# piezo-driver_v0_95-R003.net
KiCad netlist of a schematic drawn in EAGLE
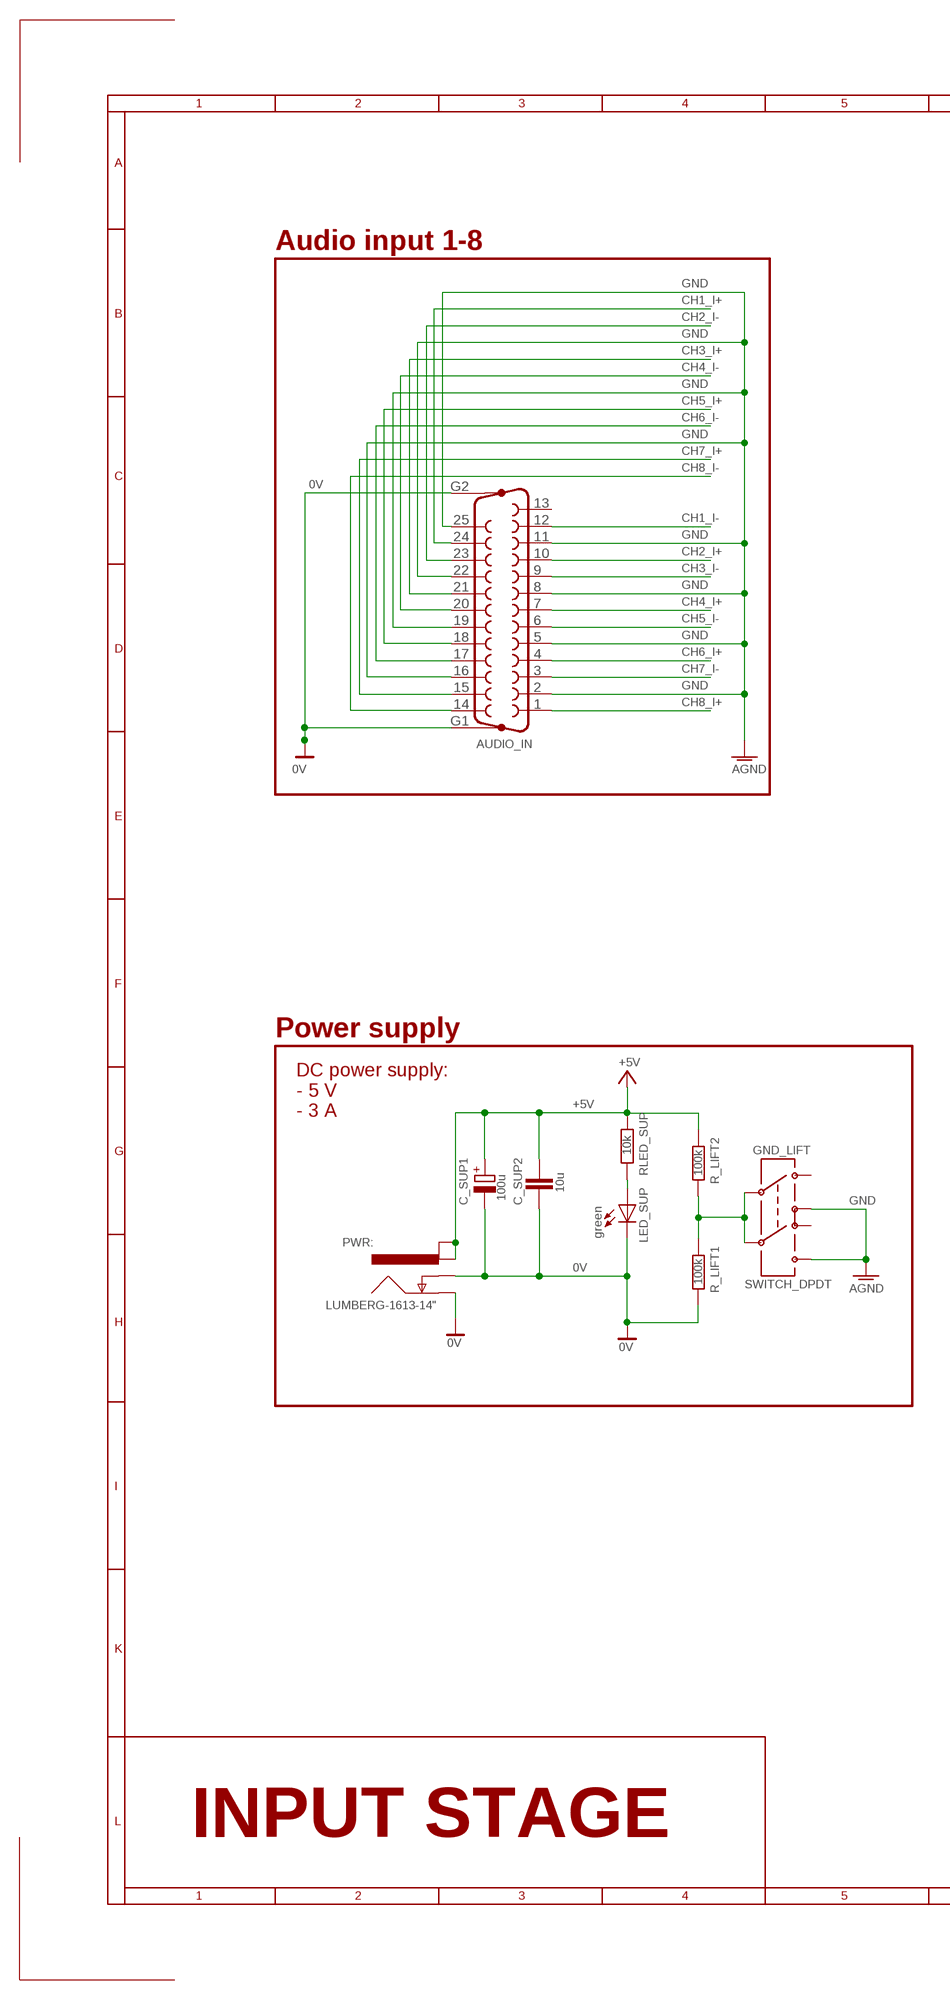
[diagram p0: schematic, sheet 1, part 1 of 2]
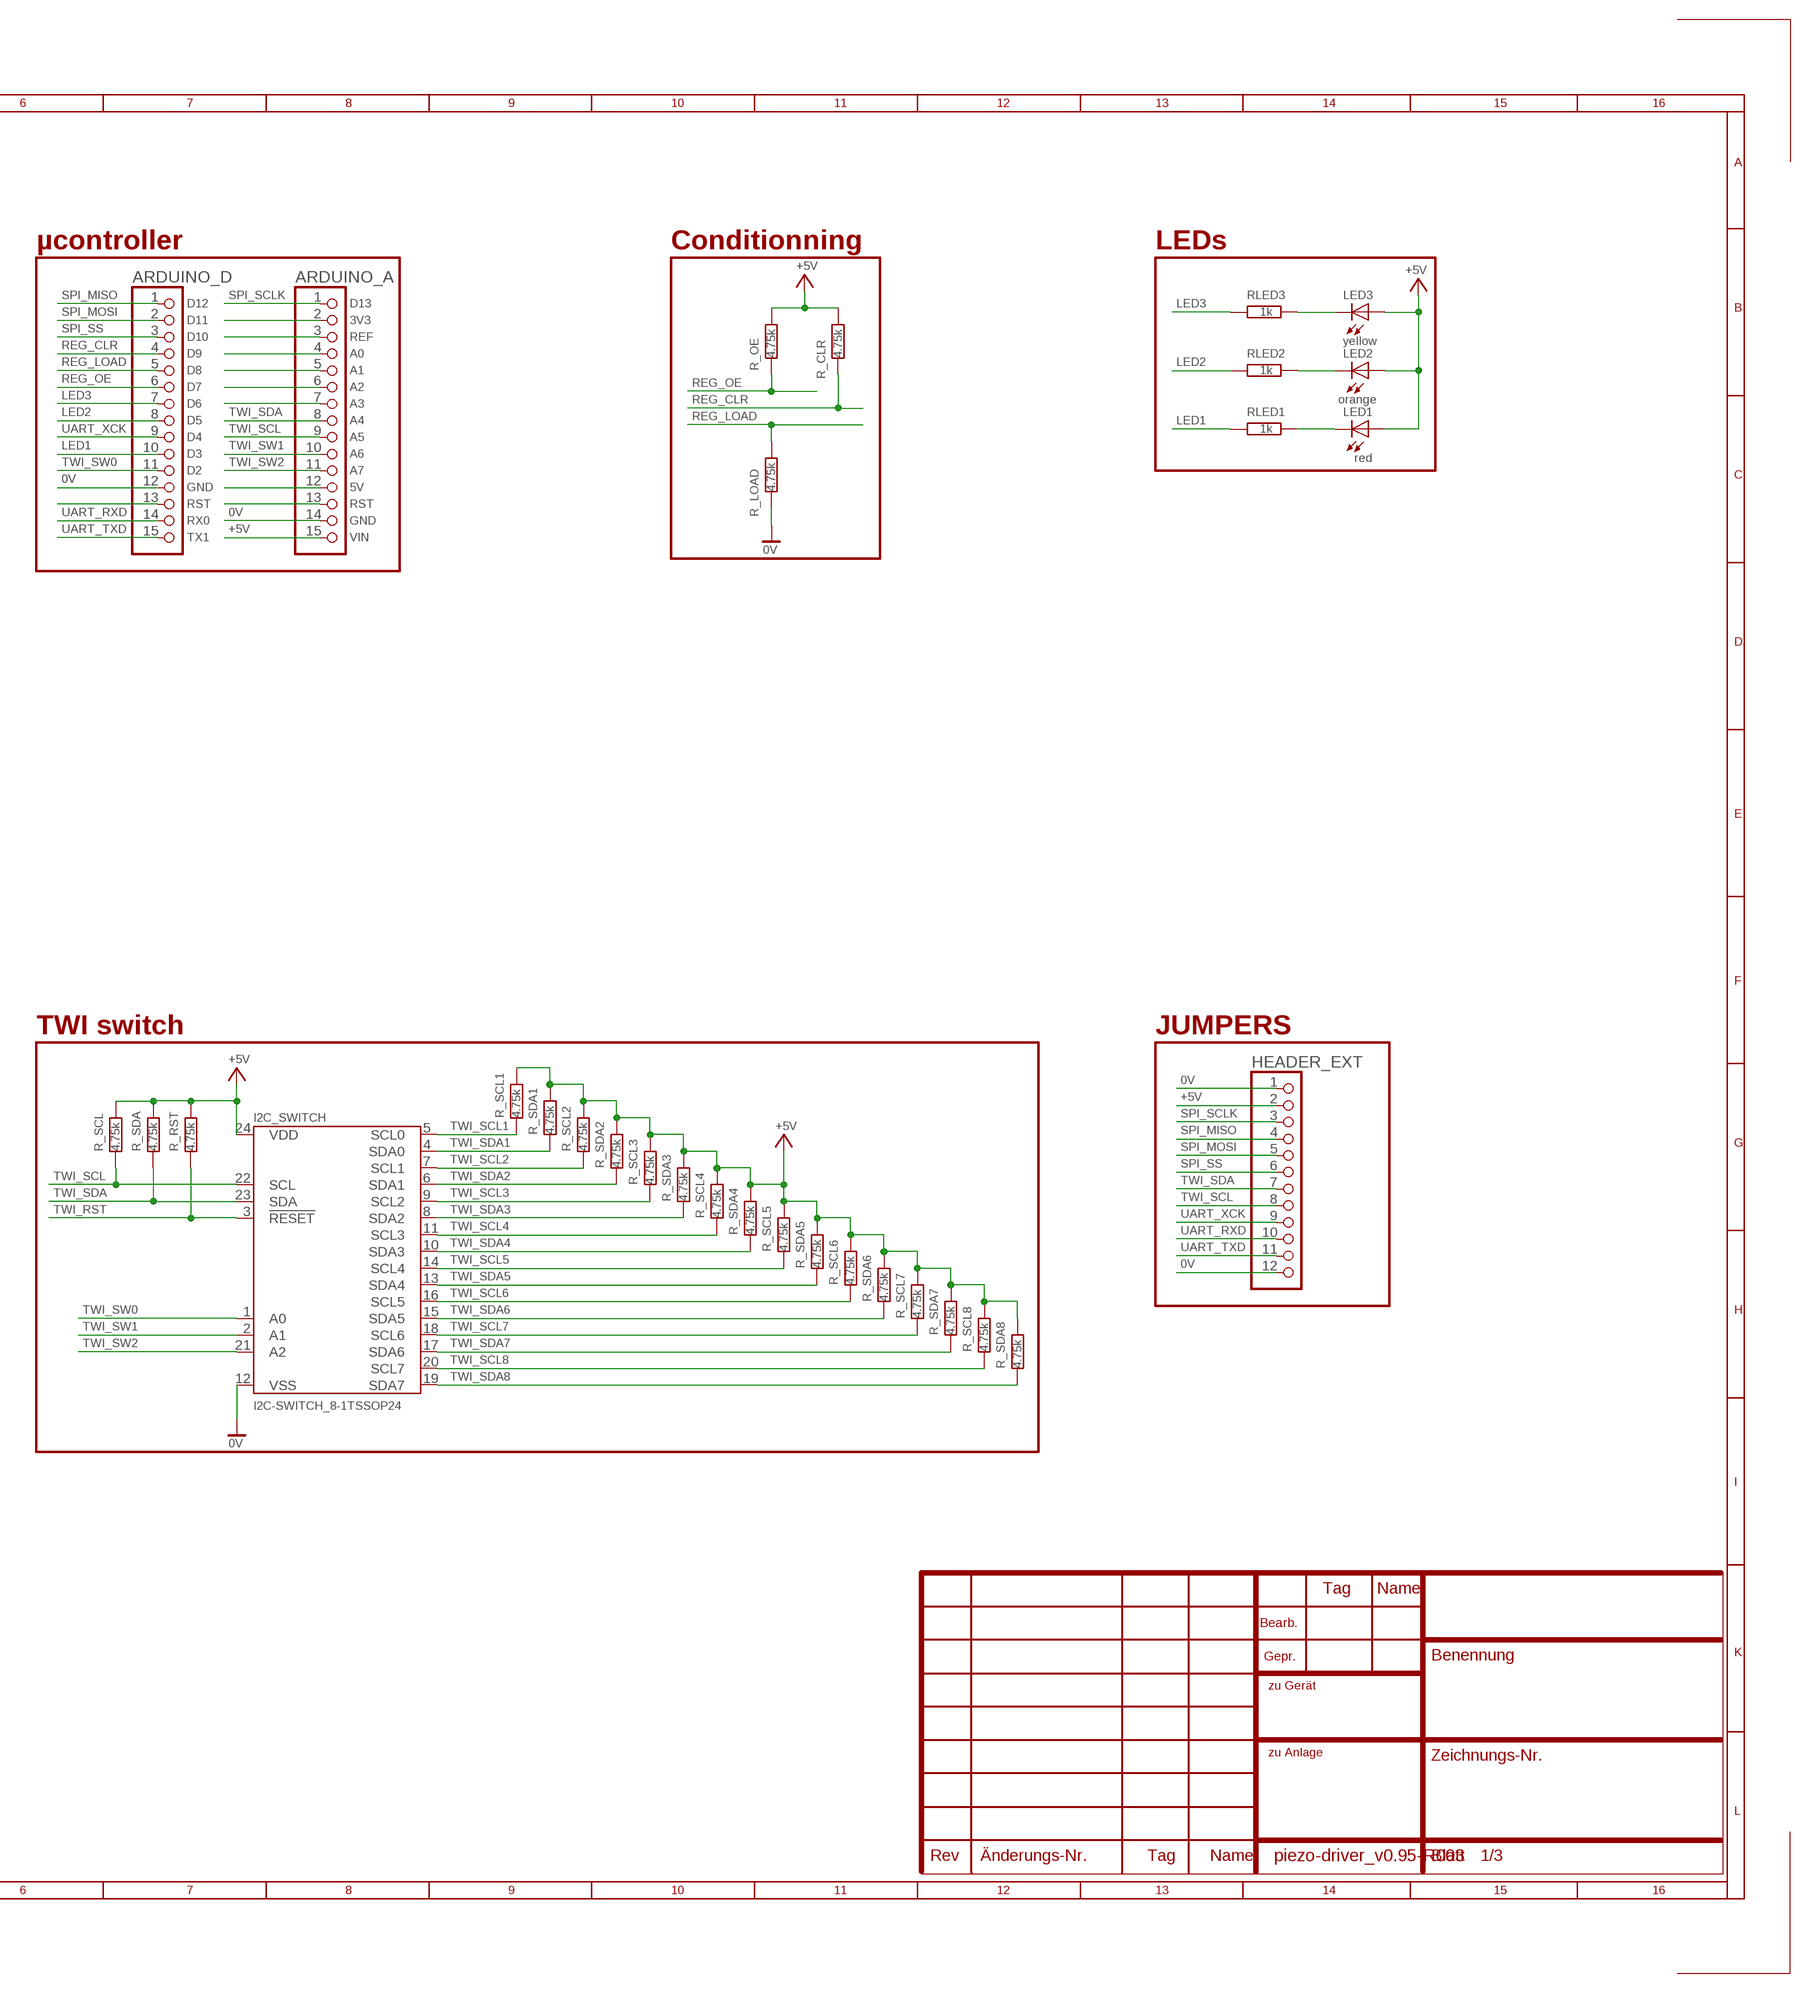
[diagram p1: schematic, sheet 1, part 2 of 2]
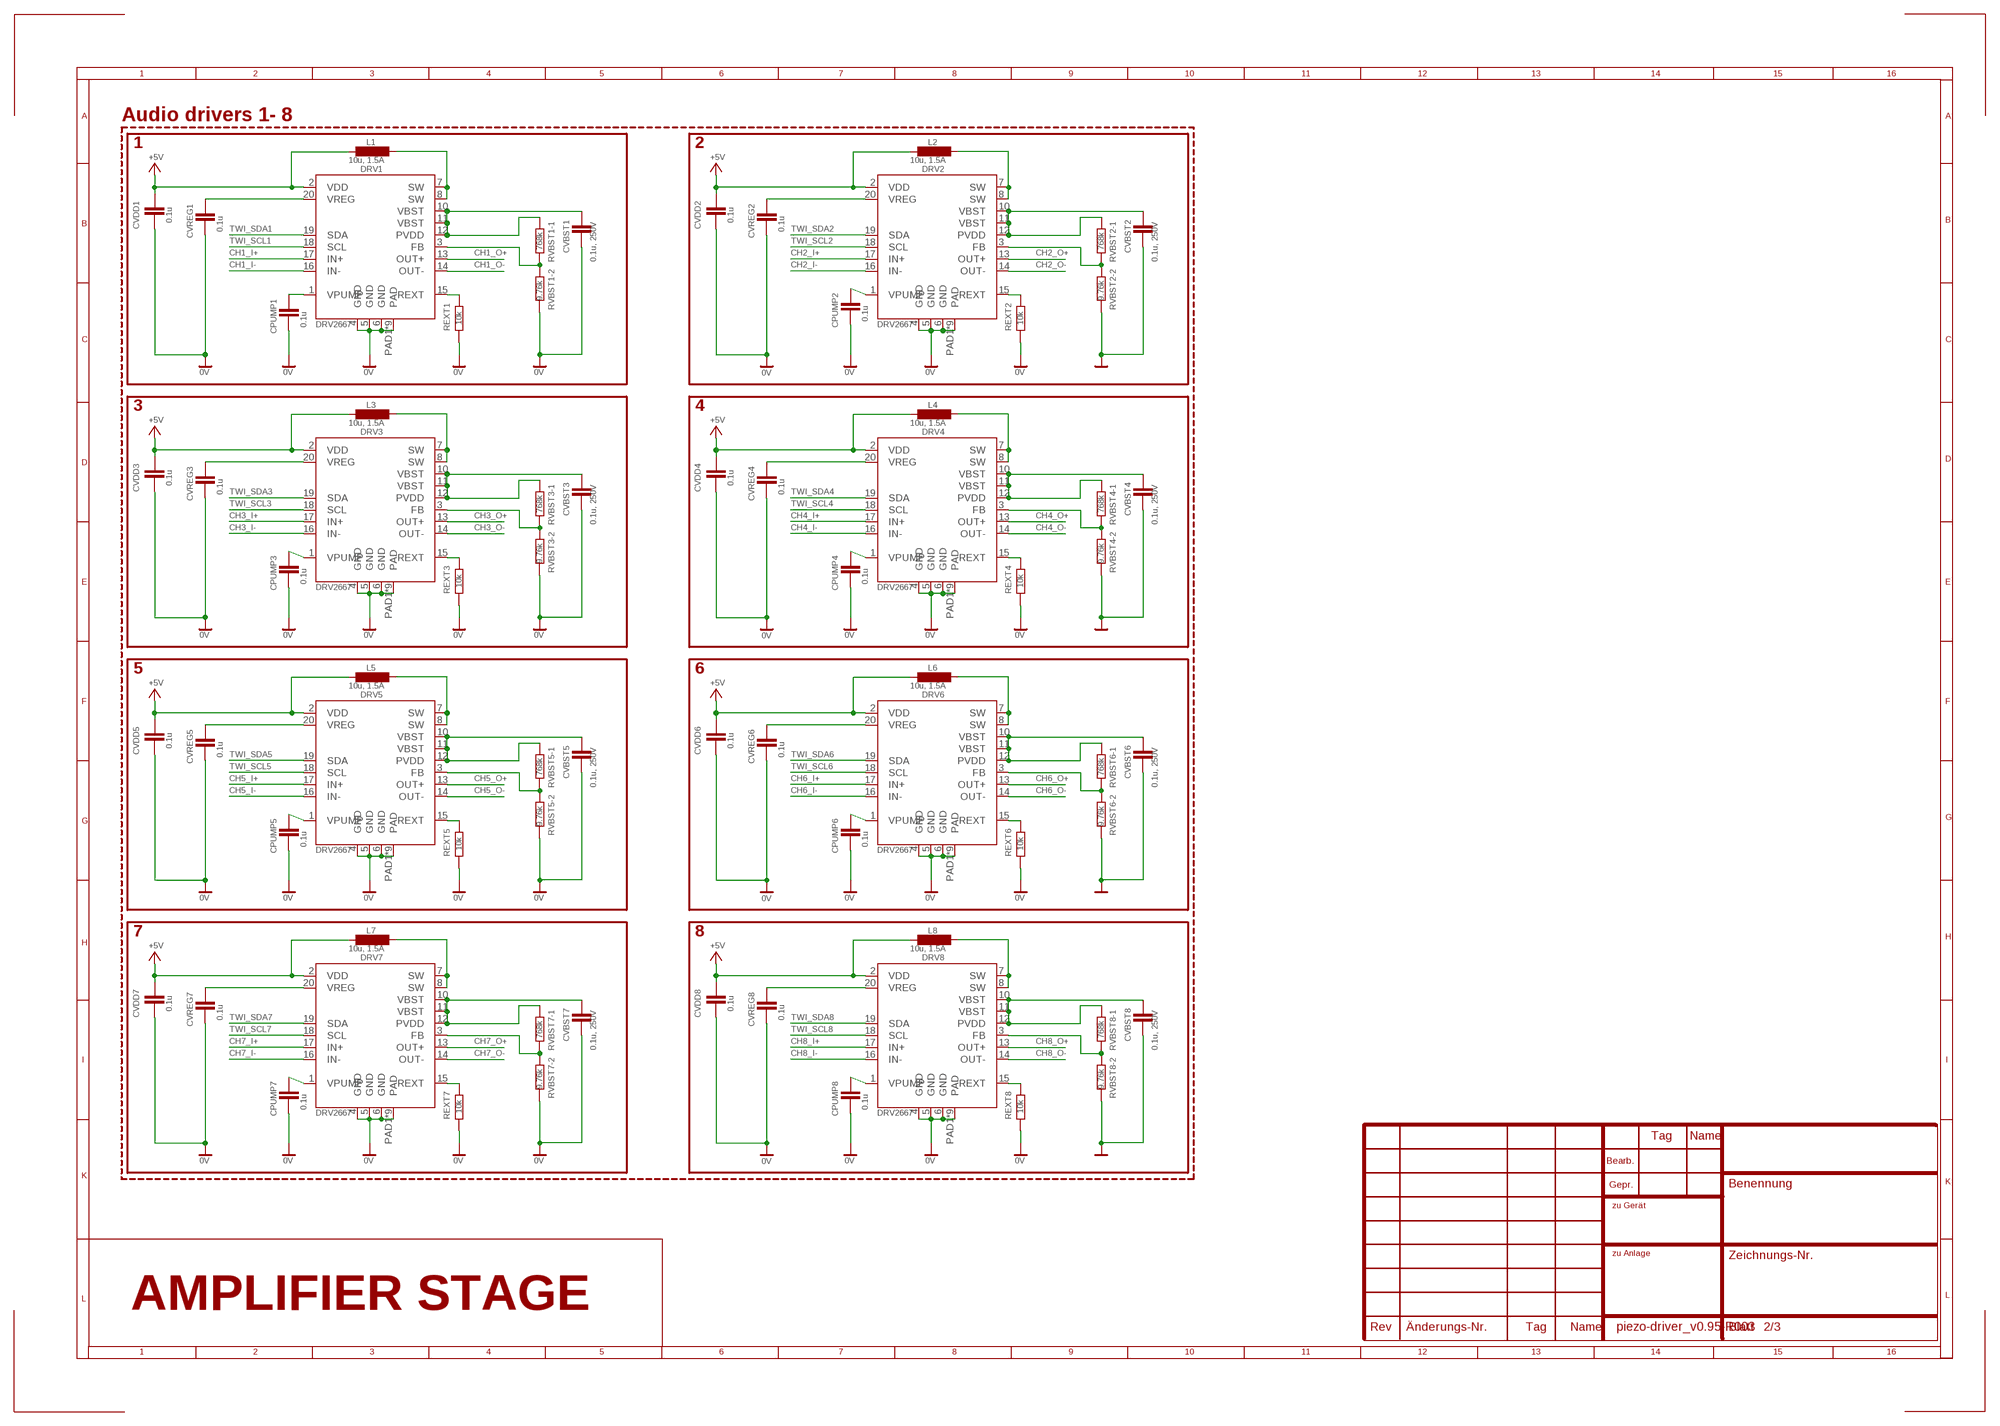
[diagram p2: schematic, sheet 2]
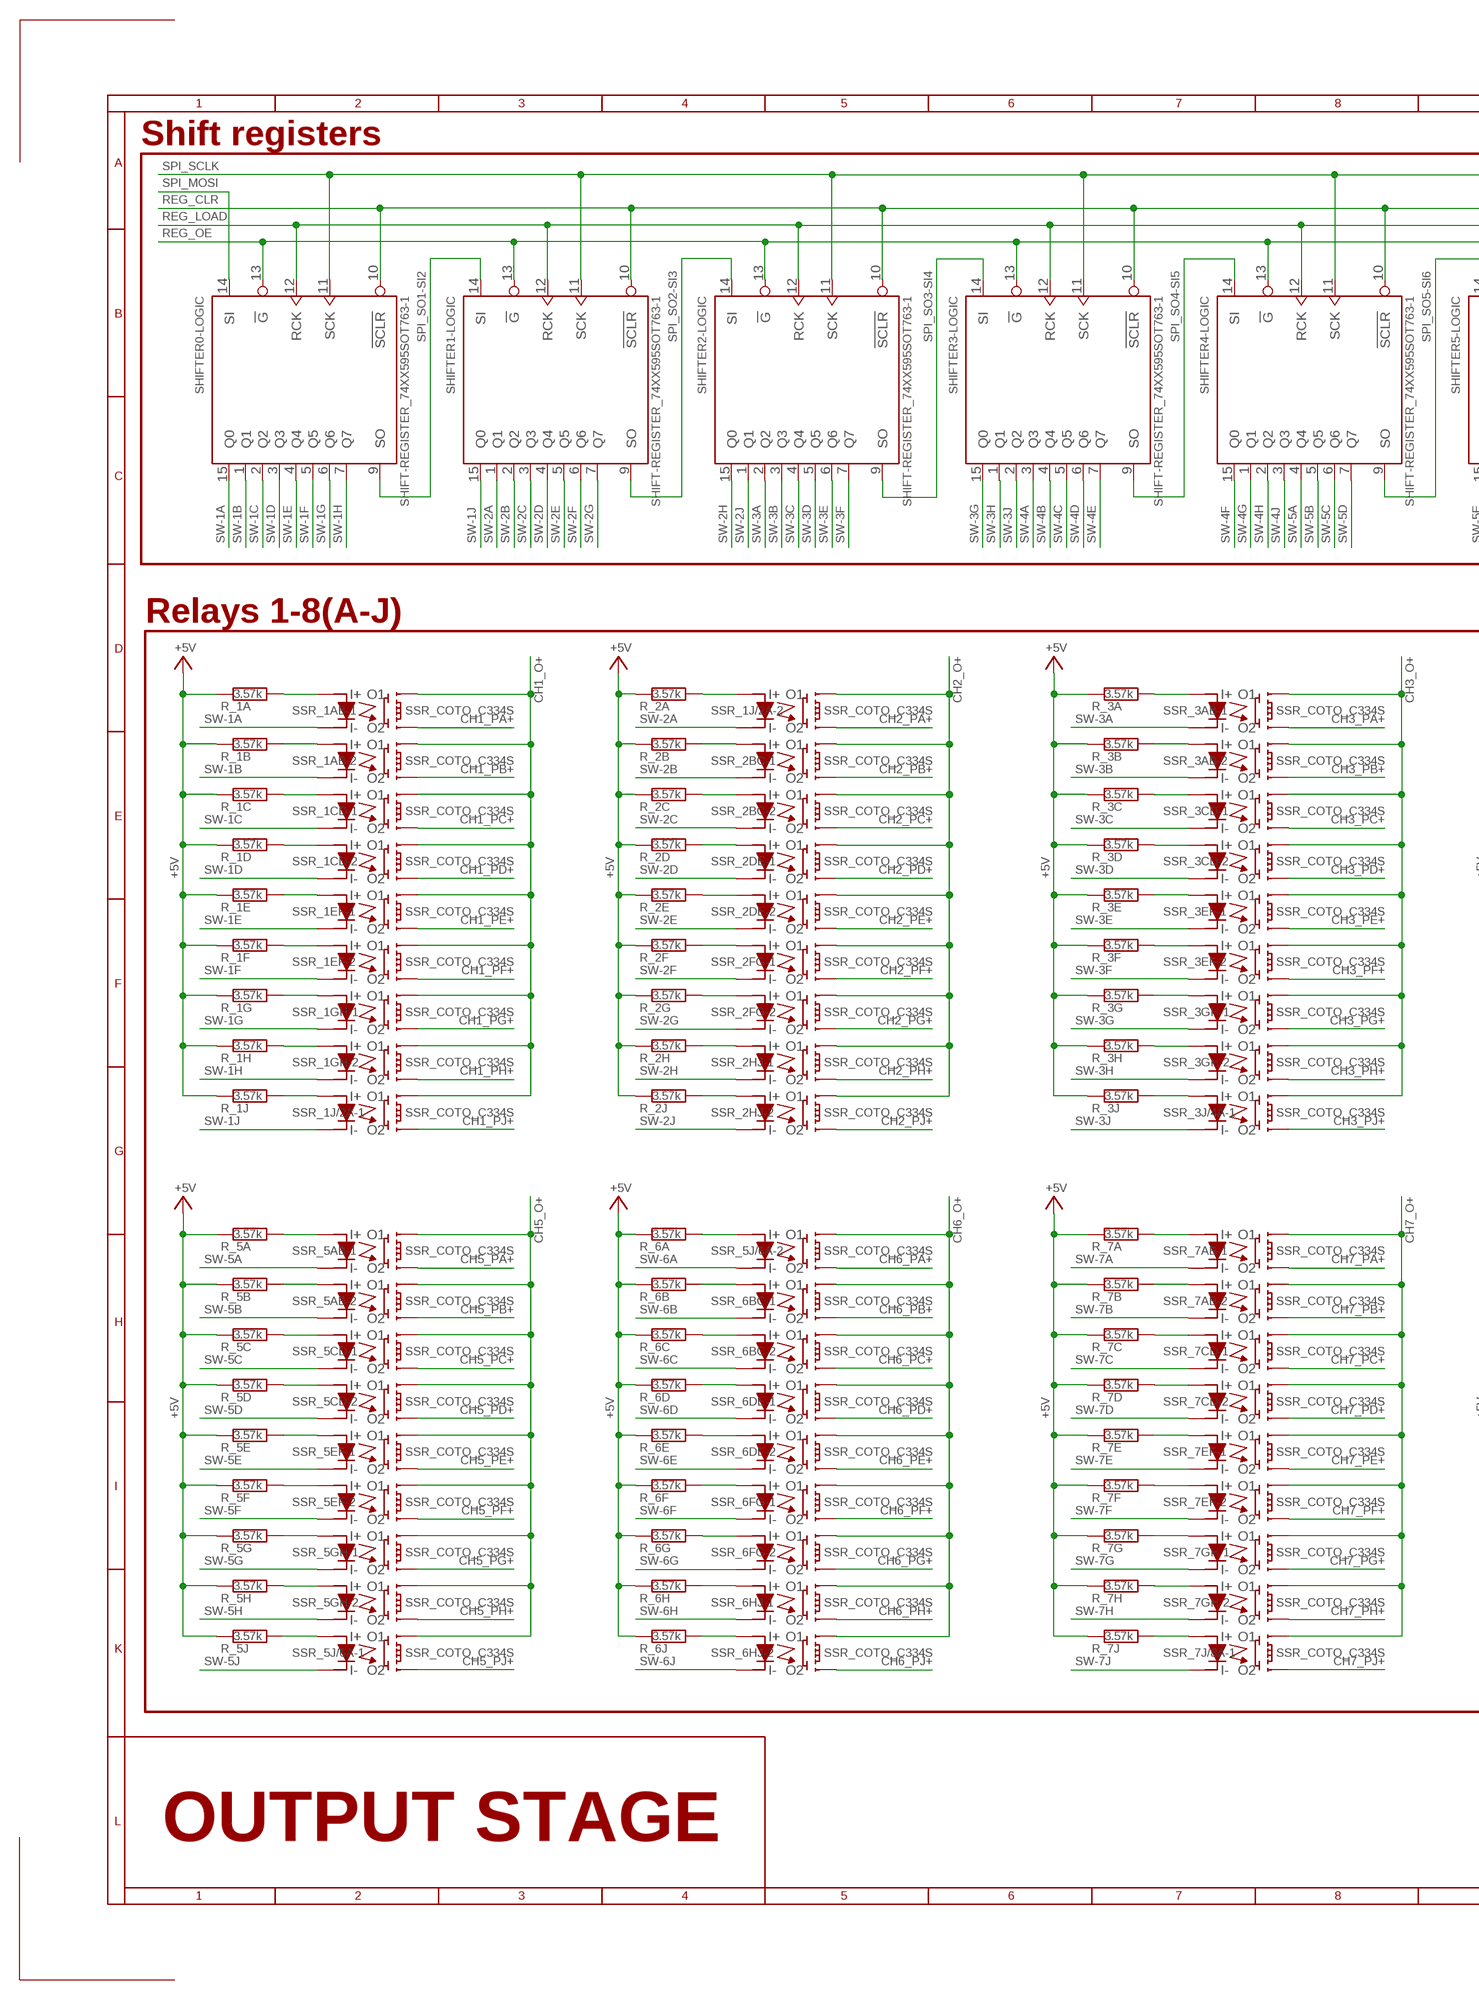
[diagram p3: schematic, sheet 3, part 1 of 2]
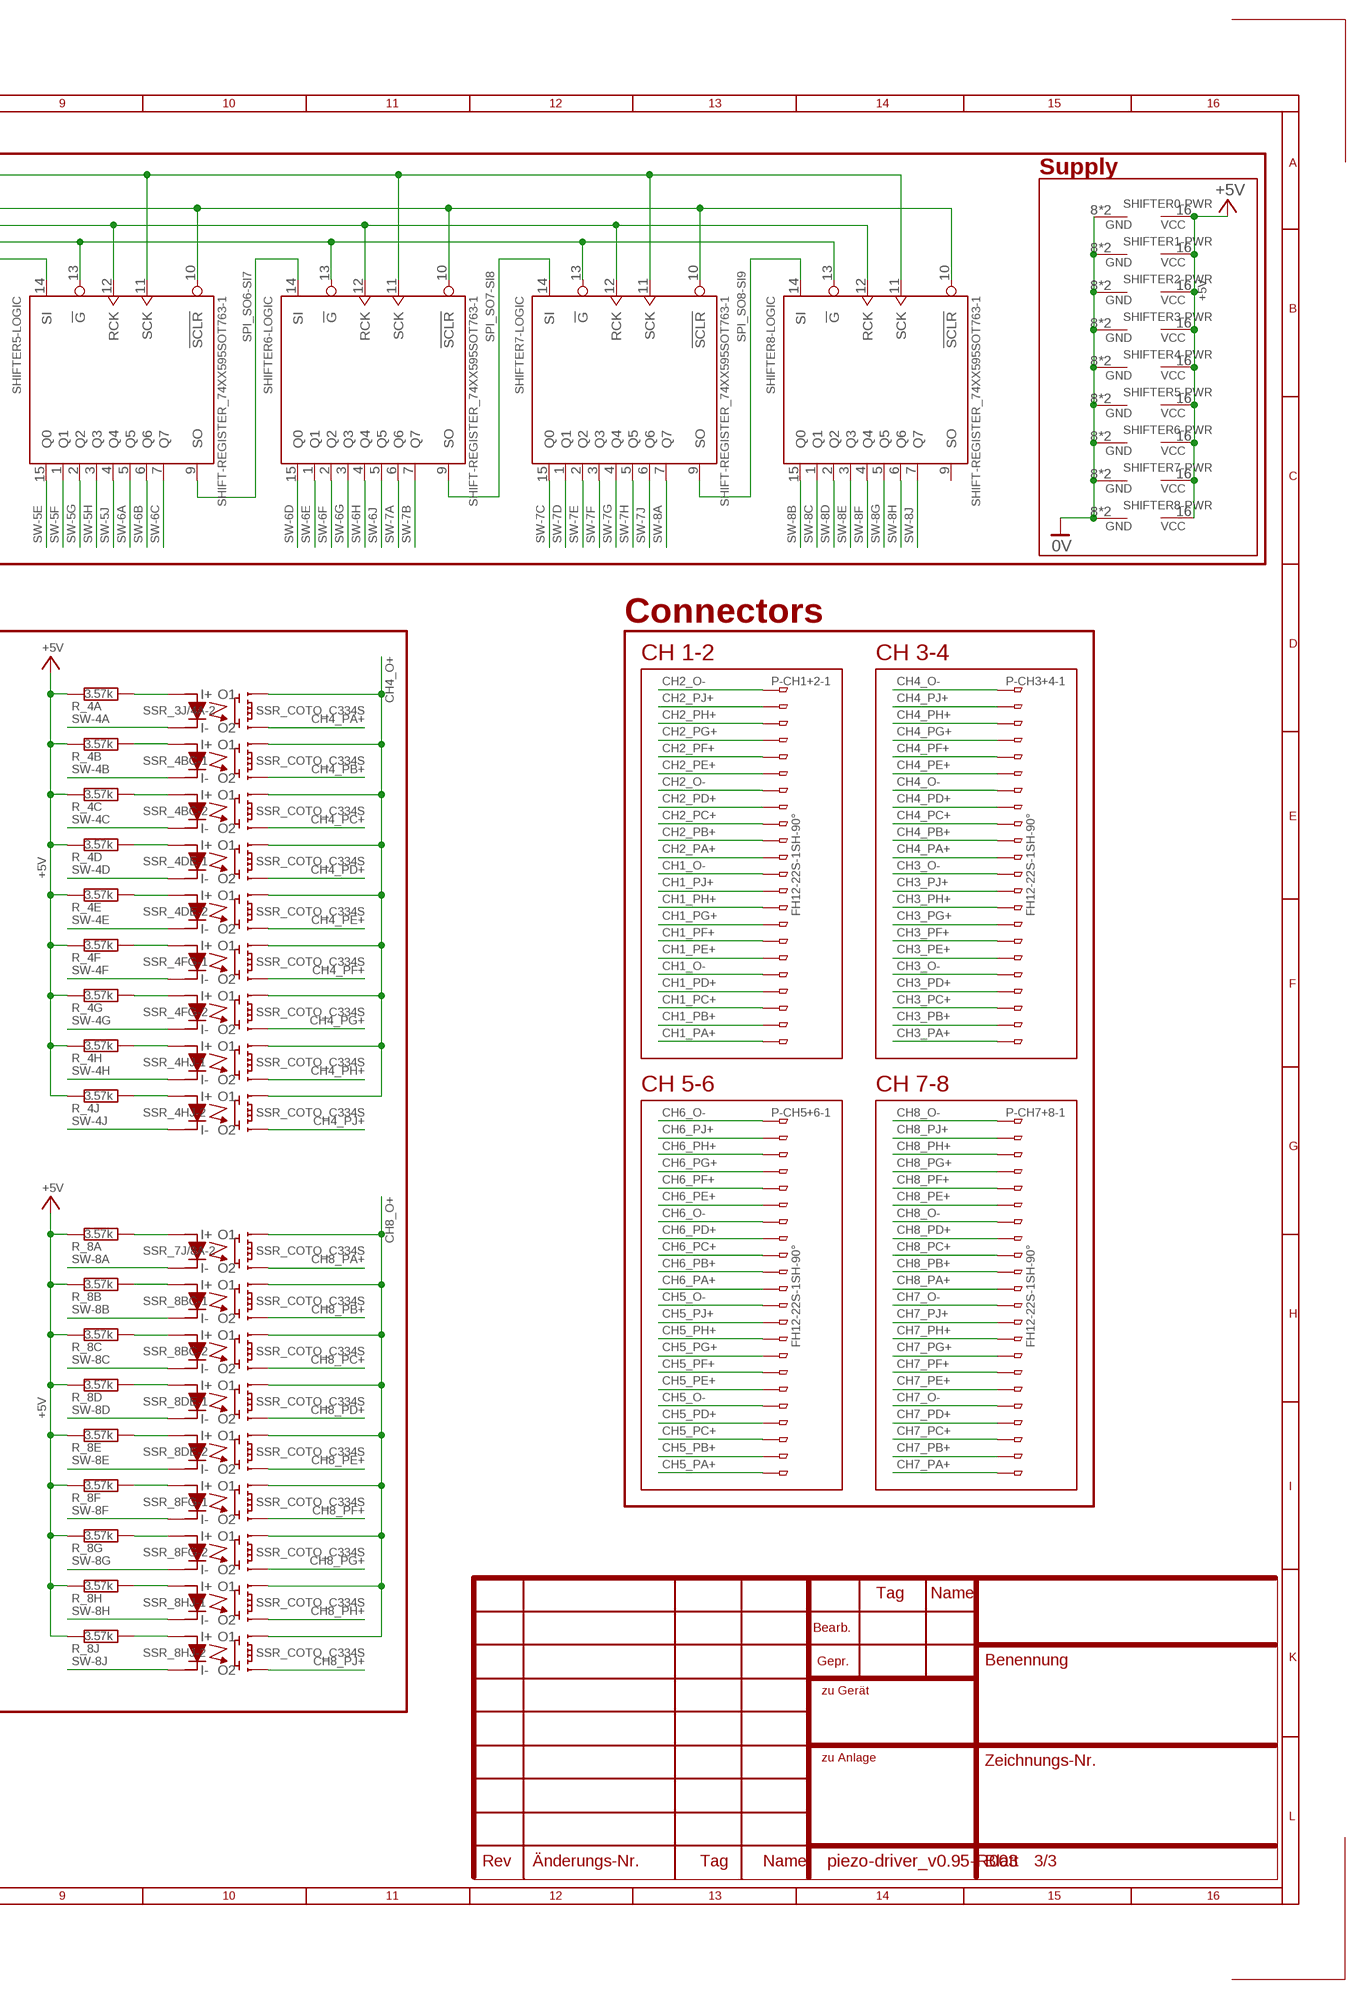
[diagram p4: schematic, sheet 3, part 2 of 2]

(export (version "E")
  (design (tool "Eeschema 10.0.6"))
  (components
    (comp (ref "ARDUINO_A")
      (value "PINHD-1X15")
      (footprint "eagle-import:1X15")
      (libsource (lib "eagle-import") (part "PINHD-1X15"))
    )
    (comp (ref "ARDUINO_D")
      (value "PINHD-1X15")
      (footprint "eagle-import:1X15")
      (libsource (lib "eagle-import") (part "PINHD-1X15"))
    )
    (comp (ref "AUDIO_IN")
      (value "F25HP")
      (footprint "eagle-import:F25HP")
      (libsource (lib "eagle-import") (part "F25HP"))
    )
    (comp (ref "C_SUP1")
      (value "100u")
      (footprint "eagle-import:EIA3216")
      (libsource (lib "eagle-import") (part "CAP_POL12061"))
    )
    (comp (ref "C_SUP2")
      (value "10u")
      (footprint "eagle-import:C0805K")
      (libsource (lib "eagle-import") (part "C-EUC0805K"))
    )
    (comp (ref "GND_LIFT")
      (value "SWITCH_DPDT")
      (footprint "eagle-import:SWITCH_JS202011")
      (libsource (lib "eagle-import") (part "SWITCH_DPDT"))
    )
    (comp (ref "HEADER_EXT")
      (value "PINHD-1X12")
      (footprint "eagle-import:1X12")
      (libsource (lib "eagle-import") (part "PINHD-1X12"))
    )
    (comp (ref "I2C_SWITCH")
      (value "I2C-SWITCH_8-1TSSOP24")
      (footprint "eagle-import:TSSOP24")
      (libsource (lib "eagle-import") (part "I2C-SWITCH_8-1TSSOP24"))
    )
    (comp (ref "LED1")
      (value "red")
      (footprint "eagle-import:LED-1206")
      (libsource (lib "eagle-import") (part "LED1206"))
    )
    (comp (ref "LED2")
      (value "orange")
      (footprint "eagle-import:LED-1206")
      (libsource (lib "eagle-import") (part "LED1206"))
    )
    (comp (ref "LED3")
      (value "yellow")
      (footprint "eagle-import:LED-1206")
      (libsource (lib "eagle-import") (part "LED1206"))
    )
    (comp (ref "LED_SUP")
      (value "green")
      (footprint "eagle-import:LED-1206")
      (libsource (lib "eagle-import") (part "LED1206"))
    )
    (comp (ref "PWR:")
      (value "LUMBERG-1613-14\"")
      (footprint "eagle-import:LUMBERG-1613_14")
      (libsource (lib "eagle-import") (part "LUMBERG-1613-14{dblquote}"))
    )
    (comp (ref "RLED1")
      (value "1k")
      (footprint "eagle-import:R0402")
      (libsource (lib "eagle-import") (part "R-EU_R0402"))
    )
    (comp (ref "RLED2")
      (value "1k")
      (footprint "eagle-import:R0402")
      (libsource (lib "eagle-import") (part "R-EU_R0402"))
    )
    (comp (ref "RLED3")
      (value "1k")
      (footprint "eagle-import:R0402")
      (libsource (lib "eagle-import") (part "R-EU_R0402"))
    )
    (comp (ref "RLED_SUP")
      (value "10k")
      (footprint "eagle-import:R0402")
      (libsource (lib "eagle-import") (part "R-EU_R0402"))
    )
    (comp (ref "R_CLR")
      (value "4.75k")
      (footprint "eagle-import:R0402")
      (libsource (lib "eagle-import") (part "R-EU_R0402"))
    )
    (comp (ref "R_LIFT1")
      (value "100k")
      (footprint "eagle-import:R0402")
      (libsource (lib "eagle-import") (part "R-EU_R0402"))
    )
    (comp (ref "R_LIFT2")
      (value "100k")
      (footprint "eagle-import:R0402")
      (libsource (lib "eagle-import") (part "R-EU_R0402"))
    )
    (comp (ref "R_LOAD")
      (value "4.75k")
      (footprint "eagle-import:R0402")
      (libsource (lib "eagle-import") (part "R-EU_R0402"))
    )
    (comp (ref "R_OE")
      (value "4.75k")
      (footprint "eagle-import:R0402")
      (libsource (lib "eagle-import") (part "R-EU_R0402"))
    )
    (comp (ref "R_RST")
      (value "4.75k")
      (footprint "eagle-import:R0402")
      (libsource (lib "eagle-import") (part "R-EU_R0402"))
    )
    (comp (ref "R_SCL")
      (value "4.75k")
      (footprint "eagle-import:R0402")
      (libsource (lib "eagle-import") (part "R-EU_R0402"))
    )
    (comp (ref "R_SCL1")
      (value "4.75k")
      (footprint "eagle-import:R0402")
      (libsource (lib "eagle-import") (part "R-EU_R0402"))
    )
    (comp (ref "R_SCL2")
      (value "4.75k")
      (footprint "eagle-import:R0402")
      (libsource (lib "eagle-import") (part "R-EU_R0402"))
    )
    (comp (ref "R_SCL3")
      (value "4.75k")
      (footprint "eagle-import:R0402")
      (libsource (lib "eagle-import") (part "R-EU_R0402"))
    )
    (comp (ref "R_SCL4")
      (value "4.75k")
      (footprint "eagle-import:R0402")
      (libsource (lib "eagle-import") (part "R-EU_R0402"))
    )
    (comp (ref "R_SCL5")
      (value "4.75k")
      (footprint "eagle-import:R0402")
      (libsource (lib "eagle-import") (part "R-EU_R0402"))
    )
    (comp (ref "R_SCL6")
      (value "4.75k")
      (footprint "eagle-import:R0402")
      (libsource (lib "eagle-import") (part "R-EU_R0402"))
    )
    (comp (ref "R_SCL7")
      (value "4.75k")
      (footprint "eagle-import:R0402")
      (libsource (lib "eagle-import") (part "R-EU_R0402"))
    )
    (comp (ref "R_SCL8")
      (value "4.75k")
      (footprint "eagle-import:R0402")
      (libsource (lib "eagle-import") (part "R-EU_R0402"))
    )
    (comp (ref "R_SDA")
      (value "4.75k")
      (footprint "eagle-import:R0402")
      (libsource (lib "eagle-import") (part "R-EU_R0402"))
    )
    (comp (ref "R_SDA1")
      (value "4.75k")
      (footprint "eagle-import:R0402")
      (libsource (lib "eagle-import") (part "R-EU_R0402"))
    )
    (comp (ref "R_SDA2")
      (value "4.75k")
      (footprint "eagle-import:R0402")
      (libsource (lib "eagle-import") (part "R-EU_R0402"))
    )
    (comp (ref "R_SDA3")
      (value "4.75k")
      (footprint "eagle-import:R0402")
      (libsource (lib "eagle-import") (part "R-EU_R0402"))
    )
    (comp (ref "R_SDA4")
      (value "4.75k")
      (footprint "eagle-import:R0402")
      (libsource (lib "eagle-import") (part "R-EU_R0402"))
    )
    (comp (ref "R_SDA5")
      (value "4.75k")
      (footprint "eagle-import:R0402")
      (libsource (lib "eagle-import") (part "R-EU_R0402"))
    )
    (comp (ref "R_SDA6")
      (value "4.75k")
      (footprint "eagle-import:R0402")
      (libsource (lib "eagle-import") (part "R-EU_R0402"))
    )
    (comp (ref "R_SDA7")
      (value "4.75k")
      (footprint "eagle-import:R0402")
      (libsource (lib "eagle-import") (part "R-EU_R0402"))
    )
    (comp (ref "R_SDA8")
      (value "4.75k")
      (footprint "eagle-import:R0402")
      (libsource (lib "eagle-import") (part "R-EU_R0402"))
    )
    (comp (ref "CPUMP1")
      (value "0.1u")
      (footprint "eagle-import:C0402")
      (libsource (lib "eagle-import") (part "C-EUC0402"))
    )
    (comp (ref "CPUMP2")
      (value "0.1u")
      (footprint "eagle-import:C0402")
      (libsource (lib "eagle-import") (part "C-EUC0402"))
    )
    (comp (ref "CPUMP3")
      (value "0.1u")
      (footprint "eagle-import:C0402")
      (libsource (lib "eagle-import") (part "C-EUC0402"))
    )
    (comp (ref "CPUMP4")
      (value "0.1u")
      (footprint "eagle-import:C0402")
      (libsource (lib "eagle-import") (part "C-EUC0402"))
    )
    (comp (ref "CPUMP5")
      (value "0.1u")
      (footprint "eagle-import:C0402")
      (libsource (lib "eagle-import") (part "C-EUC0402"))
    )
    (comp (ref "CPUMP6")
      (value "0.1u")
      (footprint "eagle-import:C0402")
      (libsource (lib "eagle-import") (part "C-EUC0402"))
    )
    (comp (ref "CPUMP7")
      (value "0.1u")
      (footprint "eagle-import:C0402")
      (libsource (lib "eagle-import") (part "C-EUC0402"))
    )
    (comp (ref "CPUMP8")
      (value "0.1u")
      (footprint "eagle-import:C0402")
      (libsource (lib "eagle-import") (part "C-EUC0402"))
    )
    (comp (ref "CVBST1")
      (value "0.1u, 250V")
      (footprint "eagle-import:C0805")
      (libsource (lib "eagle-import") (part "C-EUC0805"))
    )
    (comp (ref "CVBST2")
      (value "0.1u, 250V")
      (footprint "eagle-import:C0805")
      (libsource (lib "eagle-import") (part "C-EUC0805"))
    )
    (comp (ref "CVBST3")
      (value "0.1u, 250V")
      (footprint "eagle-import:C0805")
      (libsource (lib "eagle-import") (part "C-EUC0805"))
    )
    (comp (ref "CVBST4")
      (value "0.1u, 250V")
      (footprint "eagle-import:C0805")
      (libsource (lib "eagle-import") (part "C-EUC0805"))
    )
    (comp (ref "CVBST5")
      (value "0.1u, 250V")
      (footprint "eagle-import:C0805")
      (libsource (lib "eagle-import") (part "C-EUC0805"))
    )
    (comp (ref "CVBST6")
      (value "0.1u, 250V")
      (footprint "eagle-import:C0805")
      (libsource (lib "eagle-import") (part "C-EUC0805"))
    )
    (comp (ref "CVBST7")
      (value "0.1u, 250V")
      (footprint "eagle-import:C0805")
      (libsource (lib "eagle-import") (part "C-EUC0805"))
    )
    (comp (ref "CVBST8")
      (value "0.1u, 250V")
      (footprint "eagle-import:C0805")
      (libsource (lib "eagle-import") (part "C-EUC0805"))
    )
    (comp (ref "CVDD1")
      (value "0.1u")
      (footprint "eagle-import:C0402")
      (libsource (lib "eagle-import") (part "C-EUC0402"))
    )
    (comp (ref "CVDD2")
      (value "0.1u")
      (footprint "eagle-import:C0402")
      (libsource (lib "eagle-import") (part "C-EUC0402"))
    )
    (comp (ref "CVDD3")
      (value "0.1u")
      (footprint "eagle-import:C0402")
      (libsource (lib "eagle-import") (part "C-EUC0402"))
    )
    (comp (ref "CVDD4")
      (value "0.1u")
      (footprint "eagle-import:C0402")
      (libsource (lib "eagle-import") (part "C-EUC0402"))
    )
    (comp (ref "CVDD5")
      (value "0.1u")
      (footprint "eagle-import:C0402")
      (libsource (lib "eagle-import") (part "C-EUC0402"))
    )
    (comp (ref "CVDD6")
      (value "0.1u")
      (footprint "eagle-import:C0402")
      (libsource (lib "eagle-import") (part "C-EUC0402"))
    )
    (comp (ref "CVDD7")
      (value "0.1u")
      (footprint "eagle-import:C0402")
      (libsource (lib "eagle-import") (part "C-EUC0402"))
    )
    (comp (ref "CVDD8")
      (value "0.1u")
      (footprint "eagle-import:C0402")
      (libsource (lib "eagle-import") (part "C-EUC0402"))
    )
    (comp (ref "CVREG1")
      (value "0.1u")
      (footprint "eagle-import:C0402")
      (libsource (lib "eagle-import") (part "C-EUC0402"))
    )
    (comp (ref "CVREG2")
      (value "0.1u")
      (footprint "eagle-import:C0402")
      (libsource (lib "eagle-import") (part "C-EUC0402"))
    )
    (comp (ref "CVREG3")
      (value "0.1u")
      (footprint "eagle-import:C0402")
      (libsource (lib "eagle-import") (part "C-EUC0402"))
    )
    (comp (ref "CVREG4")
      (value "0.1u")
      (footprint "eagle-import:C0402")
      (libsource (lib "eagle-import") (part "C-EUC0402"))
    )
    (comp (ref "CVREG5")
      (value "0.1u")
      (footprint "eagle-import:C0402")
      (libsource (lib "eagle-import") (part "C-EUC0402"))
    )
    (comp (ref "CVREG6")
      (value "0.1u")
      (footprint "eagle-import:C0402")
      (libsource (lib "eagle-import") (part "C-EUC0402"))
    )
    (comp (ref "CVREG7")
      (value "0.1u")
      (footprint "eagle-import:C0402")
      (libsource (lib "eagle-import") (part "C-EUC0402"))
    )
    (comp (ref "CVREG8")
      (value "0.1u")
      (footprint "eagle-import:C0402")
      (libsource (lib "eagle-import") (part "C-EUC0402"))
    )
    (comp (ref "DRV1")
      (value "DRV2667")
      (footprint "eagle-import:QFN-20_9TH")
      (libsource (lib "eagle-import") (part "DRV2667"))
    )
    (comp (ref "DRV2")
      (value "DRV2667")
      (footprint "eagle-import:QFN-20_9TH")
      (libsource (lib "eagle-import") (part "DRV2667"))
    )
    (comp (ref "DRV3")
      (value "DRV2667")
      (footprint "eagle-import:QFN-20_9TH")
      (libsource (lib "eagle-import") (part "DRV2667"))
    )
    (comp (ref "DRV4")
      (value "DRV2667")
      (footprint "eagle-import:QFN-20_9TH")
      (libsource (lib "eagle-import") (part "DRV2667"))
    )
    (comp (ref "DRV5")
      (value "DRV2667")
      (footprint "eagle-import:QFN-20_9TH")
      (libsource (lib "eagle-import") (part "DRV2667"))
    )
    (comp (ref "DRV6")
      (value "DRV2667")
      (footprint "eagle-import:QFN-20_9TH")
      (libsource (lib "eagle-import") (part "DRV2667"))
    )
    (comp (ref "DRV7")
      (value "DRV2667")
      (footprint "eagle-import:QFN-20_9TH")
      (libsource (lib "eagle-import") (part "DRV2667"))
    )
    (comp (ref "DRV8")
      (value "DRV2667")
      (footprint "eagle-import:QFN-20_9TH")
      (libsource (lib "eagle-import") (part "DRV2667"))
    )
    (comp (ref "L1")
      (value "10u, 1.5A")
      (footprint "eagle-import:L4.0X4.0")
      (libsource (lib "eagle-import") (part "L-EU4.0X4.0"))
    )
    (comp (ref "L2")
      (value "10u, 1.5A")
      (footprint "eagle-import:L4.0X4.0")
      (libsource (lib "eagle-import") (part "L-EU4.0X4.0"))
    )
    (comp (ref "L3")
      (value "10u, 1.5A")
      (footprint "eagle-import:L4.0X4.0")
      (libsource (lib "eagle-import") (part "L-EU4.0X4.0"))
    )
    (comp (ref "L4")
      (value "10u, 1.5A")
      (footprint "eagle-import:L4.0X4.0")
      (libsource (lib "eagle-import") (part "L-EU4.0X4.0"))
    )
    (comp (ref "L5")
      (value "10u, 1.5A")
      (footprint "eagle-import:L4.0X4.0")
      (libsource (lib "eagle-import") (part "L-EU4.0X4.0"))
    )
    (comp (ref "L6")
      (value "10u, 1.5A")
      (footprint "eagle-import:L4.0X4.0")
      (libsource (lib "eagle-import") (part "L-EU4.0X4.0"))
    )
    (comp (ref "L7")
      (value "10u, 1.5A")
      (footprint "eagle-import:L4.0X4.0")
      (libsource (lib "eagle-import") (part "L-EU4.0X4.0"))
    )
    (comp (ref "L8")
      (value "10u, 1.5A")
      (footprint "eagle-import:L4.0X4.0")
      (libsource (lib "eagle-import") (part "L-EU4.0X4.0"))
    )
    (comp (ref "REXT1")
      (value "10k")
      (footprint "eagle-import:R0402")
      (libsource (lib "eagle-import") (part "R-EU_R0402"))
    )
    (comp (ref "REXT2")
      (value "10k")
      (footprint "eagle-import:R0402")
      (libsource (lib "eagle-import") (part "R-EU_R0402"))
    )
    (comp (ref "REXT3")
      (value "10k")
      (footprint "eagle-import:R0402")
      (libsource (lib "eagle-import") (part "R-EU_R0402"))
    )
    (comp (ref "REXT4")
      (value "10k")
      (footprint "eagle-import:R0402")
      (libsource (lib "eagle-import") (part "R-EU_R0402"))
    )
    (comp (ref "REXT5")
      (value "10k")
      (footprint "eagle-import:R0402")
      (libsource (lib "eagle-import") (part "R-EU_R0402"))
    )
    (comp (ref "REXT6")
      (value "10k")
      (footprint "eagle-import:R0402")
      (libsource (lib "eagle-import") (part "R-EU_R0402"))
    )
    (comp (ref "REXT7")
      (value "10k")
      (footprint "eagle-import:R0402")
      (libsource (lib "eagle-import") (part "R-EU_R0402"))
    )
    (comp (ref "REXT8")
      (value "10k")
      (footprint "eagle-import:R0402")
      (libsource (lib "eagle-import") (part "R-EU_R0402"))
    )
    (comp (ref "RVBST1-1")
      (value "768k")
      (footprint "eagle-import:R0402")
      (libsource (lib "eagle-import") (part "R-EU_R0402"))
    )
    (comp (ref "RVBST1-2")
      (value "9.76k")
      (footprint "eagle-import:R0402")
      (libsource (lib "eagle-import") (part "R-EU_R0402"))
    )
    (comp (ref "RVBST2-1")
      (value "768k")
      (footprint "eagle-import:R0402")
      (libsource (lib "eagle-import") (part "R-EU_R0402"))
    )
    (comp (ref "RVBST2-2")
      (value "9.76k")
      (footprint "eagle-import:R0402")
      (libsource (lib "eagle-import") (part "R-EU_R0402"))
    )
    (comp (ref "RVBST3-1")
      (value "768k")
      (footprint "eagle-import:R0402")
      (libsource (lib "eagle-import") (part "R-EU_R0402"))
    )
    (comp (ref "RVBST3-2")
      (value "9.76k")
      (footprint "eagle-import:R0402")
      (libsource (lib "eagle-import") (part "R-EU_R0402"))
    )
    (comp (ref "RVBST4-1")
      (value "768k")
      (footprint "eagle-import:R0402")
      (libsource (lib "eagle-import") (part "R-EU_R0402"))
    )
    (comp (ref "RVBST4-2")
      (value "9.76k")
      (footprint "eagle-import:R0402")
      (libsource (lib "eagle-import") (part "R-EU_R0402"))
    )
    (comp (ref "RVBST5-1")
      (value "768k")
      (footprint "eagle-import:R0402")
      (libsource (lib "eagle-import") (part "R-EU_R0402"))
    )
    (comp (ref "RVBST5-2")
      (value "9.76k")
      (footprint "eagle-import:R0402")
      (libsource (lib "eagle-import") (part "R-EU_R0402"))
    )
    (comp (ref "RVBST6-1")
      (value "768k")
      (footprint "eagle-import:R0402")
      (libsource (lib "eagle-import") (part "R-EU_R0402"))
    )
    (comp (ref "RVBST6-2")
      (value "9.76k")
      (footprint "eagle-import:R0402")
      (libsource (lib "eagle-import") (part "R-EU_R0402"))
    )
    (comp (ref "RVBST7-1")
      (value "768k")
      (footprint "eagle-import:R0402")
      (libsource (lib "eagle-import") (part "R-EU_R0402"))
    )
    (comp (ref "RVBST7-2")
      (value "9.76k")
      (footprint "eagle-import:R0402")
      (libsource (lib "eagle-import") (part "R-EU_R0402"))
    )
    (comp (ref "RVBST8-1")
      (value "768k")
      (footprint "eagle-import:R0402")
      (libsource (lib "eagle-import") (part "R-EU_R0402"))
    )
    (comp (ref "RVBST8-2")
      (value "9.76k")
      (footprint "eagle-import:R0402")
      (libsource (lib "eagle-import") (part "R-EU_R0402"))
    )
    (comp (ref "P-CH1+2")
      (value "FH12-22S-1SH-90°")
      (footprint "eagle-import:FH12-22S-1SH")
      (libsource (lib "eagle-import") (part "FH12-22S-1SH-90°"))
    )
    (comp (ref "P-CH3+4")
      (value "FH12-22S-1SH-90°")
      (footprint "eagle-import:FH12-22S-1SH")
      (libsource (lib "eagle-import") (part "FH12-22S-1SH-90°"))
    )
    (comp (ref "P-CH5+6")
      (value "FH12-22S-1SH-90°")
      (footprint "eagle-import:FH12-22S-1SH")
      (libsource (lib "eagle-import") (part "FH12-22S-1SH-90°"))
    )
    (comp (ref "P-CH7+8")
      (value "FH12-22S-1SH-90°")
      (footprint "eagle-import:FH12-22S-1SH")
      (libsource (lib "eagle-import") (part "FH12-22S-1SH-90°"))
    )
    (comp (ref "R_1A")
      (value "3.57k")
      (footprint "eagle-import:R0402")
      (libsource (lib "eagle-import") (part "R-EU_R0402"))
    )
    (comp (ref "R_1B")
      (value "3.57k")
      (footprint "eagle-import:R0402")
      (libsource (lib "eagle-import") (part "R-EU_R0402"))
    )
    (comp (ref "R_1C")
      (value "3.57k")
      (footprint "eagle-import:R0402")
      (libsource (lib "eagle-import") (part "R-EU_R0402"))
    )
    (comp (ref "R_1D")
      (value "3.57k")
      (footprint "eagle-import:R0402")
      (libsource (lib "eagle-import") (part "R-EU_R0402"))
    )
    (comp (ref "R_1E")
      (value "3.57k")
      (footprint "eagle-import:R0402")
      (libsource (lib "eagle-import") (part "R-EU_R0402"))
    )
    (comp (ref "R_1F")
      (value "3.57k")
      (footprint "eagle-import:R0402")
      (libsource (lib "eagle-import") (part "R-EU_R0402"))
    )
    (comp (ref "R_1G")
      (value "3.57k")
      (footprint "eagle-import:R0402")
      (libsource (lib "eagle-import") (part "R-EU_R0402"))
    )
    (comp (ref "R_1H")
      (value "3.57k")
      (footprint "eagle-import:R0402")
      (libsource (lib "eagle-import") (part "R-EU_R0402"))
    )
    (comp (ref "R_1J")
      (value "3.57k")
      (footprint "eagle-import:R0402")
      (libsource (lib "eagle-import") (part "R-EU_R0402"))
    )
    (comp (ref "R_2A")
      (value "3.57k")
      (footprint "eagle-import:R0402")
      (libsource (lib "eagle-import") (part "R-EU_R0402"))
    )
    (comp (ref "R_2B")
      (value "3.57k")
      (footprint "eagle-import:R0402")
      (libsource (lib "eagle-import") (part "R-EU_R0402"))
    )
    (comp (ref "R_2C")
      (value "3.57k")
      (footprint "eagle-import:R0402")
      (libsource (lib "eagle-import") (part "R-EU_R0402"))
    )
    (comp (ref "R_2D")
      (value "3.57k")
      (footprint "eagle-import:R0402")
      (libsource (lib "eagle-import") (part "R-EU_R0402"))
    )
    (comp (ref "R_2E")
      (value "3.57k")
      (footprint "eagle-import:R0402")
      (libsource (lib "eagle-import") (part "R-EU_R0402"))
    )
    (comp (ref "R_2F")
      (value "3.57k")
      (footprint "eagle-import:R0402")
      (libsource (lib "eagle-import") (part "R-EU_R0402"))
    )
    (comp (ref "R_2G")
      (value "3.57k")
      (footprint "eagle-import:R0402")
      (libsource (lib "eagle-import") (part "R-EU_R0402"))
    )
    (comp (ref "R_2H")
      (value "3.57k")
      (footprint "eagle-import:R0402")
      (libsource (lib "eagle-import") (part "R-EU_R0402"))
    )
    (comp (ref "R_2J")
      (value "3.57k")
      (footprint "eagle-import:R0402")
      (libsource (lib "eagle-import") (part "R-EU_R0402"))
    )
    (comp (ref "R_3A")
      (value "3.57k")
      (footprint "eagle-import:R0402")
      (libsource (lib "eagle-import") (part "R-EU_R0402"))
    )
    (comp (ref "R_3B")
      (value "3.57k")
      (footprint "eagle-import:R0402")
      (libsource (lib "eagle-import") (part "R-EU_R0402"))
    )
    (comp (ref "R_3C")
      (value "3.57k")
      (footprint "eagle-import:R0402")
      (libsource (lib "eagle-import") (part "R-EU_R0402"))
    )
    (comp (ref "R_3D")
      (value "3.57k")
      (footprint "eagle-import:R0402")
      (libsource (lib "eagle-import") (part "R-EU_R0402"))
    )
    (comp (ref "R_3E")
      (value "3.57k")
      (footprint "eagle-import:R0402")
      (libsource (lib "eagle-import") (part "R-EU_R0402"))
    )
    (comp (ref "R_3F")
      (value "3.57k")
      (footprint "eagle-import:R0402")
      (libsource (lib "eagle-import") (part "R-EU_R0402"))
    )
    (comp (ref "R_3G")
      (value "3.57k")
      (footprint "eagle-import:R0402")
      (libsource (lib "eagle-import") (part "R-EU_R0402"))
    )
    (comp (ref "R_3H")
      (value "3.57k")
      (footprint "eagle-import:R0402")
      (libsource (lib "eagle-import") (part "R-EU_R0402"))
    )
    (comp (ref "R_3J")
      (value "3.57k")
      (footprint "eagle-import:R0402")
      (libsource (lib "eagle-import") (part "R-EU_R0402"))
    )
    (comp (ref "R_4A")
      (value "3.57k")
      (footprint "eagle-import:R0402")
      (libsource (lib "eagle-import") (part "R-EU_R0402"))
    )
    (comp (ref "R_4B")
      (value "3.57k")
      (footprint "eagle-import:R0402")
      (libsource (lib "eagle-import") (part "R-EU_R0402"))
    )
    (comp (ref "R_4C")
      (value "3.57k")
      (footprint "eagle-import:R0402")
      (libsource (lib "eagle-import") (part "R-EU_R0402"))
    )
    (comp (ref "R_4D")
      (value "3.57k")
      (footprint "eagle-import:R0402")
      (libsource (lib "eagle-import") (part "R-EU_R0402"))
    )
    (comp (ref "R_4E")
      (value "3.57k")
      (footprint "eagle-import:R0402")
      (libsource (lib "eagle-import") (part "R-EU_R0402"))
    )
    (comp (ref "R_4F")
      (value "3.57k")
      (footprint "eagle-import:R0402")
      (libsource (lib "eagle-import") (part "R-EU_R0402"))
    )
    (comp (ref "R_4G")
      (value "3.57k")
      (footprint "eagle-import:R0402")
      (libsource (lib "eagle-import") (part "R-EU_R0402"))
    )
    (comp (ref "R_4H")
      (value "3.57k")
      (footprint "eagle-import:R0402")
      (libsource (lib "eagle-import") (part "R-EU_R0402"))
    )
    (comp (ref "R_4J")
      (value "3.57k")
      (footprint "eagle-import:R0402")
      (libsource (lib "eagle-import") (part "R-EU_R0402"))
    )
    (comp (ref "R_5A")
      (value "3.57k")
      (footprint "eagle-import:R0402")
      (libsource (lib "eagle-import") (part "R-EU_R0402"))
    )
    (comp (ref "R_5B")
      (value "3.57k")
      (footprint "eagle-import:R0402")
      (libsource (lib "eagle-import") (part "R-EU_R0402"))
    )
    (comp (ref "R_5C")
      (value "3.57k")
      (footprint "eagle-import:R0402")
      (libsource (lib "eagle-import") (part "R-EU_R0402"))
    )
    (comp (ref "R_5D")
      (value "3.57k")
      (footprint "eagle-import:R0402")
      (libsource (lib "eagle-import") (part "R-EU_R0402"))
    )
    (comp (ref "R_5E")
      (value "3.57k")
      (footprint "eagle-import:R0402")
      (libsource (lib "eagle-import") (part "R-EU_R0402"))
    )
    (comp (ref "R_5F")
      (value "3.57k")
      (footprint "eagle-import:R0402")
      (libsource (lib "eagle-import") (part "R-EU_R0402"))
    )
    (comp (ref "R_5G")
      (value "3.57k")
      (footprint "eagle-import:R0402")
      (libsource (lib "eagle-import") (part "R-EU_R0402"))
    )
    (comp (ref "R_5H")
      (value "3.57k")
      (footprint "eagle-import:R0402")
      (libsource (lib "eagle-import") (part "R-EU_R0402"))
    )
    (comp (ref "R_5J")
      (value "3.57k")
      (footprint "eagle-import:R0402")
      (libsource (lib "eagle-import") (part "R-EU_R0402"))
    )
    (comp (ref "R_6A")
      (value "3.57k")
      (footprint "eagle-import:R0402")
      (libsource (lib "eagle-import") (part "R-EU_R0402"))
    )
    (comp (ref "R_6B")
      (value "3.57k")
      (footprint "eagle-import:R0402")
      (libsource (lib "eagle-import") (part "R-EU_R0402"))
    )
    (comp (ref "R_6C")
      (value "3.57k")
      (footprint "eagle-import:R0402")
      (libsource (lib "eagle-import") (part "R-EU_R0402"))
    )
    (comp (ref "R_6D")
      (value "3.57k")
      (footprint "eagle-import:R0402")
      (libsource (lib "eagle-import") (part "R-EU_R0402"))
    )
    (comp (ref "R_6E")
      (value "3.57k")
      (footprint "eagle-import:R0402")
      (libsource (lib "eagle-import") (part "R-EU_R0402"))
    )
    (comp (ref "R_6F")
      (value "3.57k")
      (footprint "eagle-import:R0402")
      (libsource (lib "eagle-import") (part "R-EU_R0402"))
    )
    (comp (ref "R_6G")
      (value "3.57k")
      (footprint "eagle-import:R0402")
      (libsource (lib "eagle-import") (part "R-EU_R0402"))
    )
    (comp (ref "R_6H")
      (value "3.57k")
      (footprint "eagle-import:R0402")
      (libsource (lib "eagle-import") (part "R-EU_R0402"))
    )
    (comp (ref "R_6J")
      (value "3.57k")
      (footprint "eagle-import:R0402")
      (libsource (lib "eagle-import") (part "R-EU_R0402"))
    )
    (comp (ref "R_7A")
      (value "3.57k")
      (footprint "eagle-import:R0402")
      (libsource (lib "eagle-import") (part "R-EU_R0402"))
    )
    (comp (ref "R_7B")
      (value "3.57k")
      (footprint "eagle-import:R0402")
      (libsource (lib "eagle-import") (part "R-EU_R0402"))
    )
    (comp (ref "R_7C")
      (value "3.57k")
      (footprint "eagle-import:R0402")
      (libsource (lib "eagle-import") (part "R-EU_R0402"))
    )
    (comp (ref "R_7D")
      (value "3.57k")
      (footprint "eagle-import:R0402")
      (libsource (lib "eagle-import") (part "R-EU_R0402"))
    )
    (comp (ref "R_7E")
      (value "3.57k")
      (footprint "eagle-import:R0402")
      (libsource (lib "eagle-import") (part "R-EU_R0402"))
    )
    (comp (ref "R_7F")
      (value "3.57k")
      (footprint "eagle-import:R0402")
      (libsource (lib "eagle-import") (part "R-EU_R0402"))
    )
    (comp (ref "R_7G")
      (value "3.57k")
      (footprint "eagle-import:R0402")
      (libsource (lib "eagle-import") (part "R-EU_R0402"))
    )
    (comp (ref "R_7H")
      (value "3.57k")
      (footprint "eagle-import:R0402")
      (libsource (lib "eagle-import") (part "R-EU_R0402"))
    )
    (comp (ref "R_7J")
      (value "3.57k")
      (footprint "eagle-import:R0402")
      (libsource (lib "eagle-import") (part "R-EU_R0402"))
    )
    (comp (ref "R_8A")
      (value "3.57k")
      (footprint "eagle-import:R0402")
      (libsource (lib "eagle-import") (part "R-EU_R0402"))
    )
    (comp (ref "R_8B")
      (value "3.57k")
      (footprint "eagle-import:R0402")
      (libsource (lib "eagle-import") (part "R-EU_R0402"))
    )
    (comp (ref "R_8C")
      (value "3.57k")
      (footprint "eagle-import:R0402")
      (libsource (lib "eagle-import") (part "R-EU_R0402"))
    )
    (comp (ref "R_8D")
      (value "3.57k")
      (footprint "eagle-import:R0402")
      (libsource (lib "eagle-import") (part "R-EU_R0402"))
    )
    (comp (ref "R_8E")
      (value "3.57k")
      (footprint "eagle-import:R0402")
      (libsource (lib "eagle-import") (part "R-EU_R0402"))
    )
    (comp (ref "R_8F")
      (value "3.57k")
      (footprint "eagle-import:R0402")
      (libsource (lib "eagle-import") (part "R-EU_R0402"))
    )
    (comp (ref "R_8G")
      (value "3.57k")
      (footprint "eagle-import:R0402")
      (libsource (lib "eagle-import") (part "R-EU_R0402"))
    )
    (comp (ref "R_8H")
      (value "3.57k")
      (footprint "eagle-import:R0402")
      (libsource (lib "eagle-import") (part "R-EU_R0402"))
    )
    (comp (ref "R_8J")
      (value "3.57k")
      (footprint "eagle-import:R0402")
      (libsource (lib "eagle-import") (part "R-EU_R0402"))
    )
    (comp (ref "SHIFTER0")
      (value "SHIFT-REGISTER_74XX595SOT763-1")
      (footprint "eagle-import:SOT763-1")
      (libsource (lib "eagle-import") (part "SHIFT-REGISTER_74XX595SOT763-1"))
    )
    (comp (ref "SHIFTER1")
      (value "SHIFT-REGISTER_74XX595SOT763-1")
      (footprint "eagle-import:SOT763-1")
      (libsource (lib "eagle-import") (part "SHIFT-REGISTER_74XX595SOT763-1"))
    )
    (comp (ref "SHIFTER2")
      (value "SHIFT-REGISTER_74XX595SOT763-1")
      (footprint "eagle-import:SOT763-1")
      (libsource (lib "eagle-import") (part "SHIFT-REGISTER_74XX595SOT763-1"))
    )
    (comp (ref "SHIFTER3")
      (value "SHIFT-REGISTER_74XX595SOT763-1")
      (footprint "eagle-import:SOT763-1")
      (libsource (lib "eagle-import") (part "SHIFT-REGISTER_74XX595SOT763-1"))
    )
    (comp (ref "SHIFTER4")
      (value "SHIFT-REGISTER_74XX595SOT763-1")
      (footprint "eagle-import:SOT763-1")
      (libsource (lib "eagle-import") (part "SHIFT-REGISTER_74XX595SOT763-1"))
    )
    (comp (ref "SHIFTER5")
      (value "SHIFT-REGISTER_74XX595SOT763-1")
      (footprint "eagle-import:SOT763-1")
      (libsource (lib "eagle-import") (part "SHIFT-REGISTER_74XX595SOT763-1"))
    )
    (comp (ref "SHIFTER6")
      (value "SHIFT-REGISTER_74XX595SOT763-1")
      (footprint "eagle-import:SOT763-1")
      (libsource (lib "eagle-import") (part "SHIFT-REGISTER_74XX595SOT763-1"))
    )
    (comp (ref "SHIFTER7")
      (value "SHIFT-REGISTER_74XX595SOT763-1")
      (footprint "eagle-import:SOT763-1")
      (libsource (lib "eagle-import") (part "SHIFT-REGISTER_74XX595SOT763-1"))
    )
    (comp (ref "SHIFTER8")
      (value "SHIFT-REGISTER_74XX595SOT763-1")
      (footprint "eagle-import:SOT763-1")
      (libsource (lib "eagle-import") (part "SHIFT-REGISTER_74XX595SOT763-1"))
    )
    (comp (ref "SSR_1AB")
      (value "SSR_COTO_C334S")
      (footprint "eagle-import:SOP8")
      (libsource (lib "eagle-import") (part "SSR_COTO_C334S"))
    )
    (comp (ref "SSR_1CD")
      (value "SSR_COTO_C334S")
      (footprint "eagle-import:SOP8")
      (libsource (lib "eagle-import") (part "SSR_COTO_C334S"))
    )
    (comp (ref "SSR_1EF")
      (value "SSR_COTO_C334S")
      (footprint "eagle-import:SOP8")
      (libsource (lib "eagle-import") (part "SSR_COTO_C334S"))
    )
    (comp (ref "SSR_1GH")
      (value "SSR_COTO_C334S")
      (footprint "eagle-import:SOP8")
      (libsource (lib "eagle-import") (part "SSR_COTO_C334S"))
    )
    (comp (ref "SSR_1J/2A")
      (value "SSR_COTO_C334S")
      (footprint "eagle-import:SOP8")
      (libsource (lib "eagle-import") (part "SSR_COTO_C334S"))
    )
    (comp (ref "SSR_2BC")
      (value "SSR_COTO_C334S")
      (footprint "eagle-import:SOP8")
      (libsource (lib "eagle-import") (part "SSR_COTO_C334S"))
    )
    (comp (ref "SSR_2DE")
      (value "SSR_COTO_C334S")
      (footprint "eagle-import:SOP8")
      (libsource (lib "eagle-import") (part "SSR_COTO_C334S"))
    )
    (comp (ref "SSR_2FG")
      (value "SSR_COTO_C334S")
      (footprint "eagle-import:SOP8")
      (libsource (lib "eagle-import") (part "SSR_COTO_C334S"))
    )
    (comp (ref "SSR_2HJ")
      (value "SSR_COTO_C334S")
      (footprint "eagle-import:SOP8")
      (libsource (lib "eagle-import") (part "SSR_COTO_C334S"))
    )
    (comp (ref "SSR_3AB")
      (value "SSR_COTO_C334S")
      (footprint "eagle-import:SOP8")
      (libsource (lib "eagle-import") (part "SSR_COTO_C334S"))
    )
    (comp (ref "SSR_3CD")
      (value "SSR_COTO_C334S")
      (footprint "eagle-import:SOP8")
      (libsource (lib "eagle-import") (part "SSR_COTO_C334S"))
    )
    (comp (ref "SSR_3EF")
      (value "SSR_COTO_C334S")
      (footprint "eagle-import:SOP8")
      (libsource (lib "eagle-import") (part "SSR_COTO_C334S"))
    )
    (comp (ref "SSR_3GH")
      (value "SSR_COTO_C334S")
      (footprint "eagle-import:SOP8")
      (libsource (lib "eagle-import") (part "SSR_COTO_C334S"))
    )
    (comp (ref "SSR_3J/4A")
      (value "SSR_COTO_C334S")
      (footprint "eagle-import:SOP8")
      (libsource (lib "eagle-import") (part "SSR_COTO_C334S"))
    )
    (comp (ref "SSR_4BC")
      (value "SSR_COTO_C334S")
      (footprint "eagle-import:SOP8")
      (libsource (lib "eagle-import") (part "SSR_COTO_C334S"))
    )
    (comp (ref "SSR_4DE")
      (value "SSR_COTO_C334S")
      (footprint "eagle-import:SOP8")
      (libsource (lib "eagle-import") (part "SSR_COTO_C334S"))
    )
    (comp (ref "SSR_4FG")
      (value "SSR_COTO_C334S")
      (footprint "eagle-import:SOP8")
      (libsource (lib "eagle-import") (part "SSR_COTO_C334S"))
    )
    (comp (ref "SSR_4HJ")
      (value "SSR_COTO_C334S")
      (footprint "eagle-import:SOP8")
      (libsource (lib "eagle-import") (part "SSR_COTO_C334S"))
    )
    (comp (ref "SSR_5AB")
      (value "SSR_COTO_C334S")
      (footprint "eagle-import:SOP8")
      (libsource (lib "eagle-import") (part "SSR_COTO_C334S"))
    )
    (comp (ref "SSR_5CD")
      (value "SSR_COTO_C334S")
      (footprint "eagle-import:SOP8")
      (libsource (lib "eagle-import") (part "SSR_COTO_C334S"))
    )
    (comp (ref "SSR_5EF")
      (value "SSR_COTO_C334S")
      (footprint "eagle-import:SOP8")
      (libsource (lib "eagle-import") (part "SSR_COTO_C334S"))
    )
    (comp (ref "SSR_5GH")
      (value "SSR_COTO_C334S")
      (footprint "eagle-import:SOP8")
      (libsource (lib "eagle-import") (part "SSR_COTO_C334S"))
    )
    (comp (ref "SSR_5J/6A")
      (value "SSR_COTO_C334S")
      (footprint "eagle-import:SOP8")
      (libsource (lib "eagle-import") (part "SSR_COTO_C334S"))
    )
    (comp (ref "SSR_6BC")
      (value "SSR_COTO_C334S")
      (footprint "eagle-import:SOP8")
      (libsource (lib "eagle-import") (part "SSR_COTO_C334S"))
    )
    (comp (ref "SSR_6DE")
      (value "SSR_COTO_C334S")
      (footprint "eagle-import:SOP8")
      (libsource (lib "eagle-import") (part "SSR_COTO_C334S"))
    )
    (comp (ref "SSR_6FG")
      (value "SSR_COTO_C334S")
      (footprint "eagle-import:SOP8")
      (libsource (lib "eagle-import") (part "SSR_COTO_C334S"))
    )
    (comp (ref "SSR_6HJ")
      (value "SSR_COTO_C334S")
      (footprint "eagle-import:SOP8")
      (libsource (lib "eagle-import") (part "SSR_COTO_C334S"))
    )
    (comp (ref "SSR_7AB")
      (value "SSR_COTO_C334S")
      (footprint "eagle-import:SOP8")
      (libsource (lib "eagle-import") (part "SSR_COTO_C334S"))
    )
    (comp (ref "SSR_7CD")
      (value "SSR_COTO_C334S")
      (footprint "eagle-import:SOP8")
      (libsource (lib "eagle-import") (part "SSR_COTO_C334S"))
    )
    (comp (ref "SSR_7EF")
      (value "SSR_COTO_C334S")
      (footprint "eagle-import:SOP8")
      (libsource (lib "eagle-import") (part "SSR_COTO_C334S"))
    )
    (comp (ref "SSR_7GH")
      (value "SSR_COTO_C334S")
      (footprint "eagle-import:SOP8")
      (libsource (lib "eagle-import") (part "SSR_COTO_C334S"))
    )
    (comp (ref "SSR_7J/8A")
      (value "SSR_COTO_C334S")
      (footprint "eagle-import:SOP8")
      (libsource (lib "eagle-import") (part "SSR_COTO_C334S"))
    )
    (comp (ref "SSR_8BC")
      (value "SSR_COTO_C334S")
      (footprint "eagle-import:SOP8")
      (libsource (lib "eagle-import") (part "SSR_COTO_C334S"))
    )
    (comp (ref "SSR_8DE")
      (value "SSR_COTO_C334S")
      (footprint "eagle-import:SOP8")
      (libsource (lib "eagle-import") (part "SSR_COTO_C334S"))
    )
    (comp (ref "SSR_8FG")
      (value "SSR_COTO_C334S")
      (footprint "eagle-import:SOP8")
      (libsource (lib "eagle-import") (part "SSR_COTO_C334S"))
    )
    (comp (ref "SSR_8HJ")
      (value "SSR_COTO_C334S")
      (footprint "eagle-import:SOP8")
      (libsource (lib "eagle-import") (part "SSR_COTO_C334S"))
    )
  )
  (nets
    (net (code "1") (name "+5V") (class "Default")
      (node (ref "ARDUINO_A") (pin "15") (pinfunction "15_15") (pintype "passive"))
      (node (ref "CVDD1") (pin "1") (pinfunction "1_1") (pintype "passive"))
      (node (ref "CVDD2") (pin "1") (pinfunction "1_1") (pintype "passive"))
      (node (ref "CVDD3") (pin "1") (pinfunction "1_1") (pintype "passive"))
      (node (ref "CVDD4") (pin "1") (pinfunction "1_1") (pintype "passive"))
      (node (ref "CVDD5") (pin "1") (pinfunction "1_1") (pintype "passive"))
      (node (ref "CVDD6") (pin "1") (pinfunction "1_1") (pintype "passive"))
      (node (ref "CVDD7") (pin "1") (pinfunction "1_1") (pintype "passive"))
      (node (ref "CVDD8") (pin "1") (pinfunction "1_1") (pintype "passive"))
      (node (ref "C_SUP1") (pin "A") (pinfunction "+_A") (pintype "passive"))
      (node (ref "C_SUP2") (pin "1") (pinfunction "1_1") (pintype "passive"))
      (node (ref "DRV1") (pin "2") (pinfunction "VDD_2") (pintype "bidirectional"))
      (node (ref "DRV2") (pin "2") (pinfunction "VDD_2") (pintype "bidirectional"))
      (node (ref "DRV3") (pin "2") (pinfunction "VDD_2") (pintype "bidirectional"))
      (node (ref "DRV4") (pin "2") (pinfunction "VDD_2") (pintype "bidirectional"))
      (node (ref "DRV5") (pin "2") (pinfunction "VDD_2") (pintype "bidirectional"))
      (node (ref "DRV6") (pin "2") (pinfunction "VDD_2") (pintype "bidirectional"))
      (node (ref "DRV7") (pin "2") (pinfunction "VDD_2") (pintype "bidirectional"))
      (node (ref "DRV8") (pin "2") (pinfunction "VDD_2") (pintype "bidirectional"))
      (node (ref "HEADER_EXT") (pin "2") (pinfunction "2_2") (pintype "passive"))
      (node (ref "I2C_SWITCH") (pin "24") (pinfunction "VDD_24") (pintype "bidirectional"))
      (node (ref "L1") (pin "2") (pinfunction "2_2") (pintype "passive"))
      (node (ref "L2") (pin "2") (pinfunction "2_2") (pintype "passive"))
      (node (ref "L3") (pin "2") (pinfunction "2_2") (pintype "passive"))
      (node (ref "L4") (pin "2") (pinfunction "2_2") (pintype "passive"))
      (node (ref "L5") (pin "2") (pinfunction "2_2") (pintype "passive"))
      (node (ref "L6") (pin "2") (pinfunction "2_2") (pintype "passive"))
      (node (ref "L7") (pin "2") (pinfunction "2_2") (pintype "passive"))
      (node (ref "L8") (pin "2") (pinfunction "2_2") (pintype "passive"))
      (node (ref "LED1") (pin "A") (pinfunction "A_A") (pintype "passive"))
      (node (ref "LED2") (pin "A") (pinfunction "A_A") (pintype "passive"))
      (node (ref "LED3") (pin "A") (pinfunction "A_A") (pintype "passive"))
      (node (ref "PWR:") (pin "3") (pinfunction "PWR_1_3") (pintype "power_in"))
      (node (ref "PWR:") (pin "4") (pinfunction "PWR_2_4") (pintype "power_in"))
      (node (ref "RLED_SUP") (pin "2") (pinfunction "2_2") (pintype "passive"))
      (node (ref "R_1A") (pin "2") (pinfunction "2_2") (pintype "passive"))
      (node (ref "R_1B") (pin "2") (pinfunction "2_2") (pintype "passive"))
      (node (ref "R_1C") (pin "2") (pinfunction "2_2") (pintype "passive"))
      (node (ref "R_1D") (pin "2") (pinfunction "2_2") (pintype "passive"))
      (node (ref "R_1E") (pin "2") (pinfunction "2_2") (pintype "passive"))
      (node (ref "R_1F") (pin "2") (pinfunction "2_2") (pintype "passive"))
      (node (ref "R_1G") (pin "2") (pinfunction "2_2") (pintype "passive"))
      (node (ref "R_1H") (pin "2") (pinfunction "2_2") (pintype "passive"))
      (node (ref "R_1J") (pin "2") (pinfunction "2_2") (pintype "passive"))
      (node (ref "R_2A") (pin "2") (pinfunction "2_2") (pintype "passive"))
      (node (ref "R_2B") (pin "2") (pinfunction "2_2") (pintype "passive"))
      (node (ref "R_2C") (pin "2") (pinfunction "2_2") (pintype "passive"))
      (node (ref "R_2D") (pin "2") (pinfunction "2_2") (pintype "passive"))
      (node (ref "R_2E") (pin "2") (pinfunction "2_2") (pintype "passive"))
      (node (ref "R_2F") (pin "2") (pinfunction "2_2") (pintype "passive"))
      (node (ref "R_2G") (pin "2") (pinfunction "2_2") (pintype "passive"))
      (node (ref "R_2H") (pin "2") (pinfunction "2_2") (pintype "passive"))
      (node (ref "R_2J") (pin "2") (pinfunction "2_2") (pintype "passive"))
      (node (ref "R_3A") (pin "2") (pinfunction "2_2") (pintype "passive"))
      (node (ref "R_3B") (pin "2") (pinfunction "2_2") (pintype "passive"))
      (node (ref "R_3C") (pin "2") (pinfunction "2_2") (pintype "passive"))
      (node (ref "R_3D") (pin "2") (pinfunction "2_2") (pintype "passive"))
      (node (ref "R_3E") (pin "2") (pinfunction "2_2") (pintype "passive"))
      (node (ref "R_3F") (pin "2") (pinfunction "2_2") (pintype "passive"))
      (node (ref "R_3G") (pin "2") (pinfunction "2_2") (pintype "passive"))
      (node (ref "R_3H") (pin "2") (pinfunction "2_2") (pintype "passive"))
      (node (ref "R_3J") (pin "2") (pinfunction "2_2") (pintype "passive"))
      (node (ref "R_4A") (pin "2") (pinfunction "2_2") (pintype "passive"))
      (node (ref "R_4B") (pin "2") (pinfunction "2_2") (pintype "passive"))
      (node (ref "R_4C") (pin "2") (pinfunction "2_2") (pintype "passive"))
      (node (ref "R_4D") (pin "2") (pinfunction "2_2") (pintype "passive"))
      (node (ref "R_4E") (pin "2") (pinfunction "2_2") (pintype "passive"))
      (node (ref "R_4F") (pin "2") (pinfunction "2_2") (pintype "passive"))
      (node (ref "R_4G") (pin "2") (pinfunction "2_2") (pintype "passive"))
      (node (ref "R_4H") (pin "2") (pinfunction "2_2") (pintype "passive"))
      (node (ref "R_4J") (pin "2") (pinfunction "2_2") (pintype "passive"))
      (node (ref "R_5A") (pin "2") (pinfunction "2_2") (pintype "passive"))
      (node (ref "R_5B") (pin "2") (pinfunction "2_2") (pintype "passive"))
      (node (ref "R_5C") (pin "2") (pinfunction "2_2") (pintype "passive"))
      (node (ref "R_5D") (pin "2") (pinfunction "2_2") (pintype "passive"))
      (node (ref "R_5E") (pin "2") (pinfunction "2_2") (pintype "passive"))
      (node (ref "R_5F") (pin "2") (pinfunction "2_2") (pintype "passive"))
      (node (ref "R_5G") (pin "2") (pinfunction "2_2") (pintype "passive"))
      (node (ref "R_5H") (pin "2") (pinfunction "2_2") (pintype "passive"))
      (node (ref "R_5J") (pin "2") (pinfunction "2_2") (pintype "passive"))
      (node (ref "R_6A") (pin "2") (pinfunction "2_2") (pintype "passive"))
      (node (ref "R_6B") (pin "2") (pinfunction "2_2") (pintype "passive"))
      (node (ref "R_6C") (pin "2") (pinfunction "2_2") (pintype "passive"))
      (node (ref "R_6D") (pin "2") (pinfunction "2_2") (pintype "passive"))
      (node (ref "R_6E") (pin "2") (pinfunction "2_2") (pintype "passive"))
      (node (ref "R_6F") (pin "2") (pinfunction "2_2") (pintype "passive"))
      (node (ref "R_6G") (pin "2") (pinfunction "2_2") (pintype "passive"))
      (node (ref "R_6H") (pin "2") (pinfunction "2_2") (pintype "passive"))
      (node (ref "R_6J") (pin "2") (pinfunction "2_2") (pintype "passive"))
      (node (ref "R_7A") (pin "2") (pinfunction "2_2") (pintype "passive"))
      (node (ref "R_7B") (pin "2") (pinfunction "2_2") (pintype "passive"))
      (node (ref "R_7C") (pin "2") (pinfunction "2_2") (pintype "passive"))
      (node (ref "R_7D") (pin "2") (pinfunction "2_2") (pintype "passive"))
      (node (ref "R_7E") (pin "2") (pinfunction "2_2") (pintype "passive"))
      (node (ref "R_7F") (pin "2") (pinfunction "2_2") (pintype "passive"))
      (node (ref "R_7G") (pin "2") (pinfunction "2_2") (pintype "passive"))
      (node (ref "R_7H") (pin "2") (pinfunction "2_2") (pintype "passive"))
      (node (ref "R_7J") (pin "2") (pinfunction "2_2") (pintype "passive"))
      (node (ref "R_8A") (pin "2") (pinfunction "2_2") (pintype "passive"))
      (node (ref "R_8B") (pin "2") (pinfunction "2_2") (pintype "passive"))
      (node (ref "R_8C") (pin "2") (pinfunction "2_2") (pintype "passive"))
      (node (ref "R_8D") (pin "2") (pinfunction "2_2") (pintype "passive"))
      (node (ref "R_8E") (pin "2") (pinfunction "2_2") (pintype "passive"))
      (node (ref "R_8F") (pin "2") (pinfunction "2_2") (pintype "passive"))
      (node (ref "R_8G") (pin "2") (pinfunction "2_2") (pintype "passive"))
      (node (ref "R_8H") (pin "2") (pinfunction "2_2") (pintype "passive"))
      (node (ref "R_8J") (pin "2") (pinfunction "2_2") (pintype "passive"))
      (node (ref "R_CLR") (pin "2") (pinfunction "2_2") (pintype "passive"))
      (node (ref "R_LIFT2") (pin "2") (pinfunction "2_2") (pintype "passive"))
      (node (ref "R_OE") (pin "2") (pinfunction "2_2") (pintype "passive"))
      (node (ref "R_RST") (pin "2") (pinfunction "2_2") (pintype "passive"))
      (node (ref "R_SCL") (pin "2") (pinfunction "2_2") (pintype "passive"))
      (node (ref "R_SCL1") (pin "2") (pinfunction "2_2") (pintype "passive"))
      (node (ref "R_SCL2") (pin "2") (pinfunction "2_2") (pintype "passive"))
      (node (ref "R_SCL3") (pin "2") (pinfunction "2_2") (pintype "passive"))
      (node (ref "R_SCL4") (pin "2") (pinfunction "2_2") (pintype "passive"))
      (node (ref "R_SCL5") (pin "2") (pinfunction "2_2") (pintype "passive"))
      (node (ref "R_SCL6") (pin "2") (pinfunction "2_2") (pintype "passive"))
      (node (ref "R_SCL7") (pin "2") (pinfunction "2_2") (pintype "passive"))
      (node (ref "R_SCL8") (pin "2") (pinfunction "2_2") (pintype "passive"))
      (node (ref "R_SDA") (pin "2") (pinfunction "2_2") (pintype "passive"))
      (node (ref "R_SDA1") (pin "2") (pinfunction "2_2") (pintype "passive"))
      (node (ref "R_SDA2") (pin "2") (pinfunction "2_2") (pintype "passive"))
      (node (ref "R_SDA3") (pin "2") (pinfunction "2_2") (pintype "passive"))
      (node (ref "R_SDA4") (pin "2") (pinfunction "2_2") (pintype "passive"))
      (node (ref "R_SDA5") (pin "2") (pinfunction "2_2") (pintype "passive"))
      (node (ref "R_SDA6") (pin "2") (pinfunction "2_2") (pintype "passive"))
      (node (ref "R_SDA7") (pin "2") (pinfunction "2_2") (pintype "passive"))
      (node (ref "R_SDA8") (pin "2") (pinfunction "2_2") (pintype "passive"))
      (node (ref "SHIFTER0") (pin "16") (pinfunction "VCC_16") (pintype "power_in"))
      (node (ref "SHIFTER1") (pin "16") (pinfunction "VCC_16") (pintype "power_in"))
      (node (ref "SHIFTER2") (pin "16") (pinfunction "VCC_16") (pintype "power_in"))
      (node (ref "SHIFTER3") (pin "16") (pinfunction "VCC_16") (pintype "power_in"))
      (node (ref "SHIFTER4") (pin "16") (pinfunction "VCC_16") (pintype "power_in"))
      (node (ref "SHIFTER5") (pin "16") (pinfunction "VCC_16") (pintype "power_in"))
      (node (ref "SHIFTER6") (pin "16") (pinfunction "VCC_16") (pintype "power_in"))
      (node (ref "SHIFTER7") (pin "16") (pinfunction "VCC_16") (pintype "power_in"))
      (node (ref "SHIFTER8") (pin "16") (pinfunction "VCC_16") (pintype "power_in"))
    )
    (net (code "2") (name "0V") (class "Default")
      (node (ref "ARDUINO_A") (pin "14") (pinfunction "14_14") (pintype "passive"))
      (node (ref "ARDUINO_D") (pin "12") (pinfunction "12_12") (pintype "passive"))
      (node (ref "AUDIO_IN") (pin "G1") (pinfunction "G1_G1") (pintype "passive"))
      (node (ref "AUDIO_IN") (pin "G2") (pinfunction "G2_G2") (pintype "passive"))
      (node (ref "CPUMP1") (pin "2") (pinfunction "2_2") (pintype "passive"))
      (node (ref "CPUMP2") (pin "2") (pinfunction "2_2") (pintype "passive"))
      (node (ref "CPUMP3") (pin "2") (pinfunction "2_2") (pintype "passive"))
      (node (ref "CPUMP4") (pin "2") (pinfunction "2_2") (pintype "passive"))
      (node (ref "CPUMP5") (pin "2") (pinfunction "2_2") (pintype "passive"))
      (node (ref "CPUMP6") (pin "2") (pinfunction "2_2") (pintype "passive"))
      (node (ref "CPUMP7") (pin "2") (pinfunction "2_2") (pintype "passive"))
      (node (ref "CPUMP8") (pin "2") (pinfunction "2_2") (pintype "passive"))
      (node (ref "CVBST1") (pin "2") (pinfunction "2_2") (pintype "passive"))
      (node (ref "CVBST2") (pin "2") (pinfunction "2_2") (pintype "passive"))
      (node (ref "CVBST3") (pin "2") (pinfunction "2_2") (pintype "passive"))
      (node (ref "CVBST4") (pin "2") (pinfunction "2_2") (pintype "passive"))
      (node (ref "CVBST5") (pin "2") (pinfunction "2_2") (pintype "passive"))
      (node (ref "CVBST6") (pin "2") (pinfunction "2_2") (pintype "passive"))
      (node (ref "CVBST7") (pin "2") (pinfunction "2_2") (pintype "passive"))
      (node (ref "CVBST8") (pin "2") (pinfunction "2_2") (pintype "passive"))
      (node (ref "CVDD1") (pin "2") (pinfunction "2_2") (pintype "passive"))
      (node (ref "CVDD2") (pin "2") (pinfunction "2_2") (pintype "passive"))
      (node (ref "CVDD3") (pin "2") (pinfunction "2_2") (pintype "passive"))
      (node (ref "CVDD4") (pin "2") (pinfunction "2_2") (pintype "passive"))
      (node (ref "CVDD5") (pin "2") (pinfunction "2_2") (pintype "passive"))
      (node (ref "CVDD6") (pin "2") (pinfunction "2_2") (pintype "passive"))
      (node (ref "CVDD7") (pin "2") (pinfunction "2_2") (pintype "passive"))
      (node (ref "CVDD8") (pin "2") (pinfunction "2_2") (pintype "passive"))
      (node (ref "CVREG1") (pin "2") (pinfunction "2_2") (pintype "passive"))
      (node (ref "CVREG2") (pin "2") (pinfunction "2_2") (pintype "passive"))
      (node (ref "CVREG3") (pin "2") (pinfunction "2_2") (pintype "passive"))
      (node (ref "CVREG4") (pin "2") (pinfunction "2_2") (pintype "passive"))
      (node (ref "CVREG5") (pin "2") (pinfunction "2_2") (pintype "passive"))
      (node (ref "CVREG6") (pin "2") (pinfunction "2_2") (pintype "passive"))
      (node (ref "CVREG7") (pin "2") (pinfunction "2_2") (pintype "passive"))
      (node (ref "CVREG8") (pin "2") (pinfunction "2_2") (pintype "passive"))
      (node (ref "C_SUP1") (pin "C") (pinfunction "-_C") (pintype "passive"))
      (node (ref "C_SUP2") (pin "2") (pinfunction "2_2") (pintype "passive"))
      (node (ref "DRV1") (pin "4") (pinfunction "GND_4") (pintype "bidirectional"))
      (node (ref "DRV1") (pin "5") (pinfunction "GND_5") (pintype "bidirectional"))
      (node (ref "DRV1") (pin "6") (pinfunction "GND_6") (pintype "bidirectional"))
      (node (ref "DRV1") (pin "PAD1") (pinfunction "PAD_PAD1") (pintype "bidirectional"))
      (node (ref "DRV1") (pin "PAD2") (pinfunction "PAD_PAD2") (pintype "bidirectional"))
      (node (ref "DRV1") (pin "PAD3") (pinfunction "PAD_PAD3") (pintype "bidirectional"))
      (node (ref "DRV1") (pin "PAD4") (pinfunction "PAD_PAD4") (pintype "bidirectional"))
      (node (ref "DRV1") (pin "PAD5") (pinfunction "PAD_PAD5") (pintype "bidirectional"))
      (node (ref "DRV1") (pin "PAD6") (pinfunction "PAD_PAD6") (pintype "bidirectional"))
      (node (ref "DRV1") (pin "PAD7") (pinfunction "PAD_PAD7") (pintype "bidirectional"))
      (node (ref "DRV1") (pin "PAD8") (pinfunction "PAD_PAD8") (pintype "bidirectional"))
      (node (ref "DRV1") (pin "PAD9") (pinfunction "PAD_PAD9") (pintype "bidirectional"))
      (node (ref "DRV2") (pin "4") (pinfunction "GND_4") (pintype "bidirectional"))
      (node (ref "DRV2") (pin "5") (pinfunction "GND_5") (pintype "bidirectional"))
      (node (ref "DRV2") (pin "6") (pinfunction "GND_6") (pintype "bidirectional"))
      (node (ref "DRV2") (pin "PAD1") (pinfunction "PAD_PAD1") (pintype "bidirectional"))
      (node (ref "DRV2") (pin "PAD2") (pinfunction "PAD_PAD2") (pintype "bidirectional"))
      (node (ref "DRV2") (pin "PAD3") (pinfunction "PAD_PAD3") (pintype "bidirectional"))
      (node (ref "DRV2") (pin "PAD4") (pinfunction "PAD_PAD4") (pintype "bidirectional"))
      (node (ref "DRV2") (pin "PAD5") (pinfunction "PAD_PAD5") (pintype "bidirectional"))
      (node (ref "DRV2") (pin "PAD6") (pinfunction "PAD_PAD6") (pintype "bidirectional"))
      (node (ref "DRV2") (pin "PAD7") (pinfunction "PAD_PAD7") (pintype "bidirectional"))
      (node (ref "DRV2") (pin "PAD8") (pinfunction "PAD_PAD8") (pintype "bidirectional"))
      (node (ref "DRV2") (pin "PAD9") (pinfunction "PAD_PAD9") (pintype "bidirectional"))
      (node (ref "DRV3") (pin "4") (pinfunction "GND_4") (pintype "bidirectional"))
      (node (ref "DRV3") (pin "5") (pinfunction "GND_5") (pintype "bidirectional"))
      (node (ref "DRV3") (pin "6") (pinfunction "GND_6") (pintype "bidirectional"))
      (node (ref "DRV3") (pin "PAD1") (pinfunction "PAD_PAD1") (pintype "bidirectional"))
      (node (ref "DRV3") (pin "PAD2") (pinfunction "PAD_PAD2") (pintype "bidirectional"))
      (node (ref "DRV3") (pin "PAD3") (pinfunction "PAD_PAD3") (pintype "bidirectional"))
      (node (ref "DRV3") (pin "PAD4") (pinfunction "PAD_PAD4") (pintype "bidirectional"))
      (node (ref "DRV3") (pin "PAD5") (pinfunction "PAD_PAD5") (pintype "bidirectional"))
      (node (ref "DRV3") (pin "PAD6") (pinfunction "PAD_PAD6") (pintype "bidirectional"))
      (node (ref "DRV3") (pin "PAD7") (pinfunction "PAD_PAD7") (pintype "bidirectional"))
      (node (ref "DRV3") (pin "PAD8") (pinfunction "PAD_PAD8") (pintype "bidirectional"))
      (node (ref "DRV3") (pin "PAD9") (pinfunction "PAD_PAD9") (pintype "bidirectional"))
      (node (ref "DRV4") (pin "4") (pinfunction "GND_4") (pintype "bidirectional"))
      (node (ref "DRV4") (pin "5") (pinfunction "GND_5") (pintype "bidirectional"))
      (node (ref "DRV4") (pin "6") (pinfunction "GND_6") (pintype "bidirectional"))
      (node (ref "DRV4") (pin "PAD1") (pinfunction "PAD_PAD1") (pintype "bidirectional"))
      (node (ref "DRV4") (pin "PAD2") (pinfunction "PAD_PAD2") (pintype "bidirectional"))
      (node (ref "DRV4") (pin "PAD3") (pinfunction "PAD_PAD3") (pintype "bidirectional"))
      (node (ref "DRV4") (pin "PAD4") (pinfunction "PAD_PAD4") (pintype "bidirectional"))
      (node (ref "DRV4") (pin "PAD5") (pinfunction "PAD_PAD5") (pintype "bidirectional"))
      (node (ref "DRV4") (pin "PAD6") (pinfunction "PAD_PAD6") (pintype "bidirectional"))
      (node (ref "DRV4") (pin "PAD7") (pinfunction "PAD_PAD7") (pintype "bidirectional"))
      (node (ref "DRV4") (pin "PAD8") (pinfunction "PAD_PAD8") (pintype "bidirectional"))
      (node (ref "DRV4") (pin "PAD9") (pinfunction "PAD_PAD9") (pintype "bidirectional"))
      (node (ref "DRV5") (pin "4") (pinfunction "GND_4") (pintype "bidirectional"))
      (node (ref "DRV5") (pin "5") (pinfunction "GND_5") (pintype "bidirectional"))
      (node (ref "DRV5") (pin "6") (pinfunction "GND_6") (pintype "bidirectional"))
      (node (ref "DRV5") (pin "PAD1") (pinfunction "PAD_PAD1") (pintype "bidirectional"))
      (node (ref "DRV5") (pin "PAD2") (pinfunction "PAD_PAD2") (pintype "bidirectional"))
      (node (ref "DRV5") (pin "PAD3") (pinfunction "PAD_PAD3") (pintype "bidirectional"))
      (node (ref "DRV5") (pin "PAD4") (pinfunction "PAD_PAD4") (pintype "bidirectional"))
      (node (ref "DRV5") (pin "PAD5") (pinfunction "PAD_PAD5") (pintype "bidirectional"))
      (node (ref "DRV5") (pin "PAD6") (pinfunction "PAD_PAD6") (pintype "bidirectional"))
      (node (ref "DRV5") (pin "PAD7") (pinfunction "PAD_PAD7") (pintype "bidirectional"))
      (node (ref "DRV5") (pin "PAD8") (pinfunction "PAD_PAD8") (pintype "bidirectional"))
      (node (ref "DRV5") (pin "PAD9") (pinfunction "PAD_PAD9") (pintype "bidirectional"))
      (node (ref "DRV6") (pin "4") (pinfunction "GND_4") (pintype "bidirectional"))
      (node (ref "DRV6") (pin "5") (pinfunction "GND_5") (pintype "bidirectional"))
      (node (ref "DRV6") (pin "6") (pinfunction "GND_6") (pintype "bidirectional"))
      (node (ref "DRV6") (pin "PAD1") (pinfunction "PAD_PAD1") (pintype "bidirectional"))
      (node (ref "DRV6") (pin "PAD2") (pinfunction "PAD_PAD2") (pintype "bidirectional"))
      (node (ref "DRV6") (pin "PAD3") (pinfunction "PAD_PAD3") (pintype "bidirectional"))
      (node (ref "DRV6") (pin "PAD4") (pinfunction "PAD_PAD4") (pintype "bidirectional"))
      (node (ref "DRV6") (pin "PAD5") (pinfunction "PAD_PAD5") (pintype "bidirectional"))
      (node (ref "DRV6") (pin "PAD6") (pinfunction "PAD_PAD6") (pintype "bidirectional"))
      (node (ref "DRV6") (pin "PAD7") (pinfunction "PAD_PAD7") (pintype "bidirectional"))
      (node (ref "DRV6") (pin "PAD8") (pinfunction "PAD_PAD8") (pintype "bidirectional"))
      (node (ref "DRV6") (pin "PAD9") (pinfunction "PAD_PAD9") (pintype "bidirectional"))
      (node (ref "DRV7") (pin "4") (pinfunction "GND_4") (pintype "bidirectional"))
      (node (ref "DRV7") (pin "5") (pinfunction "GND_5") (pintype "bidirectional"))
      (node (ref "DRV7") (pin "6") (pinfunction "GND_6") (pintype "bidirectional"))
      (node (ref "DRV7") (pin "PAD1") (pinfunction "PAD_PAD1") (pintype "bidirectional"))
      (node (ref "DRV7") (pin "PAD2") (pinfunction "PAD_PAD2") (pintype "bidirectional"))
      (node (ref "DRV7") (pin "PAD3") (pinfunction "PAD_PAD3") (pintype "bidirectional"))
      (node (ref "DRV7") (pin "PAD4") (pinfunction "PAD_PAD4") (pintype "bidirectional"))
      (node (ref "DRV7") (pin "PAD5") (pinfunction "PAD_PAD5") (pintype "bidirectional"))
      (node (ref "DRV7") (pin "PAD6") (pinfunction "PAD_PAD6") (pintype "bidirectional"))
      (node (ref "DRV7") (pin "PAD7") (pinfunction "PAD_PAD7") (pintype "bidirectional"))
      (node (ref "DRV7") (pin "PAD8") (pinfunction "PAD_PAD8") (pintype "bidirectional"))
      (node (ref "DRV7") (pin "PAD9") (pinfunction "PAD_PAD9") (pintype "bidirectional"))
      (node (ref "DRV8") (pin "4") (pinfunction "GND_4") (pintype "bidirectional"))
      (node (ref "DRV8") (pin "5") (pinfunction "GND_5") (pintype "bidirectional"))
      (node (ref "DRV8") (pin "6") (pinfunction "GND_6") (pintype "bidirectional"))
      (node (ref "DRV8") (pin "PAD1") (pinfunction "PAD_PAD1") (pintype "bidirectional"))
      (node (ref "DRV8") (pin "PAD2") (pinfunction "PAD_PAD2") (pintype "bidirectional"))
      (node (ref "DRV8") (pin "PAD3") (pinfunction "PAD_PAD3") (pintype "bidirectional"))
      (node (ref "DRV8") (pin "PAD4") (pinfunction "PAD_PAD4") (pintype "bidirectional"))
      (node (ref "DRV8") (pin "PAD5") (pinfunction "PAD_PAD5") (pintype "bidirectional"))
      (node (ref "DRV8") (pin "PAD6") (pinfunction "PAD_PAD6") (pintype "bidirectional"))
      (node (ref "DRV8") (pin "PAD7") (pinfunction "PAD_PAD7") (pintype "bidirectional"))
      (node (ref "DRV8") (pin "PAD8") (pinfunction "PAD_PAD8") (pintype "bidirectional"))
      (node (ref "DRV8") (pin "PAD9") (pinfunction "PAD_PAD9") (pintype "bidirectional"))
      (node (ref "HEADER_EXT") (pin "1") (pinfunction "1_1") (pintype "passive"))
      (node (ref "HEADER_EXT") (pin "12") (pinfunction "12_12") (pintype "passive"))
      (node (ref "I2C_SWITCH") (pin "12") (pinfunction "VSS_12") (pintype "bidirectional"))
      (node (ref "LED_SUP") (pin "C") (pinfunction "C_C") (pintype "passive"))
      (node (ref "PWR:") (pin "1") (pinfunction "GND_1") (pintype "power_in"))
      (node (ref "PWR:") (pin "2") (pinfunction "GND_INS_2") (pintype "power_in"))
      (node (ref "REXT1") (pin "1") (pinfunction "1_1") (pintype "passive"))
      (node (ref "REXT2") (pin "1") (pinfunction "1_1") (pintype "passive"))
      (node (ref "REXT3") (pin "1") (pinfunction "1_1") (pintype "passive"))
      (node (ref "REXT4") (pin "1") (pinfunction "1_1") (pintype "passive"))
      (node (ref "REXT5") (pin "1") (pinfunction "1_1") (pintype "passive"))
      (node (ref "REXT6") (pin "1") (pinfunction "1_1") (pintype "passive"))
      (node (ref "REXT7") (pin "1") (pinfunction "1_1") (pintype "passive"))
      (node (ref "REXT8") (pin "1") (pinfunction "1_1") (pintype "passive"))
      (node (ref "RVBST1-2") (pin "1") (pinfunction "1_1") (pintype "passive"))
      (node (ref "RVBST2-2") (pin "1") (pinfunction "1_1") (pintype "passive"))
      (node (ref "RVBST3-2") (pin "1") (pinfunction "1_1") (pintype "passive"))
      (node (ref "RVBST4-2") (pin "1") (pinfunction "1_1") (pintype "passive"))
      (node (ref "RVBST5-2") (pin "1") (pinfunction "1_1") (pintype "passive"))
      (node (ref "RVBST6-2") (pin "1") (pinfunction "1_1") (pintype "passive"))
      (node (ref "RVBST7-2") (pin "1") (pinfunction "1_1") (pintype "passive"))
      (node (ref "RVBST8-2") (pin "1") (pinfunction "1_1") (pintype "passive"))
      (node (ref "R_LIFT1") (pin "1") (pinfunction "1_1") (pintype "passive"))
      (node (ref "R_LOAD") (pin "1") (pinfunction "1_1") (pintype "passive"))
      (node (ref "SHIFTER0") (pin "8") (pinfunction "GND_8") (pintype "power_in"))
      (node (ref "SHIFTER0") (pin "PAD") (pinfunction "GND_PAD") (pintype "power_in"))
      (node (ref "SHIFTER1") (pin "8") (pinfunction "GND_8") (pintype "power_in"))
      (node (ref "SHIFTER1") (pin "PAD") (pinfunction "GND_PAD") (pintype "power_in"))
      (node (ref "SHIFTER2") (pin "8") (pinfunction "GND_8") (pintype "power_in"))
      (node (ref "SHIFTER2") (pin "PAD") (pinfunction "GND_PAD") (pintype "power_in"))
      (node (ref "SHIFTER3") (pin "8") (pinfunction "GND_8") (pintype "power_in"))
      (node (ref "SHIFTER3") (pin "PAD") (pinfunction "GND_PAD") (pintype "power_in"))
      (node (ref "SHIFTER4") (pin "8") (pinfunction "GND_8") (pintype "power_in"))
      (node (ref "SHIFTER4") (pin "PAD") (pinfunction "GND_PAD") (pintype "power_in"))
      (node (ref "SHIFTER5") (pin "8") (pinfunction "GND_8") (pintype "power_in"))
      (node (ref "SHIFTER5") (pin "PAD") (pinfunction "GND_PAD") (pintype "power_in"))
      (node (ref "SHIFTER6") (pin "8") (pinfunction "GND_8") (pintype "power_in"))
      (node (ref "SHIFTER6") (pin "PAD") (pinfunction "GND_PAD") (pintype "power_in"))
      (node (ref "SHIFTER7") (pin "8") (pinfunction "GND_8") (pintype "power_in"))
      (node (ref "SHIFTER7") (pin "PAD") (pinfunction "GND_PAD") (pintype "power_in"))
      (node (ref "SHIFTER8") (pin "8") (pinfunction "GND_8") (pintype "power_in"))
      (node (ref "SHIFTER8") (pin "PAD") (pinfunction "GND_PAD") (pintype "power_in"))
    )
    (net (code "3") (name "CH1_I+") (class "Default")
      (node (ref "AUDIO_IN") (pin "24") (pinfunction "24_24") (pintype "passive"))
      (node (ref "DRV1") (pin "17") (pinfunction "IN+_17") (pintype "bidirectional"))
    )
    (net (code "4") (name "CH1_I-") (class "Default")
      (node (ref "AUDIO_IN") (pin "12") (pinfunction "12_12") (pintype "passive"))
      (node (ref "DRV1") (pin "16") (pinfunction "IN-_16") (pintype "bidirectional"))
    )
    (net (code "5") (name "CH1_O+") (class "Default")
      (node (ref "DRV1") (pin "13") (pinfunction "OUT+_13") (pintype "bidirectional"))
      (node (ref "SSR_1AB") (pin "5") (pinfunction "O1_5") (pintype "bidirectional"))
      (node (ref "SSR_1AB") (pin "7") (pinfunction "O1_7") (pintype "bidirectional"))
      (node (ref "SSR_1CD") (pin "5") (pinfunction "O1_5") (pintype "bidirectional"))
      (node (ref "SSR_1CD") (pin "7") (pinfunction "O1_7") (pintype "bidirectional"))
      (node (ref "SSR_1EF") (pin "5") (pinfunction "O1_5") (pintype "bidirectional"))
      (node (ref "SSR_1EF") (pin "7") (pinfunction "O1_7") (pintype "bidirectional"))
      (node (ref "SSR_1GH") (pin "5") (pinfunction "O1_5") (pintype "bidirectional"))
      (node (ref "SSR_1GH") (pin "7") (pinfunction "O1_7") (pintype "bidirectional"))
      (node (ref "SSR_1J/2A") (pin "7") (pinfunction "O1_7") (pintype "bidirectional"))
    )
    (net (code "6") (name "CH1_O-") (class "Default")
      (node (ref "DRV1") (pin "14") (pinfunction "OUT-_14") (pintype "bidirectional"))
      (node (ref "P-CH1+2") (pin "12") (pinfunction "1_12") (pintype "passive"))
      (node (ref "P-CH1+2") (pin "18") (pinfunction "1_18") (pintype "passive"))
    )
    (net (code "7") (name "CH1_PA+") (class "Default")
      (node (ref "P-CH1+2") (pin "22") (pinfunction "1_22") (pintype "passive"))
      (node (ref "SSR_1AB") (pin "8") (pinfunction "O2_8") (pintype "bidirectional"))
    )
    (net (code "8") (name "CH1_PB+") (class "Default")
      (node (ref "P-CH1+2") (pin "21") (pinfunction "1_21") (pintype "passive"))
      (node (ref "SSR_1AB") (pin "6") (pinfunction "O2_6") (pintype "bidirectional"))
    )
    (net (code "9") (name "CH1_PC+") (class "Default")
      (node (ref "P-CH1+2") (pin "20") (pinfunction "1_20") (pintype "passive"))
      (node (ref "SSR_1CD") (pin "8") (pinfunction "O2_8") (pintype "bidirectional"))
    )
    (net (code "10") (name "CH1_PD+") (class "Default")
      (node (ref "P-CH1+2") (pin "19") (pinfunction "1_19") (pintype "passive"))
      (node (ref "SSR_1CD") (pin "6") (pinfunction "O2_6") (pintype "bidirectional"))
    )
    (net (code "11") (name "CH1_PE+") (class "Default")
      (node (ref "P-CH1+2") (pin "17") (pinfunction "1_17") (pintype "passive"))
      (node (ref "SSR_1EF") (pin "8") (pinfunction "O2_8") (pintype "bidirectional"))
    )
    (net (code "12") (name "CH1_PF+") (class "Default")
      (node (ref "P-CH1+2") (pin "16") (pinfunction "1_16") (pintype "passive"))
      (node (ref "SSR_1EF") (pin "6") (pinfunction "O2_6") (pintype "bidirectional"))
    )
    (net (code "13") (name "CH1_PG+") (class "Default")
      (node (ref "P-CH1+2") (pin "15") (pinfunction "1_15") (pintype "passive"))
      (node (ref "SSR_1GH") (pin "8") (pinfunction "O2_8") (pintype "bidirectional"))
    )
    (net (code "14") (name "CH1_PH+") (class "Default")
      (node (ref "P-CH1+2") (pin "14") (pinfunction "1_14") (pintype "passive"))
      (node (ref "SSR_1GH") (pin "6") (pinfunction "O2_6") (pintype "bidirectional"))
    )
    (net (code "15") (name "CH1_PJ+") (class "Default")
      (node (ref "P-CH1+2") (pin "13") (pinfunction "1_13") (pintype "passive"))
      (node (ref "SSR_1J/2A") (pin "8") (pinfunction "O2_8") (pintype "bidirectional"))
    )
    (net (code "16") (name "CH2_I+") (class "Default")
      (node (ref "AUDIO_IN") (pin "10") (pinfunction "10_10") (pintype "passive"))
      (node (ref "DRV2") (pin "17") (pinfunction "IN+_17") (pintype "bidirectional"))
    )
    (net (code "17") (name "CH2_I-") (class "Default")
      (node (ref "AUDIO_IN") (pin "23") (pinfunction "23_23") (pintype "passive"))
      (node (ref "DRV2") (pin "16") (pinfunction "IN-_16") (pintype "bidirectional"))
    )
    (net (code "18") (name "CH2_O+") (class "Default")
      (node (ref "DRV2") (pin "13") (pinfunction "OUT+_13") (pintype "bidirectional"))
      (node (ref "SSR_1J/2A") (pin "5") (pinfunction "O1_5") (pintype "bidirectional"))
      (node (ref "SSR_2BC") (pin "5") (pinfunction "O1_5") (pintype "bidirectional"))
      (node (ref "SSR_2BC") (pin "7") (pinfunction "O1_7") (pintype "bidirectional"))
      (node (ref "SSR_2DE") (pin "5") (pinfunction "O1_5") (pintype "bidirectional"))
      (node (ref "SSR_2DE") (pin "7") (pinfunction "O1_7") (pintype "bidirectional"))
      (node (ref "SSR_2FG") (pin "5") (pinfunction "O1_5") (pintype "bidirectional"))
      (node (ref "SSR_2FG") (pin "7") (pinfunction "O1_7") (pintype "bidirectional"))
      (node (ref "SSR_2HJ") (pin "5") (pinfunction "O1_5") (pintype "bidirectional"))
      (node (ref "SSR_2HJ") (pin "7") (pinfunction "O1_7") (pintype "bidirectional"))
    )
    (net (code "19") (name "CH2_O-") (class "Default")
      (node (ref "DRV2") (pin "14") (pinfunction "OUT-_14") (pintype "bidirectional"))
      (node (ref "P-CH1+2") (pin "1") (pinfunction "1_1") (pintype "passive"))
      (node (ref "P-CH1+2") (pin "7") (pinfunction "1_7") (pintype "passive"))
    )
    (net (code "20") (name "CH2_PA+") (class "Default")
      (node (ref "P-CH1+2") (pin "11") (pinfunction "1_11") (pintype "passive"))
      (node (ref "SSR_1J/2A") (pin "6") (pinfunction "O2_6") (pintype "bidirectional"))
    )
    (net (code "21") (name "CH2_PB+") (class "Default")
      (node (ref "P-CH1+2") (pin "10") (pinfunction "1_10") (pintype "passive"))
      (node (ref "SSR_2BC") (pin "8") (pinfunction "O2_8") (pintype "bidirectional"))
    )
    (net (code "22") (name "CH2_PC+") (class "Default")
      (node (ref "P-CH1+2") (pin "9") (pinfunction "1_9") (pintype "passive"))
      (node (ref "SSR_2BC") (pin "6") (pinfunction "O2_6") (pintype "bidirectional"))
    )
    (net (code "23") (name "CH2_PD+") (class "Default")
      (node (ref "P-CH1+2") (pin "8") (pinfunction "1_8") (pintype "passive"))
      (node (ref "SSR_2DE") (pin "8") (pinfunction "O2_8") (pintype "bidirectional"))
    )
    (net (code "24") (name "CH2_PE+") (class "Default")
      (node (ref "P-CH1+2") (pin "6") (pinfunction "1_6") (pintype "passive"))
      (node (ref "SSR_2DE") (pin "6") (pinfunction "O2_6") (pintype "bidirectional"))
    )
    (net (code "25") (name "CH2_PF+") (class "Default")
      (node (ref "P-CH1+2") (pin "5") (pinfunction "1_5") (pintype "passive"))
      (node (ref "SSR_2FG") (pin "8") (pinfunction "O2_8") (pintype "bidirectional"))
    )
    (net (code "26") (name "CH2_PG+") (class "Default")
      (node (ref "P-CH1+2") (pin "4") (pinfunction "1_4") (pintype "passive"))
      (node (ref "SSR_2FG") (pin "6") (pinfunction "O2_6") (pintype "bidirectional"))
    )
    (net (code "27") (name "CH2_PH+") (class "Default")
      (node (ref "P-CH1+2") (pin "3") (pinfunction "1_3") (pintype "passive"))
      (node (ref "SSR_2HJ") (pin "8") (pinfunction "O2_8") (pintype "bidirectional"))
    )
    (net (code "28") (name "CH2_PJ+") (class "Default")
      (node (ref "P-CH1+2") (pin "2") (pinfunction "1_2") (pintype "passive"))
      (node (ref "SSR_2HJ") (pin "6") (pinfunction "O2_6") (pintype "bidirectional"))
    )
    (net (code "29") (name "CH3_I+") (class "Default")
      (node (ref "AUDIO_IN") (pin "21") (pinfunction "21_21") (pintype "passive"))
      (node (ref "DRV3") (pin "17") (pinfunction "IN+_17") (pintype "bidirectional"))
    )
    (net (code "30") (name "CH3_I-") (class "Default")
      (node (ref "AUDIO_IN") (pin "9") (pinfunction "9_9") (pintype "passive"))
      (node (ref "DRV3") (pin "16") (pinfunction "IN-_16") (pintype "bidirectional"))
    )
    (net (code "31") (name "CH3_O+") (class "Default")
      (node (ref "DRV3") (pin "13") (pinfunction "OUT+_13") (pintype "bidirectional"))
      (node (ref "SSR_3AB") (pin "5") (pinfunction "O1_5") (pintype "bidirectional"))
      (node (ref "SSR_3AB") (pin "7") (pinfunction "O1_7") (pintype "bidirectional"))
      (node (ref "SSR_3CD") (pin "5") (pinfunction "O1_5") (pintype "bidirectional"))
      (node (ref "SSR_3CD") (pin "7") (pinfunction "O1_7") (pintype "bidirectional"))
      (node (ref "SSR_3EF") (pin "5") (pinfunction "O1_5") (pintype "bidirectional"))
      (node (ref "SSR_3EF") (pin "7") (pinfunction "O1_7") (pintype "bidirectional"))
      (node (ref "SSR_3GH") (pin "5") (pinfunction "O1_5") (pintype "bidirectional"))
      (node (ref "SSR_3GH") (pin "7") (pinfunction "O1_7") (pintype "bidirectional"))
      (node (ref "SSR_3J/4A") (pin "7") (pinfunction "O1_7") (pintype "bidirectional"))
    )
    (net (code "32") (name "CH3_O-") (class "Default")
      (node (ref "DRV3") (pin "14") (pinfunction "OUT-_14") (pintype "bidirectional"))
      (node (ref "P-CH3+4") (pin "12") (pinfunction "1_12") (pintype "passive"))
      (node (ref "P-CH3+4") (pin "18") (pinfunction "1_18") (pintype "passive"))
    )
    (net (code "33") (name "CH3_PA+") (class "Default")
      (node (ref "P-CH3+4") (pin "22") (pinfunction "1_22") (pintype "passive"))
      (node (ref "SSR_3AB") (pin "8") (pinfunction "O2_8") (pintype "bidirectional"))
    )
    (net (code "34") (name "CH3_PB+") (class "Default")
      (node (ref "P-CH3+4") (pin "21") (pinfunction "1_21") (pintype "passive"))
      (node (ref "SSR_3AB") (pin "6") (pinfunction "O2_6") (pintype "bidirectional"))
    )
    (net (code "35") (name "CH3_PC+") (class "Default")
      (node (ref "P-CH3+4") (pin "20") (pinfunction "1_20") (pintype "passive"))
      (node (ref "SSR_3CD") (pin "8") (pinfunction "O2_8") (pintype "bidirectional"))
    )
    (net (code "36") (name "CH3_PD+") (class "Default")
      (node (ref "P-CH3+4") (pin "19") (pinfunction "1_19") (pintype "passive"))
      (node (ref "SSR_3CD") (pin "6") (pinfunction "O2_6") (pintype "bidirectional"))
    )
    (net (code "37") (name "CH3_PE+") (class "Default")
      (node (ref "P-CH3+4") (pin "17") (pinfunction "1_17") (pintype "passive"))
      (node (ref "SSR_3EF") (pin "8") (pinfunction "O2_8") (pintype "bidirectional"))
    )
    (net (code "38") (name "CH3_PF+") (class "Default")
      (node (ref "P-CH3+4") (pin "16") (pinfunction "1_16") (pintype "passive"))
      (node (ref "SSR_3EF") (pin "6") (pinfunction "O2_6") (pintype "bidirectional"))
    )
    (net (code "39") (name "CH3_PG+") (class "Default")
      (node (ref "P-CH3+4") (pin "15") (pinfunction "1_15") (pintype "passive"))
      (node (ref "SSR_3GH") (pin "8") (pinfunction "O2_8") (pintype "bidirectional"))
    )
    (net (code "40") (name "CH3_PH+") (class "Default")
      (node (ref "P-CH3+4") (pin "14") (pinfunction "1_14") (pintype "passive"))
      (node (ref "SSR_3GH") (pin "6") (pinfunction "O2_6") (pintype "bidirectional"))
    )
    (net (code "41") (name "CH3_PJ+") (class "Default")
      (node (ref "P-CH3+4") (pin "13") (pinfunction "1_13") (pintype "passive"))
      (node (ref "SSR_3J/4A") (pin "8") (pinfunction "O2_8") (pintype "bidirectional"))
    )
    (net (code "42") (name "CH4_I+") (class "Default")
      (node (ref "AUDIO_IN") (pin "7") (pinfunction "7_7") (pintype "passive"))
      (node (ref "DRV4") (pin "17") (pinfunction "IN+_17") (pintype "bidirectional"))
    )
    (net (code "43") (name "CH4_I-") (class "Default")
      (node (ref "AUDIO_IN") (pin "20") (pinfunction "20_20") (pintype "passive"))
      (node (ref "DRV4") (pin "16") (pinfunction "IN-_16") (pintype "bidirectional"))
    )
    (net (code "44") (name "CH4_O+") (class "Default")
      (node (ref "DRV4") (pin "13") (pinfunction "OUT+_13") (pintype "bidirectional"))
      (node (ref "SSR_3J/4A") (pin "5") (pinfunction "O1_5") (pintype "bidirectional"))
      (node (ref "SSR_4BC") (pin "5") (pinfunction "O1_5") (pintype "bidirectional"))
      (node (ref "SSR_4BC") (pin "7") (pinfunction "O1_7") (pintype "bidirectional"))
      (node (ref "SSR_4DE") (pin "5") (pinfunction "O1_5") (pintype "bidirectional"))
      (node (ref "SSR_4DE") (pin "7") (pinfunction "O1_7") (pintype "bidirectional"))
      (node (ref "SSR_4FG") (pin "5") (pinfunction "O1_5") (pintype "bidirectional"))
      (node (ref "SSR_4FG") (pin "7") (pinfunction "O1_7") (pintype "bidirectional"))
      (node (ref "SSR_4HJ") (pin "5") (pinfunction "O1_5") (pintype "bidirectional"))
      (node (ref "SSR_4HJ") (pin "7") (pinfunction "O1_7") (pintype "bidirectional"))
    )
    (net (code "45") (name "CH4_O-") (class "Default")
      (node (ref "DRV4") (pin "14") (pinfunction "OUT-_14") (pintype "bidirectional"))
      (node (ref "P-CH3+4") (pin "1") (pinfunction "1_1") (pintype "passive"))
      (node (ref "P-CH3+4") (pin "7") (pinfunction "1_7") (pintype "passive"))
    )
    (net (code "46") (name "CH4_PA+") (class "Default")
      (node (ref "P-CH3+4") (pin "11") (pinfunction "1_11") (pintype "passive"))
      (node (ref "SSR_3J/4A") (pin "6") (pinfunction "O2_6") (pintype "bidirectional"))
    )
    (net (code "47") (name "CH4_PB+") (class "Default")
      (node (ref "P-CH3+4") (pin "10") (pinfunction "1_10") (pintype "passive"))
      (node (ref "SSR_4BC") (pin "8") (pinfunction "O2_8") (pintype "bidirectional"))
    )
    (net (code "48") (name "CH4_PC+") (class "Default")
      (node (ref "P-CH3+4") (pin "9") (pinfunction "1_9") (pintype "passive"))
      (node (ref "SSR_4BC") (pin "6") (pinfunction "O2_6") (pintype "bidirectional"))
    )
    (net (code "49") (name "CH4_PD+") (class "Default")
      (node (ref "P-CH3+4") (pin "8") (pinfunction "1_8") (pintype "passive"))
      (node (ref "SSR_4DE") (pin "8") (pinfunction "O2_8") (pintype "bidirectional"))
    )
    (net (code "50") (name "CH4_PE+") (class "Default")
      (node (ref "P-CH3+4") (pin "6") (pinfunction "1_6") (pintype "passive"))
      (node (ref "SSR_4DE") (pin "6") (pinfunction "O2_6") (pintype "bidirectional"))
    )
    (net (code "51") (name "CH4_PF+") (class "Default")
      (node (ref "P-CH3+4") (pin "5") (pinfunction "1_5") (pintype "passive"))
      (node (ref "SSR_4FG") (pin "8") (pinfunction "O2_8") (pintype "bidirectional"))
    )
    (net (code "52") (name "CH4_PG+") (class "Default")
      (node (ref "P-CH3+4") (pin "4") (pinfunction "1_4") (pintype "passive"))
      (node (ref "SSR_4FG") (pin "6") (pinfunction "O2_6") (pintype "bidirectional"))
    )
    (net (code "53") (name "CH4_PH+") (class "Default")
      (node (ref "P-CH3+4") (pin "3") (pinfunction "1_3") (pintype "passive"))
      (node (ref "SSR_4HJ") (pin "8") (pinfunction "O2_8") (pintype "bidirectional"))
    )
    (net (code "54") (name "CH4_PJ+") (class "Default")
      (node (ref "P-CH3+4") (pin "2") (pinfunction "1_2") (pintype "passive"))
      (node (ref "SSR_4HJ") (pin "6") (pinfunction "O2_6") (pintype "bidirectional"))
    )
    (net (code "55") (name "CH5_I+") (class "Default")
      (node (ref "AUDIO_IN") (pin "18") (pinfunction "18_18") (pintype "passive"))
      (node (ref "DRV5") (pin "17") (pinfunction "IN+_17") (pintype "bidirectional"))
    )
    (net (code "56") (name "CH5_I-") (class "Default")
      (node (ref "AUDIO_IN") (pin "6") (pinfunction "6_6") (pintype "passive"))
      (node (ref "DRV5") (pin "16") (pinfunction "IN-_16") (pintype "bidirectional"))
    )
    (net (code "57") (name "CH5_O+") (class "Default")
      (node (ref "DRV5") (pin "13") (pinfunction "OUT+_13") (pintype "bidirectional"))
      (node (ref "SSR_5AB") (pin "5") (pinfunction "O1_5") (pintype "bidirectional"))
      (node (ref "SSR_5AB") (pin "7") (pinfunction "O1_7") (pintype "bidirectional"))
      (node (ref "SSR_5CD") (pin "5") (pinfunction "O1_5") (pintype "bidirectional"))
      (node (ref "SSR_5CD") (pin "7") (pinfunction "O1_7") (pintype "bidirectional"))
      (node (ref "SSR_5EF") (pin "5") (pinfunction "O1_5") (pintype "bidirectional"))
      (node (ref "SSR_5EF") (pin "7") (pinfunction "O1_7") (pintype "bidirectional"))
      (node (ref "SSR_5GH") (pin "5") (pinfunction "O1_5") (pintype "bidirectional"))
      (node (ref "SSR_5GH") (pin "7") (pinfunction "O1_7") (pintype "bidirectional"))
      (node (ref "SSR_5J/6A") (pin "7") (pinfunction "O1_7") (pintype "bidirectional"))
    )
    (net (code "58") (name "CH5_O-") (class "Default")
      (node (ref "DRV5") (pin "14") (pinfunction "OUT-_14") (pintype "bidirectional"))
      (node (ref "P-CH5+6") (pin "12") (pinfunction "1_12") (pintype "passive"))
      (node (ref "P-CH5+6") (pin "18") (pinfunction "1_18") (pintype "passive"))
    )
    (net (code "59") (name "CH5_PA+") (class "Default")
      (node (ref "P-CH5+6") (pin "22") (pinfunction "1_22") (pintype "passive"))
      (node (ref "SSR_5AB") (pin "8") (pinfunction "O2_8") (pintype "bidirectional"))
    )
    (net (code "60") (name "CH5_PB+") (class "Default")
      (node (ref "P-CH5+6") (pin "21") (pinfunction "1_21") (pintype "passive"))
      (node (ref "SSR_5AB") (pin "6") (pinfunction "O2_6") (pintype "bidirectional"))
    )
    (net (code "61") (name "CH5_PC+") (class "Default")
      (node (ref "P-CH5+6") (pin "20") (pinfunction "1_20") (pintype "passive"))
      (node (ref "SSR_5CD") (pin "8") (pinfunction "O2_8") (pintype "bidirectional"))
    )
    (net (code "62") (name "CH5_PD+") (class "Default")
      (node (ref "P-CH5+6") (pin "19") (pinfunction "1_19") (pintype "passive"))
      (node (ref "SSR_5CD") (pin "6") (pinfunction "O2_6") (pintype "bidirectional"))
    )
    (net (code "63") (name "CH5_PE+") (class "Default")
      (node (ref "P-CH5+6") (pin "17") (pinfunction "1_17") (pintype "passive"))
      (node (ref "SSR_5EF") (pin "8") (pinfunction "O2_8") (pintype "bidirectional"))
    )
    (net (code "64") (name "CH5_PF+") (class "Default")
      (node (ref "P-CH5+6") (pin "16") (pinfunction "1_16") (pintype "passive"))
      (node (ref "SSR_5EF") (pin "6") (pinfunction "O2_6") (pintype "bidirectional"))
    )
    (net (code "65") (name "CH5_PG+") (class "Default")
      (node (ref "P-CH5+6") (pin "15") (pinfunction "1_15") (pintype "passive"))
      (node (ref "SSR_5GH") (pin "8") (pinfunction "O2_8") (pintype "bidirectional"))
    )
    (net (code "66") (name "CH5_PH+") (class "Default")
      (node (ref "P-CH5+6") (pin "14") (pinfunction "1_14") (pintype "passive"))
      (node (ref "SSR_5GH") (pin "6") (pinfunction "O2_6") (pintype "bidirectional"))
    )
    (net (code "67") (name "CH5_PJ+") (class "Default")
      (node (ref "P-CH5+6") (pin "13") (pinfunction "1_13") (pintype "passive"))
      (node (ref "SSR_5J/6A") (pin "8") (pinfunction "O2_8") (pintype "bidirectional"))
    )
    (net (code "68") (name "CH6_I+") (class "Default")
      (node (ref "AUDIO_IN") (pin "4") (pinfunction "4_4") (pintype "passive"))
      (node (ref "DRV6") (pin "17") (pinfunction "IN+_17") (pintype "bidirectional"))
    )
    (net (code "69") (name "CH6_I-") (class "Default")
      (node (ref "AUDIO_IN") (pin "17") (pinfunction "17_17") (pintype "passive"))
      (node (ref "DRV6") (pin "16") (pinfunction "IN-_16") (pintype "bidirectional"))
    )
    (net (code "70") (name "CH6_O+") (class "Default")
      (node (ref "DRV6") (pin "13") (pinfunction "OUT+_13") (pintype "bidirectional"))
      (node (ref "SSR_5J/6A") (pin "5") (pinfunction "O1_5") (pintype "bidirectional"))
      (node (ref "SSR_6BC") (pin "5") (pinfunction "O1_5") (pintype "bidirectional"))
      (node (ref "SSR_6BC") (pin "7") (pinfunction "O1_7") (pintype "bidirectional"))
      (node (ref "SSR_6DE") (pin "5") (pinfunction "O1_5") (pintype "bidirectional"))
      (node (ref "SSR_6DE") (pin "7") (pinfunction "O1_7") (pintype "bidirectional"))
      (node (ref "SSR_6FG") (pin "5") (pinfunction "O1_5") (pintype "bidirectional"))
      (node (ref "SSR_6FG") (pin "7") (pinfunction "O1_7") (pintype "bidirectional"))
      (node (ref "SSR_6HJ") (pin "5") (pinfunction "O1_5") (pintype "bidirectional"))
      (node (ref "SSR_6HJ") (pin "7") (pinfunction "O1_7") (pintype "bidirectional"))
    )
    (net (code "71") (name "CH6_O-") (class "Default")
      (node (ref "DRV6") (pin "14") (pinfunction "OUT-_14") (pintype "bidirectional"))
      (node (ref "P-CH5+6") (pin "1") (pinfunction "1_1") (pintype "passive"))
      (node (ref "P-CH5+6") (pin "7") (pinfunction "1_7") (pintype "passive"))
    )
    (net (code "72") (name "CH6_PA+") (class "Default")
      (node (ref "P-CH5+6") (pin "11") (pinfunction "1_11") (pintype "passive"))
      (node (ref "SSR_5J/6A") (pin "6") (pinfunction "O2_6") (pintype "bidirectional"))
    )
    (net (code "73") (name "CH6_PB+") (class "Default")
      (node (ref "P-CH5+6") (pin "10") (pinfunction "1_10") (pintype "passive"))
      (node (ref "SSR_6BC") (pin "8") (pinfunction "O2_8") (pintype "bidirectional"))
    )
    (net (code "74") (name "CH6_PC+") (class "Default")
      (node (ref "P-CH5+6") (pin "9") (pinfunction "1_9") (pintype "passive"))
      (node (ref "SSR_6BC") (pin "6") (pinfunction "O2_6") (pintype "bidirectional"))
    )
    (net (code "75") (name "CH6_PD+") (class "Default")
      (node (ref "P-CH5+6") (pin "8") (pinfunction "1_8") (pintype "passive"))
      (node (ref "SSR_6DE") (pin "8") (pinfunction "O2_8") (pintype "bidirectional"))
    )
    (net (code "76") (name "CH6_PE+") (class "Default")
      (node (ref "P-CH5+6") (pin "6") (pinfunction "1_6") (pintype "passive"))
      (node (ref "SSR_6DE") (pin "6") (pinfunction "O2_6") (pintype "bidirectional"))
    )
    (net (code "77") (name "CH6_PF+") (class "Default")
      (node (ref "P-CH5+6") (pin "5") (pinfunction "1_5") (pintype "passive"))
      (node (ref "SSR_6FG") (pin "8") (pinfunction "O2_8") (pintype "bidirectional"))
    )
    (net (code "78") (name "CH6_PG+") (class "Default")
      (node (ref "P-CH5+6") (pin "4") (pinfunction "1_4") (pintype "passive"))
      (node (ref "SSR_6FG") (pin "6") (pinfunction "O2_6") (pintype "bidirectional"))
    )
    (net (code "79") (name "CH6_PH+") (class "Default")
      (node (ref "P-CH5+6") (pin "3") (pinfunction "1_3") (pintype "passive"))
      (node (ref "SSR_6HJ") (pin "8") (pinfunction "O2_8") (pintype "bidirectional"))
    )
    (net (code "80") (name "CH6_PJ+") (class "Default")
      (node (ref "P-CH5+6") (pin "2") (pinfunction "1_2") (pintype "passive"))
      (node (ref "SSR_6HJ") (pin "6") (pinfunction "O2_6") (pintype "bidirectional"))
    )
    (net (code "81") (name "CH7_I+") (class "Default")
      (node (ref "AUDIO_IN") (pin "15") (pinfunction "15_15") (pintype "passive"))
      (node (ref "DRV7") (pin "17") (pinfunction "IN+_17") (pintype "bidirectional"))
    )
    (net (code "82") (name "CH7_I-") (class "Default")
      (node (ref "AUDIO_IN") (pin "3") (pinfunction "3_3") (pintype "passive"))
      (node (ref "DRV7") (pin "16") (pinfunction "IN-_16") (pintype "bidirectional"))
    )
    (net (code "83") (name "CH7_O+") (class "Default")
      (node (ref "DRV7") (pin "13") (pinfunction "OUT+_13") (pintype "bidirectional"))
      (node (ref "SSR_7AB") (pin "5") (pinfunction "O1_5") (pintype "bidirectional"))
      (node (ref "SSR_7AB") (pin "7") (pinfunction "O1_7") (pintype "bidirectional"))
      (node (ref "SSR_7CD") (pin "5") (pinfunction "O1_5") (pintype "bidirectional"))
      (node (ref "SSR_7CD") (pin "7") (pinfunction "O1_7") (pintype "bidirectional"))
      (node (ref "SSR_7EF") (pin "5") (pinfunction "O1_5") (pintype "bidirectional"))
      (node (ref "SSR_7EF") (pin "7") (pinfunction "O1_7") (pintype "bidirectional"))
      (node (ref "SSR_7GH") (pin "5") (pinfunction "O1_5") (pintype "bidirectional"))
      (node (ref "SSR_7GH") (pin "7") (pinfunction "O1_7") (pintype "bidirectional"))
      (node (ref "SSR_7J/8A") (pin "7") (pinfunction "O1_7") (pintype "bidirectional"))
    )
    (net (code "84") (name "CH7_O-") (class "Default")
      (node (ref "DRV7") (pin "14") (pinfunction "OUT-_14") (pintype "bidirectional"))
      (node (ref "P-CH7+8") (pin "12") (pinfunction "1_12") (pintype "passive"))
      (node (ref "P-CH7+8") (pin "18") (pinfunction "1_18") (pintype "passive"))
    )
    (net (code "85") (name "CH7_PA+") (class "Default")
      (node (ref "P-CH7+8") (pin "22") (pinfunction "1_22") (pintype "passive"))
      (node (ref "SSR_7AB") (pin "8") (pinfunction "O2_8") (pintype "bidirectional"))
    )
    (net (code "86") (name "CH7_PB+") (class "Default")
      (node (ref "P-CH7+8") (pin "21") (pinfunction "1_21") (pintype "passive"))
      (node (ref "SSR_7AB") (pin "6") (pinfunction "O2_6") (pintype "bidirectional"))
    )
    (net (code "87") (name "CH7_PC+") (class "Default")
      (node (ref "P-CH7+8") (pin "20") (pinfunction "1_20") (pintype "passive"))
      (node (ref "SSR_7CD") (pin "8") (pinfunction "O2_8") (pintype "bidirectional"))
    )
    (net (code "88") (name "CH7_PD+") (class "Default")
      (node (ref "P-CH7+8") (pin "19") (pinfunction "1_19") (pintype "passive"))
      (node (ref "SSR_7CD") (pin "6") (pinfunction "O2_6") (pintype "bidirectional"))
    )
    (net (code "89") (name "CH7_PE+") (class "Default")
      (node (ref "P-CH7+8") (pin "17") (pinfunction "1_17") (pintype "passive"))
      (node (ref "SSR_7EF") (pin "8") (pinfunction "O2_8") (pintype "bidirectional"))
    )
    (net (code "90") (name "CH7_PF+") (class "Default")
      (node (ref "P-CH7+8") (pin "16") (pinfunction "1_16") (pintype "passive"))
      (node (ref "SSR_7EF") (pin "6") (pinfunction "O2_6") (pintype "bidirectional"))
    )
    (net (code "91") (name "CH7_PG+") (class "Default")
      (node (ref "P-CH7+8") (pin "15") (pinfunction "1_15") (pintype "passive"))
      (node (ref "SSR_7GH") (pin "8") (pinfunction "O2_8") (pintype "bidirectional"))
    )
    (net (code "92") (name "CH7_PH+") (class "Default")
      (node (ref "P-CH7+8") (pin "14") (pinfunction "1_14") (pintype "passive"))
      (node (ref "SSR_7GH") (pin "6") (pinfunction "O2_6") (pintype "bidirectional"))
    )
    (net (code "93") (name "CH7_PJ+") (class "Default")
      (node (ref "P-CH7+8") (pin "13") (pinfunction "1_13") (pintype "passive"))
      (node (ref "SSR_7J/8A") (pin "8") (pinfunction "O2_8") (pintype "bidirectional"))
    )
    (net (code "94") (name "CH8_I+") (class "Default")
      (node (ref "AUDIO_IN") (pin "1") (pinfunction "1_1") (pintype "passive"))
      (node (ref "DRV8") (pin "17") (pinfunction "IN+_17") (pintype "bidirectional"))
    )
    (net (code "95") (name "CH8_I-") (class "Default")
      (node (ref "AUDIO_IN") (pin "14") (pinfunction "14_14") (pintype "passive"))
      (node (ref "DRV8") (pin "16") (pinfunction "IN-_16") (pintype "bidirectional"))
    )
    (net (code "96") (name "CH8_O+") (class "Default")
      (node (ref "DRV8") (pin "13") (pinfunction "OUT+_13") (pintype "bidirectional"))
      (node (ref "SSR_7J/8A") (pin "5") (pinfunction "O1_5") (pintype "bidirectional"))
      (node (ref "SSR_8BC") (pin "5") (pinfunction "O1_5") (pintype "bidirectional"))
      (node (ref "SSR_8BC") (pin "7") (pinfunction "O1_7") (pintype "bidirectional"))
      (node (ref "SSR_8DE") (pin "5") (pinfunction "O1_5") (pintype "bidirectional"))
      (node (ref "SSR_8DE") (pin "7") (pinfunction "O1_7") (pintype "bidirectional"))
      (node (ref "SSR_8FG") (pin "5") (pinfunction "O1_5") (pintype "bidirectional"))
      (node (ref "SSR_8FG") (pin "7") (pinfunction "O1_7") (pintype "bidirectional"))
      (node (ref "SSR_8HJ") (pin "5") (pinfunction "O1_5") (pintype "bidirectional"))
      (node (ref "SSR_8HJ") (pin "7") (pinfunction "O1_7") (pintype "bidirectional"))
    )
    (net (code "97") (name "CH8_O-") (class "Default")
      (node (ref "DRV8") (pin "14") (pinfunction "OUT-_14") (pintype "bidirectional"))
      (node (ref "P-CH7+8") (pin "1") (pinfunction "1_1") (pintype "passive"))
      (node (ref "P-CH7+8") (pin "7") (pinfunction "1_7") (pintype "passive"))
    )
    (net (code "98") (name "CH8_PA+") (class "Default")
      (node (ref "P-CH7+8") (pin "11") (pinfunction "1_11") (pintype "passive"))
      (node (ref "SSR_7J/8A") (pin "6") (pinfunction "O2_6") (pintype "bidirectional"))
    )
    (net (code "99") (name "CH8_PB+") (class "Default")
      (node (ref "P-CH7+8") (pin "10") (pinfunction "1_10") (pintype "passive"))
      (node (ref "SSR_8BC") (pin "8") (pinfunction "O2_8") (pintype "bidirectional"))
    )
    (net (code "100") (name "CH8_PC+") (class "Default")
      (node (ref "P-CH7+8") (pin "9") (pinfunction "1_9") (pintype "passive"))
      (node (ref "SSR_8BC") (pin "6") (pinfunction "O2_6") (pintype "bidirectional"))
    )
    (net (code "101") (name "CH8_PD+") (class "Default")
      (node (ref "P-CH7+8") (pin "8") (pinfunction "1_8") (pintype "passive"))
      (node (ref "SSR_8DE") (pin "8") (pinfunction "O2_8") (pintype "bidirectional"))
    )
    (net (code "102") (name "CH8_PE+") (class "Default")
      (node (ref "P-CH7+8") (pin "6") (pinfunction "1_6") (pintype "passive"))
      (node (ref "SSR_8DE") (pin "6") (pinfunction "O2_6") (pintype "bidirectional"))
    )
    (net (code "103") (name "CH8_PF+") (class "Default")
      (node (ref "P-CH7+8") (pin "5") (pinfunction "1_5") (pintype "passive"))
      (node (ref "SSR_8FG") (pin "8") (pinfunction "O2_8") (pintype "bidirectional"))
    )
    (net (code "104") (name "CH8_PG+") (class "Default")
      (node (ref "P-CH7+8") (pin "4") (pinfunction "1_4") (pintype "passive"))
      (node (ref "SSR_8FG") (pin "6") (pinfunction "O2_6") (pintype "bidirectional"))
    )
    (net (code "105") (name "CH8_PH+") (class "Default")
      (node (ref "P-CH7+8") (pin "3") (pinfunction "1_3") (pintype "passive"))
      (node (ref "SSR_8HJ") (pin "8") (pinfunction "O2_8") (pintype "bidirectional"))
    )
    (net (code "106") (name "CH8_PJ+") (class "Default")
      (node (ref "P-CH7+8") (pin "2") (pinfunction "1_2") (pintype "passive"))
      (node (ref "SSR_8HJ") (pin "6") (pinfunction "O2_6") (pintype "bidirectional"))
    )
    (net (code "107") (name "GND") (class "Default")
      (node (ref "AUDIO_IN") (pin "11") (pinfunction "11_11") (pintype "passive"))
      (node (ref "AUDIO_IN") (pin "16") (pinfunction "16_16") (pintype "passive"))
      (node (ref "AUDIO_IN") (pin "19") (pinfunction "19_19") (pintype "passive"))
      (node (ref "AUDIO_IN") (pin "2") (pinfunction "2_2") (pintype "passive"))
      (node (ref "AUDIO_IN") (pin "22") (pinfunction "22_22") (pintype "passive"))
      (node (ref "AUDIO_IN") (pin "25") (pinfunction "25_25") (pintype "passive"))
      (node (ref "AUDIO_IN") (pin "5") (pinfunction "5_5") (pintype "passive"))
      (node (ref "AUDIO_IN") (pin "8") (pinfunction "8_8") (pintype "passive"))
      (node (ref "GND_LIFT") (pin "1") (pinfunction "T1A_1") (pintype "bidirectional"))
      (node (ref "GND_LIFT") (pin "6") (pinfunction "T2A_6") (pintype "bidirectional"))
    )
    (net (code "108") (name "LED1") (class "Default")
      (node (ref "ARDUINO_D") (pin "10") (pinfunction "10_10") (pintype "passive"))
      (node (ref "RLED1") (pin "1") (pinfunction "1_1") (pintype "passive"))
    )
    (net (code "109") (name "LED2") (class "Default")
      (node (ref "ARDUINO_D") (pin "8") (pinfunction "8_8") (pintype "passive"))
      (node (ref "RLED2") (pin "1") (pinfunction "1_1") (pintype "passive"))
    )
    (net (code "110") (name "LED3") (class "Default")
      (node (ref "ARDUINO_D") (pin "7") (pinfunction "7_7") (pintype "passive"))
      (node (ref "RLED3") (pin "1") (pinfunction "1_1") (pintype "passive"))
    )
    (net (code "111") (name "Net-(DRV1-FB)") (class "Default")
      (node (ref "DRV1") (pin "3") (pinfunction "FB_3") (pintype "bidirectional"))
      (node (ref "RVBST1-1") (pin "1") (pinfunction "1_1") (pintype "passive"))
      (node (ref "RVBST1-2") (pin "2") (pinfunction "2_2") (pintype "passive"))
    )
    (net (code "112") (name "Net-(DRV1-PVDD)") (class "Default")
      (node (ref "CVBST1") (pin "1") (pinfunction "1_1") (pintype "passive"))
      (node (ref "DRV1") (pin "10") (pinfunction "VBST_10") (pintype "bidirectional"))
      (node (ref "DRV1") (pin "11") (pinfunction "VBST_11") (pintype "bidirectional"))
      (node (ref "DRV1") (pin "12") (pinfunction "PVDD_12") (pintype "bidirectional"))
      (node (ref "RVBST1-1") (pin "2") (pinfunction "2_2") (pintype "passive"))
    )
    (net (code "113") (name "Net-(DRV1-REXT)") (class "Default")
      (node (ref "DRV1") (pin "15") (pinfunction "REXT_15") (pintype "bidirectional"))
      (node (ref "REXT1") (pin "2") (pinfunction "2_2") (pintype "passive"))
    )
    (net (code "114") (name "Net-(DRV1-SW-Pad7)") (class "Default")
      (node (ref "DRV1") (pin "7") (pinfunction "SW_7") (pintype "bidirectional"))
      (node (ref "DRV1") (pin "8") (pinfunction "SW_8") (pintype "bidirectional"))
      (node (ref "L1") (pin "1") (pinfunction "1_1") (pintype "passive"))
    )
    (net (code "115") (name "Net-(DRV1-VPUMP)") (class "Default")
      (node (ref "CPUMP1") (pin "1") (pinfunction "1_1") (pintype "passive"))
      (node (ref "DRV1") (pin "1") (pinfunction "VPUMP_1") (pintype "bidirectional"))
    )
    (net (code "116") (name "Net-(DRV1-VREG)") (class "Default")
      (node (ref "CVREG1") (pin "1") (pinfunction "1_1") (pintype "passive"))
      (node (ref "DRV1") (pin "20") (pinfunction "VREG_20") (pintype "bidirectional"))
    )
    (net (code "117") (name "Net-(DRV2-FB)") (class "Default")
      (node (ref "DRV2") (pin "3") (pinfunction "FB_3") (pintype "bidirectional"))
      (node (ref "RVBST2-1") (pin "1") (pinfunction "1_1") (pintype "passive"))
      (node (ref "RVBST2-2") (pin "2") (pinfunction "2_2") (pintype "passive"))
    )
    (net (code "118") (name "Net-(DRV2-PVDD)") (class "Default")
      (node (ref "CVBST2") (pin "1") (pinfunction "1_1") (pintype "passive"))
      (node (ref "DRV2") (pin "10") (pinfunction "VBST_10") (pintype "bidirectional"))
      (node (ref "DRV2") (pin "11") (pinfunction "VBST_11") (pintype "bidirectional"))
      (node (ref "DRV2") (pin "12") (pinfunction "PVDD_12") (pintype "bidirectional"))
      (node (ref "RVBST2-1") (pin "2") (pinfunction "2_2") (pintype "passive"))
    )
    (net (code "119") (name "Net-(DRV2-REXT)") (class "Default")
      (node (ref "DRV2") (pin "15") (pinfunction "REXT_15") (pintype "bidirectional"))
      (node (ref "REXT2") (pin "2") (pinfunction "2_2") (pintype "passive"))
    )
    (net (code "120") (name "Net-(DRV2-SW-Pad7)") (class "Default")
      (node (ref "DRV2") (pin "7") (pinfunction "SW_7") (pintype "bidirectional"))
      (node (ref "DRV2") (pin "8") (pinfunction "SW_8") (pintype "bidirectional"))
      (node (ref "L2") (pin "1") (pinfunction "1_1") (pintype "passive"))
    )
    (net (code "121") (name "Net-(DRV2-VPUMP)") (class "Default")
      (node (ref "CPUMP2") (pin "1") (pinfunction "1_1") (pintype "passive"))
      (node (ref "DRV2") (pin "1") (pinfunction "VPUMP_1") (pintype "bidirectional"))
    )
    (net (code "122") (name "Net-(DRV2-VREG)") (class "Default")
      (node (ref "CVREG2") (pin "1") (pinfunction "1_1") (pintype "passive"))
      (node (ref "DRV2") (pin "20") (pinfunction "VREG_20") (pintype "bidirectional"))
    )
    (net (code "123") (name "Net-(DRV3-FB)") (class "Default")
      (node (ref "DRV3") (pin "3") (pinfunction "FB_3") (pintype "bidirectional"))
      (node (ref "RVBST3-1") (pin "1") (pinfunction "1_1") (pintype "passive"))
      (node (ref "RVBST3-2") (pin "2") (pinfunction "2_2") (pintype "passive"))
    )
    (net (code "124") (name "Net-(DRV3-PVDD)") (class "Default")
      (node (ref "CVBST3") (pin "1") (pinfunction "1_1") (pintype "passive"))
      (node (ref "DRV3") (pin "10") (pinfunction "VBST_10") (pintype "bidirectional"))
      (node (ref "DRV3") (pin "11") (pinfunction "VBST_11") (pintype "bidirectional"))
      (node (ref "DRV3") (pin "12") (pinfunction "PVDD_12") (pintype "bidirectional"))
      (node (ref "RVBST3-1") (pin "2") (pinfunction "2_2") (pintype "passive"))
    )
    (net (code "125") (name "Net-(DRV3-REXT)") (class "Default")
      (node (ref "DRV3") (pin "15") (pinfunction "REXT_15") (pintype "bidirectional"))
      (node (ref "REXT3") (pin "2") (pinfunction "2_2") (pintype "passive"))
    )
    (net (code "126") (name "Net-(DRV3-SW-Pad7)") (class "Default")
      (node (ref "DRV3") (pin "7") (pinfunction "SW_7") (pintype "bidirectional"))
      (node (ref "DRV3") (pin "8") (pinfunction "SW_8") (pintype "bidirectional"))
      (node (ref "L3") (pin "1") (pinfunction "1_1") (pintype "passive"))
    )
    (net (code "127") (name "Net-(DRV3-VPUMP)") (class "Default")
      (node (ref "CPUMP3") (pin "1") (pinfunction "1_1") (pintype "passive"))
      (node (ref "DRV3") (pin "1") (pinfunction "VPUMP_1") (pintype "bidirectional"))
    )
    (net (code "128") (name "Net-(DRV3-VREG)") (class "Default")
      (node (ref "CVREG3") (pin "1") (pinfunction "1_1") (pintype "passive"))
      (node (ref "DRV3") (pin "20") (pinfunction "VREG_20") (pintype "bidirectional"))
    )
    (net (code "129") (name "Net-(DRV4-FB)") (class "Default")
      (node (ref "DRV4") (pin "3") (pinfunction "FB_3") (pintype "bidirectional"))
      (node (ref "RVBST4-1") (pin "1") (pinfunction "1_1") (pintype "passive"))
      (node (ref "RVBST4-2") (pin "2") (pinfunction "2_2") (pintype "passive"))
    )
    (net (code "130") (name "Net-(DRV4-PVDD)") (class "Default")
      (node (ref "CVBST4") (pin "1") (pinfunction "1_1") (pintype "passive"))
      (node (ref "DRV4") (pin "10") (pinfunction "VBST_10") (pintype "bidirectional"))
      (node (ref "DRV4") (pin "11") (pinfunction "VBST_11") (pintype "bidirectional"))
      (node (ref "DRV4") (pin "12") (pinfunction "PVDD_12") (pintype "bidirectional"))
      (node (ref "RVBST4-1") (pin "2") (pinfunction "2_2") (pintype "passive"))
    )
    (net (code "131") (name "Net-(DRV4-REXT)") (class "Default")
      (node (ref "DRV4") (pin "15") (pinfunction "REXT_15") (pintype "bidirectional"))
      (node (ref "REXT4") (pin "2") (pinfunction "2_2") (pintype "passive"))
    )
    (net (code "132") (name "Net-(DRV4-SW-Pad7)") (class "Default")
      (node (ref "DRV4") (pin "7") (pinfunction "SW_7") (pintype "bidirectional"))
      (node (ref "DRV4") (pin "8") (pinfunction "SW_8") (pintype "bidirectional"))
      (node (ref "L4") (pin "1") (pinfunction "1_1") (pintype "passive"))
    )
    (net (code "133") (name "Net-(DRV4-VPUMP)") (class "Default")
      (node (ref "CPUMP4") (pin "1") (pinfunction "1_1") (pintype "passive"))
      (node (ref "DRV4") (pin "1") (pinfunction "VPUMP_1") (pintype "bidirectional"))
    )
    (net (code "134") (name "Net-(DRV4-VREG)") (class "Default")
      (node (ref "CVREG4") (pin "1") (pinfunction "1_1") (pintype "passive"))
      (node (ref "DRV4") (pin "20") (pinfunction "VREG_20") (pintype "bidirectional"))
    )
    (net (code "135") (name "Net-(DRV5-FB)") (class "Default")
      (node (ref "DRV5") (pin "3") (pinfunction "FB_3") (pintype "bidirectional"))
      (node (ref "RVBST5-1") (pin "1") (pinfunction "1_1") (pintype "passive"))
      (node (ref "RVBST5-2") (pin "2") (pinfunction "2_2") (pintype "passive"))
    )
    (net (code "136") (name "Net-(DRV5-PVDD)") (class "Default")
      (node (ref "CVBST5") (pin "1") (pinfunction "1_1") (pintype "passive"))
      (node (ref "DRV5") (pin "10") (pinfunction "VBST_10") (pintype "bidirectional"))
      (node (ref "DRV5") (pin "11") (pinfunction "VBST_11") (pintype "bidirectional"))
      (node (ref "DRV5") (pin "12") (pinfunction "PVDD_12") (pintype "bidirectional"))
      (node (ref "RVBST5-1") (pin "2") (pinfunction "2_2") (pintype "passive"))
    )
    (net (code "137") (name "Net-(DRV5-REXT)") (class "Default")
      (node (ref "DRV5") (pin "15") (pinfunction "REXT_15") (pintype "bidirectional"))
      (node (ref "REXT5") (pin "2") (pinfunction "2_2") (pintype "passive"))
    )
    (net (code "138") (name "Net-(DRV5-SW-Pad7)") (class "Default")
      (node (ref "DRV5") (pin "7") (pinfunction "SW_7") (pintype "bidirectional"))
      (node (ref "DRV5") (pin "8") (pinfunction "SW_8") (pintype "bidirectional"))
      (node (ref "L5") (pin "1") (pinfunction "1_1") (pintype "passive"))
    )
    (net (code "139") (name "Net-(DRV5-VPUMP)") (class "Default")
      (node (ref "CPUMP5") (pin "1") (pinfunction "1_1") (pintype "passive"))
      (node (ref "DRV5") (pin "1") (pinfunction "VPUMP_1") (pintype "bidirectional"))
    )
    (net (code "140") (name "Net-(DRV5-VREG)") (class "Default")
      (node (ref "CVREG5") (pin "1") (pinfunction "1_1") (pintype "passive"))
      (node (ref "DRV5") (pin "20") (pinfunction "VREG_20") (pintype "bidirectional"))
    )
    (net (code "141") (name "Net-(DRV6-FB)") (class "Default")
      (node (ref "DRV6") (pin "3") (pinfunction "FB_3") (pintype "bidirectional"))
      (node (ref "RVBST6-1") (pin "1") (pinfunction "1_1") (pintype "passive"))
      (node (ref "RVBST6-2") (pin "2") (pinfunction "2_2") (pintype "passive"))
    )
    (net (code "142") (name "Net-(DRV6-PVDD)") (class "Default")
      (node (ref "CVBST6") (pin "1") (pinfunction "1_1") (pintype "passive"))
      (node (ref "DRV6") (pin "10") (pinfunction "VBST_10") (pintype "bidirectional"))
      (node (ref "DRV6") (pin "11") (pinfunction "VBST_11") (pintype "bidirectional"))
      (node (ref "DRV6") (pin "12") (pinfunction "PVDD_12") (pintype "bidirectional"))
      (node (ref "RVBST6-1") (pin "2") (pinfunction "2_2") (pintype "passive"))
    )
    (net (code "143") (name "Net-(DRV6-REXT)") (class "Default")
      (node (ref "DRV6") (pin "15") (pinfunction "REXT_15") (pintype "bidirectional"))
      (node (ref "REXT6") (pin "2") (pinfunction "2_2") (pintype "passive"))
    )
    (net (code "144") (name "Net-(DRV6-SW-Pad7)") (class "Default")
      (node (ref "DRV6") (pin "7") (pinfunction "SW_7") (pintype "bidirectional"))
      (node (ref "DRV6") (pin "8") (pinfunction "SW_8") (pintype "bidirectional"))
      (node (ref "L6") (pin "1") (pinfunction "1_1") (pintype "passive"))
    )
    (net (code "145") (name "Net-(DRV6-VPUMP)") (class "Default")
      (node (ref "CPUMP6") (pin "1") (pinfunction "1_1") (pintype "passive"))
      (node (ref "DRV6") (pin "1") (pinfunction "VPUMP_1") (pintype "bidirectional"))
    )
    (net (code "146") (name "Net-(DRV6-VREG)") (class "Default")
      (node (ref "CVREG6") (pin "1") (pinfunction "1_1") (pintype "passive"))
      (node (ref "DRV6") (pin "20") (pinfunction "VREG_20") (pintype "bidirectional"))
    )
    (net (code "147") (name "Net-(DRV7-FB)") (class "Default")
      (node (ref "DRV7") (pin "3") (pinfunction "FB_3") (pintype "bidirectional"))
      (node (ref "RVBST7-1") (pin "1") (pinfunction "1_1") (pintype "passive"))
      (node (ref "RVBST7-2") (pin "2") (pinfunction "2_2") (pintype "passive"))
    )
    (net (code "148") (name "Net-(DRV7-PVDD)") (class "Default")
      (node (ref "CVBST7") (pin "1") (pinfunction "1_1") (pintype "passive"))
      (node (ref "DRV7") (pin "10") (pinfunction "VBST_10") (pintype "bidirectional"))
      (node (ref "DRV7") (pin "11") (pinfunction "VBST_11") (pintype "bidirectional"))
      (node (ref "DRV7") (pin "12") (pinfunction "PVDD_12") (pintype "bidirectional"))
      (node (ref "RVBST7-1") (pin "2") (pinfunction "2_2") (pintype "passive"))
    )
    (net (code "149") (name "Net-(DRV7-REXT)") (class "Default")
      (node (ref "DRV7") (pin "15") (pinfunction "REXT_15") (pintype "bidirectional"))
      (node (ref "REXT7") (pin "2") (pinfunction "2_2") (pintype "passive"))
    )
    (net (code "150") (name "Net-(DRV7-SW-Pad7)") (class "Default")
      (node (ref "DRV7") (pin "7") (pinfunction "SW_7") (pintype "bidirectional"))
      (node (ref "DRV7") (pin "8") (pinfunction "SW_8") (pintype "bidirectional"))
      (node (ref "L7") (pin "1") (pinfunction "1_1") (pintype "passive"))
    )
    (net (code "151") (name "Net-(DRV7-VPUMP)") (class "Default")
      (node (ref "CPUMP7") (pin "1") (pinfunction "1_1") (pintype "passive"))
      (node (ref "DRV7") (pin "1") (pinfunction "VPUMP_1") (pintype "bidirectional"))
    )
    (net (code "152") (name "Net-(DRV7-VREG)") (class "Default")
      (node (ref "CVREG7") (pin "1") (pinfunction "1_1") (pintype "passive"))
      (node (ref "DRV7") (pin "20") (pinfunction "VREG_20") (pintype "bidirectional"))
    )
    (net (code "153") (name "Net-(DRV8-FB)") (class "Default")
      (node (ref "DRV8") (pin "3") (pinfunction "FB_3") (pintype "bidirectional"))
      (node (ref "RVBST8-1") (pin "1") (pinfunction "1_1") (pintype "passive"))
      (node (ref "RVBST8-2") (pin "2") (pinfunction "2_2") (pintype "passive"))
    )
    (net (code "154") (name "Net-(DRV8-PVDD)") (class "Default")
      (node (ref "CVBST8") (pin "1") (pinfunction "1_1") (pintype "passive"))
      (node (ref "DRV8") (pin "10") (pinfunction "VBST_10") (pintype "bidirectional"))
      (node (ref "DRV8") (pin "11") (pinfunction "VBST_11") (pintype "bidirectional"))
      (node (ref "DRV8") (pin "12") (pinfunction "PVDD_12") (pintype "bidirectional"))
      (node (ref "RVBST8-1") (pin "2") (pinfunction "2_2") (pintype "passive"))
    )
    (net (code "155") (name "Net-(DRV8-REXT)") (class "Default")
      (node (ref "DRV8") (pin "15") (pinfunction "REXT_15") (pintype "bidirectional"))
      (node (ref "REXT8") (pin "2") (pinfunction "2_2") (pintype "passive"))
    )
    (net (code "156") (name "Net-(DRV8-SW-Pad7)") (class "Default")
      (node (ref "DRV8") (pin "7") (pinfunction "SW_7") (pintype "bidirectional"))
      (node (ref "DRV8") (pin "8") (pinfunction "SW_8") (pintype "bidirectional"))
      (node (ref "L8") (pin "1") (pinfunction "1_1") (pintype "passive"))
    )
    (net (code "157") (name "Net-(DRV8-VPUMP)") (class "Default")
      (node (ref "CPUMP8") (pin "1") (pinfunction "1_1") (pintype "passive"))
      (node (ref "DRV8") (pin "1") (pinfunction "VPUMP_1") (pintype "bidirectional"))
    )
    (net (code "158") (name "Net-(DRV8-VREG)") (class "Default")
      (node (ref "CVREG8") (pin "1") (pinfunction "1_1") (pintype "passive"))
      (node (ref "DRV8") (pin "20") (pinfunction "VREG_20") (pintype "bidirectional"))
    )
    (net (code "159") (name "Net-(GND_LIFT-P1)") (class "Default")
      (node (ref "GND_LIFT") (pin "2") (pinfunction "P1_2") (pintype "bidirectional"))
      (node (ref "GND_LIFT") (pin "5") (pinfunction "P2_5") (pintype "bidirectional"))
      (node (ref "R_LIFT1") (pin "2") (pinfunction "2_2") (pintype "passive"))
      (node (ref "R_LIFT2") (pin "1") (pinfunction "1_1") (pintype "passive"))
    )
    (net (code "160") (name "Net-(LED1-PadC)") (class "Default")
      (node (ref "LED1") (pin "C") (pinfunction "C_C") (pintype "passive"))
      (node (ref "RLED1") (pin "2") (pinfunction "2_2") (pintype "passive"))
    )
    (net (code "161") (name "Net-(LED2-PadC)") (class "Default")
      (node (ref "LED2") (pin "C") (pinfunction "C_C") (pintype "passive"))
      (node (ref "RLED2") (pin "2") (pinfunction "2_2") (pintype "passive"))
    )
    (net (code "162") (name "Net-(LED3-PadC)") (class "Default")
      (node (ref "LED3") (pin "C") (pinfunction "C_C") (pintype "passive"))
      (node (ref "RLED3") (pin "2") (pinfunction "2_2") (pintype "passive"))
    )
    (net (code "163") (name "Net-(LED_SUP-PadA)") (class "Default")
      (node (ref "LED_SUP") (pin "A") (pinfunction "A_A") (pintype "passive"))
      (node (ref "RLED_SUP") (pin "1") (pinfunction "1_1") (pintype "passive"))
    )
    (net (code "164") (name "Net-(SSR_1ABA-I+)") (class "Default")
      (node (ref "R_1A") (pin "1") (pinfunction "1_1") (pintype "passive"))
      (node (ref "SSR_1AB") (pin "1") (pinfunction "I+_1") (pintype "bidirectional"))
    )
    (net (code "165") (name "Net-(SSR_1ABB-I+)") (class "Default")
      (node (ref "R_1B") (pin "1") (pinfunction "1_1") (pintype "passive"))
      (node (ref "SSR_1AB") (pin "3") (pinfunction "I+_3") (pintype "bidirectional"))
    )
    (net (code "166") (name "Net-(SSR_1CDA-I+)") (class "Default")
      (node (ref "R_1C") (pin "1") (pinfunction "1_1") (pintype "passive"))
      (node (ref "SSR_1CD") (pin "1") (pinfunction "I+_1") (pintype "bidirectional"))
    )
    (net (code "167") (name "Net-(SSR_1CDB-I+)") (class "Default")
      (node (ref "R_1D") (pin "1") (pinfunction "1_1") (pintype "passive"))
      (node (ref "SSR_1CD") (pin "3") (pinfunction "I+_3") (pintype "bidirectional"))
    )
    (net (code "168") (name "Net-(SSR_1EFA-I+)") (class "Default")
      (node (ref "R_1E") (pin "1") (pinfunction "1_1") (pintype "passive"))
      (node (ref "SSR_1EF") (pin "1") (pinfunction "I+_1") (pintype "bidirectional"))
    )
    (net (code "169") (name "Net-(SSR_1EFB-I+)") (class "Default")
      (node (ref "R_1F") (pin "1") (pinfunction "1_1") (pintype "passive"))
      (node (ref "SSR_1EF") (pin "3") (pinfunction "I+_3") (pintype "bidirectional"))
    )
    (net (code "170") (name "Net-(SSR_1GHA-I+)") (class "Default")
      (node (ref "R_1G") (pin "1") (pinfunction "1_1") (pintype "passive"))
      (node (ref "SSR_1GH") (pin "1") (pinfunction "I+_1") (pintype "bidirectional"))
    )
    (net (code "171") (name "Net-(SSR_1GHB-I+)") (class "Default")
      (node (ref "R_1H") (pin "1") (pinfunction "1_1") (pintype "passive"))
      (node (ref "SSR_1GH") (pin "3") (pinfunction "I+_3") (pintype "bidirectional"))
    )
    (net (code "172") (name "Net-(SSR_1J/2AA-I+)") (class "Default")
      (node (ref "R_1J") (pin "1") (pinfunction "1_1") (pintype "passive"))
      (node (ref "SSR_1J/2A") (pin "1") (pinfunction "I+_1") (pintype "bidirectional"))
    )
    (net (code "173") (name "Net-(SSR_1J/2AB-I+)") (class "Default")
      (node (ref "R_2A") (pin "1") (pinfunction "1_1") (pintype "passive"))
      (node (ref "SSR_1J/2A") (pin "3") (pinfunction "I+_3") (pintype "bidirectional"))
    )
    (net (code "174") (name "Net-(SSR_2BCA-I+)") (class "Default")
      (node (ref "R_2B") (pin "1") (pinfunction "1_1") (pintype "passive"))
      (node (ref "SSR_2BC") (pin "1") (pinfunction "I+_1") (pintype "bidirectional"))
    )
    (net (code "175") (name "Net-(SSR_2BCB-I+)") (class "Default")
      (node (ref "R_2C") (pin "1") (pinfunction "1_1") (pintype "passive"))
      (node (ref "SSR_2BC") (pin "3") (pinfunction "I+_3") (pintype "bidirectional"))
    )
    (net (code "176") (name "Net-(SSR_2DEA-I+)") (class "Default")
      (node (ref "R_2D") (pin "1") (pinfunction "1_1") (pintype "passive"))
      (node (ref "SSR_2DE") (pin "1") (pinfunction "I+_1") (pintype "bidirectional"))
    )
    (net (code "177") (name "Net-(SSR_2DEB-I+)") (class "Default")
      (node (ref "R_2E") (pin "1") (pinfunction "1_1") (pintype "passive"))
      (node (ref "SSR_2DE") (pin "3") (pinfunction "I+_3") (pintype "bidirectional"))
    )
    (net (code "178") (name "Net-(SSR_2FGA-I+)") (class "Default")
      (node (ref "R_2F") (pin "1") (pinfunction "1_1") (pintype "passive"))
      (node (ref "SSR_2FG") (pin "1") (pinfunction "I+_1") (pintype "bidirectional"))
    )
    (net (code "179") (name "Net-(SSR_2FGB-I+)") (class "Default")
      (node (ref "R_2G") (pin "1") (pinfunction "1_1") (pintype "passive"))
      (node (ref "SSR_2FG") (pin "3") (pinfunction "I+_3") (pintype "bidirectional"))
    )
    (net (code "180") (name "Net-(SSR_2HJA-I+)") (class "Default")
      (node (ref "R_2H") (pin "1") (pinfunction "1_1") (pintype "passive"))
      (node (ref "SSR_2HJ") (pin "1") (pinfunction "I+_1") (pintype "bidirectional"))
    )
    (net (code "181") (name "Net-(SSR_2HJB-I+)") (class "Default")
      (node (ref "R_2J") (pin "1") (pinfunction "1_1") (pintype "passive"))
      (node (ref "SSR_2HJ") (pin "3") (pinfunction "I+_3") (pintype "bidirectional"))
    )
    (net (code "182") (name "Net-(SSR_3ABA-I+)") (class "Default")
      (node (ref "R_3A") (pin "1") (pinfunction "1_1") (pintype "passive"))
      (node (ref "SSR_3AB") (pin "1") (pinfunction "I+_1") (pintype "bidirectional"))
    )
    (net (code "183") (name "Net-(SSR_3ABB-I+)") (class "Default")
      (node (ref "R_3B") (pin "1") (pinfunction "1_1") (pintype "passive"))
      (node (ref "SSR_3AB") (pin "3") (pinfunction "I+_3") (pintype "bidirectional"))
    )
    (net (code "184") (name "Net-(SSR_3CDA-I+)") (class "Default")
      (node (ref "R_3C") (pin "1") (pinfunction "1_1") (pintype "passive"))
      (node (ref "SSR_3CD") (pin "1") (pinfunction "I+_1") (pintype "bidirectional"))
    )
    (net (code "185") (name "Net-(SSR_3CDB-I+)") (class "Default")
      (node (ref "R_3D") (pin "1") (pinfunction "1_1") (pintype "passive"))
      (node (ref "SSR_3CD") (pin "3") (pinfunction "I+_3") (pintype "bidirectional"))
    )
    (net (code "186") (name "Net-(SSR_3EFA-I+)") (class "Default")
      (node (ref "R_3E") (pin "1") (pinfunction "1_1") (pintype "passive"))
      (node (ref "SSR_3EF") (pin "1") (pinfunction "I+_1") (pintype "bidirectional"))
    )
    (net (code "187") (name "Net-(SSR_3EFB-I+)") (class "Default")
      (node (ref "R_3F") (pin "1") (pinfunction "1_1") (pintype "passive"))
      (node (ref "SSR_3EF") (pin "3") (pinfunction "I+_3") (pintype "bidirectional"))
    )
    (net (code "188") (name "Net-(SSR_3GHA-I+)") (class "Default")
      (node (ref "R_3G") (pin "1") (pinfunction "1_1") (pintype "passive"))
      (node (ref "SSR_3GH") (pin "1") (pinfunction "I+_1") (pintype "bidirectional"))
    )
    (net (code "189") (name "Net-(SSR_3GHB-I+)") (class "Default")
      (node (ref "R_3H") (pin "1") (pinfunction "1_1") (pintype "passive"))
      (node (ref "SSR_3GH") (pin "3") (pinfunction "I+_3") (pintype "bidirectional"))
    )
    (net (code "190") (name "Net-(SSR_3J/4AA-I+)") (class "Default")
      (node (ref "R_3J") (pin "1") (pinfunction "1_1") (pintype "passive"))
      (node (ref "SSR_3J/4A") (pin "1") (pinfunction "I+_1") (pintype "bidirectional"))
    )
    (net (code "191") (name "Net-(SSR_3J/4AB-I+)") (class "Default")
      (node (ref "R_4A") (pin "1") (pinfunction "1_1") (pintype "passive"))
      (node (ref "SSR_3J/4A") (pin "3") (pinfunction "I+_3") (pintype "bidirectional"))
    )
    (net (code "192") (name "Net-(SSR_4BCA-I+)") (class "Default")
      (node (ref "R_4B") (pin "1") (pinfunction "1_1") (pintype "passive"))
      (node (ref "SSR_4BC") (pin "1") (pinfunction "I+_1") (pintype "bidirectional"))
    )
    (net (code "193") (name "Net-(SSR_4BCB-I+)") (class "Default")
      (node (ref "R_4C") (pin "1") (pinfunction "1_1") (pintype "passive"))
      (node (ref "SSR_4BC") (pin "3") (pinfunction "I+_3") (pintype "bidirectional"))
    )
    (net (code "194") (name "Net-(SSR_4DEA-I+)") (class "Default")
      (node (ref "R_4D") (pin "1") (pinfunction "1_1") (pintype "passive"))
      (node (ref "SSR_4DE") (pin "1") (pinfunction "I+_1") (pintype "bidirectional"))
    )
    (net (code "195") (name "Net-(SSR_4DEB-I+)") (class "Default")
      (node (ref "R_4E") (pin "1") (pinfunction "1_1") (pintype "passive"))
      (node (ref "SSR_4DE") (pin "3") (pinfunction "I+_3") (pintype "bidirectional"))
    )
    (net (code "196") (name "Net-(SSR_4FGA-I+)") (class "Default")
      (node (ref "R_4F") (pin "1") (pinfunction "1_1") (pintype "passive"))
      (node (ref "SSR_4FG") (pin "1") (pinfunction "I+_1") (pintype "bidirectional"))
    )
    (net (code "197") (name "Net-(SSR_4FGB-I+)") (class "Default")
      (node (ref "R_4G") (pin "1") (pinfunction "1_1") (pintype "passive"))
      (node (ref "SSR_4FG") (pin "3") (pinfunction "I+_3") (pintype "bidirectional"))
    )
    (net (code "198") (name "Net-(SSR_4HJA-I+)") (class "Default")
      (node (ref "R_4H") (pin "1") (pinfunction "1_1") (pintype "passive"))
      (node (ref "SSR_4HJ") (pin "1") (pinfunction "I+_1") (pintype "bidirectional"))
    )
    (net (code "199") (name "Net-(SSR_4HJB-I+)") (class "Default")
      (node (ref "R_4J") (pin "1") (pinfunction "1_1") (pintype "passive"))
      (node (ref "SSR_4HJ") (pin "3") (pinfunction "I+_3") (pintype "bidirectional"))
    )
    (net (code "200") (name "Net-(SSR_5ABA-I+)") (class "Default")
      (node (ref "R_5A") (pin "1") (pinfunction "1_1") (pintype "passive"))
      (node (ref "SSR_5AB") (pin "1") (pinfunction "I+_1") (pintype "bidirectional"))
    )
    (net (code "201") (name "Net-(SSR_5ABB-I+)") (class "Default")
      (node (ref "R_5B") (pin "1") (pinfunction "1_1") (pintype "passive"))
      (node (ref "SSR_5AB") (pin "3") (pinfunction "I+_3") (pintype "bidirectional"))
    )
    (net (code "202") (name "Net-(SSR_5CDA-I+)") (class "Default")
      (node (ref "R_5C") (pin "1") (pinfunction "1_1") (pintype "passive"))
      (node (ref "SSR_5CD") (pin "1") (pinfunction "I+_1") (pintype "bidirectional"))
    )
    (net (code "203") (name "Net-(SSR_5CDB-I+)") (class "Default")
      (node (ref "R_5D") (pin "1") (pinfunction "1_1") (pintype "passive"))
      (node (ref "SSR_5CD") (pin "3") (pinfunction "I+_3") (pintype "bidirectional"))
    )
    (net (code "204") (name "Net-(SSR_5EFA-I+)") (class "Default")
      (node (ref "R_5E") (pin "1") (pinfunction "1_1") (pintype "passive"))
      (node (ref "SSR_5EF") (pin "1") (pinfunction "I+_1") (pintype "bidirectional"))
    )
    (net (code "205") (name "Net-(SSR_5EFB-I+)") (class "Default")
      (node (ref "R_5F") (pin "1") (pinfunction "1_1") (pintype "passive"))
      (node (ref "SSR_5EF") (pin "3") (pinfunction "I+_3") (pintype "bidirectional"))
    )
    (net (code "206") (name "Net-(SSR_5GHA-I+)") (class "Default")
      (node (ref "R_5G") (pin "1") (pinfunction "1_1") (pintype "passive"))
      (node (ref "SSR_5GH") (pin "1") (pinfunction "I+_1") (pintype "bidirectional"))
    )
    (net (code "207") (name "Net-(SSR_5GHB-I+)") (class "Default")
      (node (ref "R_5H") (pin "1") (pinfunction "1_1") (pintype "passive"))
      (node (ref "SSR_5GH") (pin "3") (pinfunction "I+_3") (pintype "bidirectional"))
    )
    (net (code "208") (name "Net-(SSR_5J/6AA-I+)") (class "Default")
      (node (ref "R_5J") (pin "1") (pinfunction "1_1") (pintype "passive"))
      (node (ref "SSR_5J/6A") (pin "1") (pinfunction "I+_1") (pintype "bidirectional"))
    )
    (net (code "209") (name "Net-(SSR_5J/6AB-I+)") (class "Default")
      (node (ref "R_6A") (pin "1") (pinfunction "1_1") (pintype "passive"))
      (node (ref "SSR_5J/6A") (pin "3") (pinfunction "I+_3") (pintype "bidirectional"))
    )
    (net (code "210") (name "Net-(SSR_6BCA-I+)") (class "Default")
      (node (ref "R_6B") (pin "1") (pinfunction "1_1") (pintype "passive"))
      (node (ref "SSR_6BC") (pin "1") (pinfunction "I+_1") (pintype "bidirectional"))
    )
    (net (code "211") (name "Net-(SSR_6BCB-I+)") (class "Default")
      (node (ref "R_6C") (pin "1") (pinfunction "1_1") (pintype "passive"))
      (node (ref "SSR_6BC") (pin "3") (pinfunction "I+_3") (pintype "bidirectional"))
    )
    (net (code "212") (name "Net-(SSR_6DEA-I+)") (class "Default")
      (node (ref "R_6D") (pin "1") (pinfunction "1_1") (pintype "passive"))
      (node (ref "SSR_6DE") (pin "1") (pinfunction "I+_1") (pintype "bidirectional"))
    )
    (net (code "213") (name "Net-(SSR_6DEB-I+)") (class "Default")
      (node (ref "R_6E") (pin "1") (pinfunction "1_1") (pintype "passive"))
      (node (ref "SSR_6DE") (pin "3") (pinfunction "I+_3") (pintype "bidirectional"))
    )
    (net (code "214") (name "Net-(SSR_6FGA-I+)") (class "Default")
      (node (ref "R_6F") (pin "1") (pinfunction "1_1") (pintype "passive"))
      (node (ref "SSR_6FG") (pin "1") (pinfunction "I+_1") (pintype "bidirectional"))
    )
    (net (code "215") (name "Net-(SSR_6FGB-I+)") (class "Default")
      (node (ref "R_6G") (pin "1") (pinfunction "1_1") (pintype "passive"))
      (node (ref "SSR_6FG") (pin "3") (pinfunction "I+_3") (pintype "bidirectional"))
    )
    (net (code "216") (name "Net-(SSR_6HJA-I+)") (class "Default")
      (node (ref "R_6H") (pin "1") (pinfunction "1_1") (pintype "passive"))
      (node (ref "SSR_6HJ") (pin "1") (pinfunction "I+_1") (pintype "bidirectional"))
    )
    (net (code "217") (name "Net-(SSR_6HJB-I+)") (class "Default")
      (node (ref "R_6J") (pin "1") (pinfunction "1_1") (pintype "passive"))
      (node (ref "SSR_6HJ") (pin "3") (pinfunction "I+_3") (pintype "bidirectional"))
    )
    (net (code "218") (name "Net-(SSR_7ABA-I+)") (class "Default")
      (node (ref "R_7A") (pin "1") (pinfunction "1_1") (pintype "passive"))
      (node (ref "SSR_7AB") (pin "1") (pinfunction "I+_1") (pintype "bidirectional"))
    )
    (net (code "219") (name "Net-(SSR_7ABB-I+)") (class "Default")
      (node (ref "R_7B") (pin "1") (pinfunction "1_1") (pintype "passive"))
      (node (ref "SSR_7AB") (pin "3") (pinfunction "I+_3") (pintype "bidirectional"))
    )
    (net (code "220") (name "Net-(SSR_7CDA-I+)") (class "Default")
      (node (ref "R_7C") (pin "1") (pinfunction "1_1") (pintype "passive"))
      (node (ref "SSR_7CD") (pin "1") (pinfunction "I+_1") (pintype "bidirectional"))
    )
    (net (code "221") (name "Net-(SSR_7CDB-I+)") (class "Default")
      (node (ref "R_7D") (pin "1") (pinfunction "1_1") (pintype "passive"))
      (node (ref "SSR_7CD") (pin "3") (pinfunction "I+_3") (pintype "bidirectional"))
    )
    (net (code "222") (name "Net-(SSR_7EFA-I+)") (class "Default")
      (node (ref "R_7E") (pin "1") (pinfunction "1_1") (pintype "passive"))
      (node (ref "SSR_7EF") (pin "1") (pinfunction "I+_1") (pintype "bidirectional"))
    )
    (net (code "223") (name "Net-(SSR_7EFB-I+)") (class "Default")
      (node (ref "R_7F") (pin "1") (pinfunction "1_1") (pintype "passive"))
      (node (ref "SSR_7EF") (pin "3") (pinfunction "I+_3") (pintype "bidirectional"))
    )
    (net (code "224") (name "Net-(SSR_7GHA-I+)") (class "Default")
      (node (ref "R_7G") (pin "1") (pinfunction "1_1") (pintype "passive"))
      (node (ref "SSR_7GH") (pin "1") (pinfunction "I+_1") (pintype "bidirectional"))
    )
    (net (code "225") (name "Net-(SSR_7GHB-I+)") (class "Default")
      (node (ref "R_7H") (pin "1") (pinfunction "1_1") (pintype "passive"))
      (node (ref "SSR_7GH") (pin "3") (pinfunction "I+_3") (pintype "bidirectional"))
    )
    (net (code "226") (name "Net-(SSR_7J/8AA-I+)") (class "Default")
      (node (ref "R_7J") (pin "1") (pinfunction "1_1") (pintype "passive"))
      (node (ref "SSR_7J/8A") (pin "1") (pinfunction "I+_1") (pintype "bidirectional"))
    )
    (net (code "227") (name "Net-(SSR_7J/8AB-I+)") (class "Default")
      (node (ref "R_8A") (pin "1") (pinfunction "1_1") (pintype "passive"))
      (node (ref "SSR_7J/8A") (pin "3") (pinfunction "I+_3") (pintype "bidirectional"))
    )
    (net (code "228") (name "Net-(SSR_8BCA-I+)") (class "Default")
      (node (ref "R_8B") (pin "1") (pinfunction "1_1") (pintype "passive"))
      (node (ref "SSR_8BC") (pin "1") (pinfunction "I+_1") (pintype "bidirectional"))
    )
    (net (code "229") (name "Net-(SSR_8BCB-I+)") (class "Default")
      (node (ref "R_8C") (pin "1") (pinfunction "1_1") (pintype "passive"))
      (node (ref "SSR_8BC") (pin "3") (pinfunction "I+_3") (pintype "bidirectional"))
    )
    (net (code "230") (name "Net-(SSR_8DEA-I+)") (class "Default")
      (node (ref "R_8D") (pin "1") (pinfunction "1_1") (pintype "passive"))
      (node (ref "SSR_8DE") (pin "1") (pinfunction "I+_1") (pintype "bidirectional"))
    )
    (net (code "231") (name "Net-(SSR_8DEB-I+)") (class "Default")
      (node (ref "R_8E") (pin "1") (pinfunction "1_1") (pintype "passive"))
      (node (ref "SSR_8DE") (pin "3") (pinfunction "I+_3") (pintype "bidirectional"))
    )
    (net (code "232") (name "Net-(SSR_8FGA-I+)") (class "Default")
      (node (ref "R_8F") (pin "1") (pinfunction "1_1") (pintype "passive"))
      (node (ref "SSR_8FG") (pin "1") (pinfunction "I+_1") (pintype "bidirectional"))
    )
    (net (code "233") (name "Net-(SSR_8FGB-I+)") (class "Default")
      (node (ref "R_8G") (pin "1") (pinfunction "1_1") (pintype "passive"))
      (node (ref "SSR_8FG") (pin "3") (pinfunction "I+_3") (pintype "bidirectional"))
    )
    (net (code "234") (name "Net-(SSR_8HJA-I+)") (class "Default")
      (node (ref "R_8H") (pin "1") (pinfunction "1_1") (pintype "passive"))
      (node (ref "SSR_8HJ") (pin "1") (pinfunction "I+_1") (pintype "bidirectional"))
    )
    (net (code "235") (name "Net-(SSR_8HJB-I+)") (class "Default")
      (node (ref "R_8J") (pin "1") (pinfunction "1_1") (pintype "passive"))
      (node (ref "SSR_8HJ") (pin "3") (pinfunction "I+_3") (pintype "bidirectional"))
    )
    (net (code "236") (name "REG_CLR") (class "Default")
      (node (ref "ARDUINO_D") (pin "4") (pinfunction "4_4") (pintype "passive"))
      (node (ref "R_CLR") (pin "1") (pinfunction "1_1") (pintype "passive"))
      (node (ref "SHIFTER0") (pin "10") (pinfunction "~{SCLR}_10") (pintype "bidirectional"))
      (node (ref "SHIFTER1") (pin "10") (pinfunction "~{SCLR}_10") (pintype "bidirectional"))
      (node (ref "SHIFTER2") (pin "10") (pinfunction "~{SCLR}_10") (pintype "bidirectional"))
      (node (ref "SHIFTER3") (pin "10") (pinfunction "~{SCLR}_10") (pintype "bidirectional"))
      (node (ref "SHIFTER4") (pin "10") (pinfunction "~{SCLR}_10") (pintype "bidirectional"))
      (node (ref "SHIFTER5") (pin "10") (pinfunction "~{SCLR}_10") (pintype "bidirectional"))
      (node (ref "SHIFTER6") (pin "10") (pinfunction "~{SCLR}_10") (pintype "bidirectional"))
      (node (ref "SHIFTER7") (pin "10") (pinfunction "~{SCLR}_10") (pintype "bidirectional"))
      (node (ref "SHIFTER8") (pin "10") (pinfunction "~{SCLR}_10") (pintype "bidirectional"))
    )
    (net (code "237") (name "REG_LOAD") (class "Default")
      (node (ref "ARDUINO_D") (pin "5") (pinfunction "5_5") (pintype "passive"))
      (node (ref "R_LOAD") (pin "2") (pinfunction "2_2") (pintype "passive"))
      (node (ref "SHIFTER0") (pin "12") (pinfunction "RCK_12") (pintype "bidirectional"))
      (node (ref "SHIFTER1") (pin "12") (pinfunction "RCK_12") (pintype "bidirectional"))
      (node (ref "SHIFTER2") (pin "12") (pinfunction "RCK_12") (pintype "bidirectional"))
      (node (ref "SHIFTER3") (pin "12") (pinfunction "RCK_12") (pintype "bidirectional"))
      (node (ref "SHIFTER4") (pin "12") (pinfunction "RCK_12") (pintype "bidirectional"))
      (node (ref "SHIFTER5") (pin "12") (pinfunction "RCK_12") (pintype "bidirectional"))
      (node (ref "SHIFTER6") (pin "12") (pinfunction "RCK_12") (pintype "bidirectional"))
      (node (ref "SHIFTER7") (pin "12") (pinfunction "RCK_12") (pintype "bidirectional"))
      (node (ref "SHIFTER8") (pin "12") (pinfunction "RCK_12") (pintype "bidirectional"))
    )
    (net (code "238") (name "REG_OE") (class "Default")
      (node (ref "ARDUINO_D") (pin "6") (pinfunction "6_6") (pintype "passive"))
      (node (ref "R_OE") (pin "1") (pinfunction "1_1") (pintype "passive"))
      (node (ref "SHIFTER0") (pin "13") (pinfunction "~{G}_13") (pintype "bidirectional"))
      (node (ref "SHIFTER1") (pin "13") (pinfunction "~{G}_13") (pintype "bidirectional"))
      (node (ref "SHIFTER2") (pin "13") (pinfunction "~{G}_13") (pintype "bidirectional"))
      (node (ref "SHIFTER3") (pin "13") (pinfunction "~{G}_13") (pintype "bidirectional"))
      (node (ref "SHIFTER4") (pin "13") (pinfunction "~{G}_13") (pintype "bidirectional"))
      (node (ref "SHIFTER5") (pin "13") (pinfunction "~{G}_13") (pintype "bidirectional"))
      (node (ref "SHIFTER6") (pin "13") (pinfunction "~{G}_13") (pintype "bidirectional"))
      (node (ref "SHIFTER7") (pin "13") (pinfunction "~{G}_13") (pintype "bidirectional"))
      (node (ref "SHIFTER8") (pin "13") (pinfunction "~{G}_13") (pintype "bidirectional"))
    )
    (net (code "239") (name "SPI_MISO") (class "Default")
      (node (ref "ARDUINO_D") (pin "1") (pinfunction "1_1") (pintype "passive"))
      (node (ref "HEADER_EXT") (pin "4") (pinfunction "4_4") (pintype "passive"))
    )
    (net (code "240") (name "SPI_MOSI") (class "Default")
      (node (ref "ARDUINO_D") (pin "2") (pinfunction "2_2") (pintype "passive"))
      (node (ref "HEADER_EXT") (pin "5") (pinfunction "5_5") (pintype "passive"))
      (node (ref "SHIFTER0") (pin "14") (pinfunction "SI_14") (pintype "bidirectional"))
    )
    (net (code "241") (name "SPI_SCLK") (class "Default")
      (node (ref "ARDUINO_A") (pin "1") (pinfunction "1_1") (pintype "passive"))
      (node (ref "HEADER_EXT") (pin "3") (pinfunction "3_3") (pintype "passive"))
      (node (ref "SHIFTER0") (pin "11") (pinfunction "SCK_11") (pintype "bidirectional"))
      (node (ref "SHIFTER1") (pin "11") (pinfunction "SCK_11") (pintype "bidirectional"))
      (node (ref "SHIFTER2") (pin "11") (pinfunction "SCK_11") (pintype "bidirectional"))
      (node (ref "SHIFTER3") (pin "11") (pinfunction "SCK_11") (pintype "bidirectional"))
      (node (ref "SHIFTER4") (pin "11") (pinfunction "SCK_11") (pintype "bidirectional"))
      (node (ref "SHIFTER5") (pin "11") (pinfunction "SCK_11") (pintype "bidirectional"))
      (node (ref "SHIFTER6") (pin "11") (pinfunction "SCK_11") (pintype "bidirectional"))
      (node (ref "SHIFTER7") (pin "11") (pinfunction "SCK_11") (pintype "bidirectional"))
      (node (ref "SHIFTER8") (pin "11") (pinfunction "SCK_11") (pintype "bidirectional"))
    )
    (net (code "242") (name "SPI_SO1-SI2") (class "Default")
      (node (ref "SHIFTER0") (pin "9") (pinfunction "SO_9") (pintype "bidirectional"))
      (node (ref "SHIFTER1") (pin "14") (pinfunction "SI_14") (pintype "bidirectional"))
    )
    (net (code "243") (name "SPI_SO2-SI3") (class "Default")
      (node (ref "SHIFTER1") (pin "9") (pinfunction "SO_9") (pintype "bidirectional"))
      (node (ref "SHIFTER2") (pin "14") (pinfunction "SI_14") (pintype "bidirectional"))
    )
    (net (code "244") (name "SPI_SO3-SI4") (class "Default")
      (node (ref "SHIFTER2") (pin "9") (pinfunction "SO_9") (pintype "bidirectional"))
      (node (ref "SHIFTER3") (pin "14") (pinfunction "SI_14") (pintype "bidirectional"))
    )
    (net (code "245") (name "SPI_SO4-SI5") (class "Default")
      (node (ref "SHIFTER3") (pin "9") (pinfunction "SO_9") (pintype "bidirectional"))
      (node (ref "SHIFTER4") (pin "14") (pinfunction "SI_14") (pintype "bidirectional"))
    )
    (net (code "246") (name "SPI_SO5-SI6") (class "Default")
      (node (ref "SHIFTER4") (pin "9") (pinfunction "SO_9") (pintype "bidirectional"))
      (node (ref "SHIFTER5") (pin "14") (pinfunction "SI_14") (pintype "bidirectional"))
    )
    (net (code "247") (name "SPI_SO6-SI7") (class "Default")
      (node (ref "SHIFTER5") (pin "9") (pinfunction "SO_9") (pintype "bidirectional"))
      (node (ref "SHIFTER6") (pin "14") (pinfunction "SI_14") (pintype "bidirectional"))
    )
    (net (code "248") (name "SPI_SO7-SI8") (class "Default")
      (node (ref "SHIFTER6") (pin "9") (pinfunction "SO_9") (pintype "bidirectional"))
      (node (ref "SHIFTER7") (pin "14") (pinfunction "SI_14") (pintype "bidirectional"))
    )
    (net (code "249") (name "SPI_SO8-SI9") (class "Default")
      (node (ref "SHIFTER7") (pin "9") (pinfunction "SO_9") (pintype "bidirectional"))
      (node (ref "SHIFTER8") (pin "14") (pinfunction "SI_14") (pintype "bidirectional"))
    )
    (net (code "250") (name "SPI_SS") (class "Default")
      (node (ref "ARDUINO_D") (pin "3") (pinfunction "3_3") (pintype "passive"))
      (node (ref "HEADER_EXT") (pin "6") (pinfunction "6_6") (pintype "passive"))
    )
    (net (code "251") (name "SW-1A") (class "Default")
      (node (ref "SHIFTER0") (pin "15") (pinfunction "Q0_15") (pintype "bidirectional"))
      (node (ref "SSR_1AB") (pin "2") (pinfunction "I-_2") (pintype "bidirectional"))
    )
    (net (code "252") (name "SW-1B") (class "Default")
      (node (ref "SHIFTER0") (pin "1") (pinfunction "Q1_1") (pintype "bidirectional"))
      (node (ref "SSR_1AB") (pin "4") (pinfunction "I-_4") (pintype "bidirectional"))
    )
    (net (code "253") (name "SW-1C") (class "Default")
      (node (ref "SHIFTER0") (pin "2") (pinfunction "Q2_2") (pintype "bidirectional"))
      (node (ref "SSR_1CD") (pin "2") (pinfunction "I-_2") (pintype "bidirectional"))
    )
    (net (code "254") (name "SW-1D") (class "Default")
      (node (ref "SHIFTER0") (pin "3") (pinfunction "Q3_3") (pintype "bidirectional"))
      (node (ref "SSR_1CD") (pin "4") (pinfunction "I-_4") (pintype "bidirectional"))
    )
    (net (code "255") (name "SW-1E") (class "Default")
      (node (ref "SHIFTER0") (pin "4") (pinfunction "Q4_4") (pintype "bidirectional"))
      (node (ref "SSR_1EF") (pin "2") (pinfunction "I-_2") (pintype "bidirectional"))
    )
    (net (code "256") (name "SW-1F") (class "Default")
      (node (ref "SHIFTER0") (pin "5") (pinfunction "Q5_5") (pintype "bidirectional"))
      (node (ref "SSR_1EF") (pin "4") (pinfunction "I-_4") (pintype "bidirectional"))
    )
    (net (code "257") (name "SW-1G") (class "Default")
      (node (ref "SHIFTER0") (pin "6") (pinfunction "Q6_6") (pintype "bidirectional"))
      (node (ref "SSR_1GH") (pin "2") (pinfunction "I-_2") (pintype "bidirectional"))
    )
    (net (code "258") (name "SW-1H") (class "Default")
      (node (ref "SHIFTER0") (pin "7") (pinfunction "Q7_7") (pintype "bidirectional"))
      (node (ref "SSR_1GH") (pin "4") (pinfunction "I-_4") (pintype "bidirectional"))
    )
    (net (code "259") (name "SW-1J") (class "Default")
      (node (ref "SHIFTER1") (pin "15") (pinfunction "Q0_15") (pintype "bidirectional"))
      (node (ref "SSR_1J/2A") (pin "2") (pinfunction "I-_2") (pintype "bidirectional"))
    )
    (net (code "260") (name "SW-2A") (class "Default")
      (node (ref "SHIFTER1") (pin "1") (pinfunction "Q1_1") (pintype "bidirectional"))
      (node (ref "SSR_1J/2A") (pin "4") (pinfunction "I-_4") (pintype "bidirectional"))
    )
    (net (code "261") (name "SW-2B") (class "Default")
      (node (ref "SHIFTER1") (pin "2") (pinfunction "Q2_2") (pintype "bidirectional"))
      (node (ref "SSR_2BC") (pin "2") (pinfunction "I-_2") (pintype "bidirectional"))
    )
    (net (code "262") (name "SW-2C") (class "Default")
      (node (ref "SHIFTER1") (pin "3") (pinfunction "Q3_3") (pintype "bidirectional"))
      (node (ref "SSR_2BC") (pin "4") (pinfunction "I-_4") (pintype "bidirectional"))
    )
    (net (code "263") (name "SW-2D") (class "Default")
      (node (ref "SHIFTER1") (pin "4") (pinfunction "Q4_4") (pintype "bidirectional"))
      (node (ref "SSR_2DE") (pin "2") (pinfunction "I-_2") (pintype "bidirectional"))
    )
    (net (code "264") (name "SW-2E") (class "Default")
      (node (ref "SHIFTER1") (pin "5") (pinfunction "Q5_5") (pintype "bidirectional"))
      (node (ref "SSR_2DE") (pin "4") (pinfunction "I-_4") (pintype "bidirectional"))
    )
    (net (code "265") (name "SW-2F") (class "Default")
      (node (ref "SHIFTER1") (pin "6") (pinfunction "Q6_6") (pintype "bidirectional"))
      (node (ref "SSR_2FG") (pin "2") (pinfunction "I-_2") (pintype "bidirectional"))
    )
    (net (code "266") (name "SW-2G") (class "Default")
      (node (ref "SHIFTER1") (pin "7") (pinfunction "Q7_7") (pintype "bidirectional"))
      (node (ref "SSR_2FG") (pin "4") (pinfunction "I-_4") (pintype "bidirectional"))
    )
    (net (code "267") (name "SW-2H") (class "Default")
      (node (ref "SHIFTER2") (pin "15") (pinfunction "Q0_15") (pintype "bidirectional"))
      (node (ref "SSR_2HJ") (pin "2") (pinfunction "I-_2") (pintype "bidirectional"))
    )
    (net (code "268") (name "SW-2J") (class "Default")
      (node (ref "SHIFTER2") (pin "1") (pinfunction "Q1_1") (pintype "bidirectional"))
      (node (ref "SSR_2HJ") (pin "4") (pinfunction "I-_4") (pintype "bidirectional"))
    )
    (net (code "269") (name "SW-3A") (class "Default")
      (node (ref "SHIFTER2") (pin "2") (pinfunction "Q2_2") (pintype "bidirectional"))
      (node (ref "SSR_3AB") (pin "2") (pinfunction "I-_2") (pintype "bidirectional"))
    )
    (net (code "270") (name "SW-3B") (class "Default")
      (node (ref "SHIFTER2") (pin "3") (pinfunction "Q3_3") (pintype "bidirectional"))
      (node (ref "SSR_3AB") (pin "4") (pinfunction "I-_4") (pintype "bidirectional"))
    )
    (net (code "271") (name "SW-3C") (class "Default")
      (node (ref "SHIFTER2") (pin "4") (pinfunction "Q4_4") (pintype "bidirectional"))
      (node (ref "SSR_3CD") (pin "2") (pinfunction "I-_2") (pintype "bidirectional"))
    )
    (net (code "272") (name "SW-3D") (class "Default")
      (node (ref "SHIFTER2") (pin "5") (pinfunction "Q5_5") (pintype "bidirectional"))
      (node (ref "SSR_3CD") (pin "4") (pinfunction "I-_4") (pintype "bidirectional"))
    )
    (net (code "273") (name "SW-3E") (class "Default")
      (node (ref "SHIFTER2") (pin "6") (pinfunction "Q6_6") (pintype "bidirectional"))
      (node (ref "SSR_3EF") (pin "2") (pinfunction "I-_2") (pintype "bidirectional"))
    )
    (net (code "274") (name "SW-3F") (class "Default")
      (node (ref "SHIFTER2") (pin "7") (pinfunction "Q7_7") (pintype "bidirectional"))
      (node (ref "SSR_3EF") (pin "4") (pinfunction "I-_4") (pintype "bidirectional"))
    )
    (net (code "275") (name "SW-3G") (class "Default")
      (node (ref "SHIFTER3") (pin "15") (pinfunction "Q0_15") (pintype "bidirectional"))
      (node (ref "SSR_3GH") (pin "2") (pinfunction "I-_2") (pintype "bidirectional"))
    )
    (net (code "276") (name "SW-3H") (class "Default")
      (node (ref "SHIFTER3") (pin "1") (pinfunction "Q1_1") (pintype "bidirectional"))
      (node (ref "SSR_3GH") (pin "4") (pinfunction "I-_4") (pintype "bidirectional"))
    )
    (net (code "277") (name "SW-3J") (class "Default")
      (node (ref "SHIFTER3") (pin "2") (pinfunction "Q2_2") (pintype "bidirectional"))
      (node (ref "SSR_3J/4A") (pin "2") (pinfunction "I-_2") (pintype "bidirectional"))
    )
    (net (code "278") (name "SW-4A") (class "Default")
      (node (ref "SHIFTER3") (pin "3") (pinfunction "Q3_3") (pintype "bidirectional"))
      (node (ref "SSR_3J/4A") (pin "4") (pinfunction "I-_4") (pintype "bidirectional"))
    )
    (net (code "279") (name "SW-4B") (class "Default")
      (node (ref "SHIFTER3") (pin "4") (pinfunction "Q4_4") (pintype "bidirectional"))
      (node (ref "SSR_4BC") (pin "2") (pinfunction "I-_2") (pintype "bidirectional"))
    )
    (net (code "280") (name "SW-4C") (class "Default")
      (node (ref "SHIFTER3") (pin "5") (pinfunction "Q5_5") (pintype "bidirectional"))
      (node (ref "SSR_4BC") (pin "4") (pinfunction "I-_4") (pintype "bidirectional"))
    )
    (net (code "281") (name "SW-4D") (class "Default")
      (node (ref "SHIFTER3") (pin "6") (pinfunction "Q6_6") (pintype "bidirectional"))
      (node (ref "SSR_4DE") (pin "2") (pinfunction "I-_2") (pintype "bidirectional"))
    )
    (net (code "282") (name "SW-4E") (class "Default")
      (node (ref "SHIFTER3") (pin "7") (pinfunction "Q7_7") (pintype "bidirectional"))
      (node (ref "SSR_4DE") (pin "4") (pinfunction "I-_4") (pintype "bidirectional"))
    )
    (net (code "283") (name "SW-4F") (class "Default")
      (node (ref "SHIFTER4") (pin "15") (pinfunction "Q0_15") (pintype "bidirectional"))
      (node (ref "SSR_4FG") (pin "2") (pinfunction "I-_2") (pintype "bidirectional"))
    )
    (net (code "284") (name "SW-4G") (class "Default")
      (node (ref "SHIFTER4") (pin "1") (pinfunction "Q1_1") (pintype "bidirectional"))
      (node (ref "SSR_4FG") (pin "4") (pinfunction "I-_4") (pintype "bidirectional"))
    )
    (net (code "285") (name "SW-4H") (class "Default")
      (node (ref "SHIFTER4") (pin "2") (pinfunction "Q2_2") (pintype "bidirectional"))
      (node (ref "SSR_4HJ") (pin "2") (pinfunction "I-_2") (pintype "bidirectional"))
    )
    (net (code "286") (name "SW-4J") (class "Default")
      (node (ref "SHIFTER4") (pin "3") (pinfunction "Q3_3") (pintype "bidirectional"))
      (node (ref "SSR_4HJ") (pin "4") (pinfunction "I-_4") (pintype "bidirectional"))
    )
    (net (code "287") (name "SW-5A") (class "Default")
      (node (ref "SHIFTER4") (pin "4") (pinfunction "Q4_4") (pintype "bidirectional"))
      (node (ref "SSR_5AB") (pin "2") (pinfunction "I-_2") (pintype "bidirectional"))
    )
    (net (code "288") (name "SW-5B") (class "Default")
      (node (ref "SHIFTER4") (pin "5") (pinfunction "Q5_5") (pintype "bidirectional"))
      (node (ref "SSR_5AB") (pin "4") (pinfunction "I-_4") (pintype "bidirectional"))
    )
    (net (code "289") (name "SW-5C") (class "Default")
      (node (ref "SHIFTER4") (pin "6") (pinfunction "Q6_6") (pintype "bidirectional"))
      (node (ref "SSR_5CD") (pin "2") (pinfunction "I-_2") (pintype "bidirectional"))
    )
    (net (code "290") (name "SW-5D") (class "Default")
      (node (ref "SHIFTER4") (pin "7") (pinfunction "Q7_7") (pintype "bidirectional"))
      (node (ref "SSR_5CD") (pin "4") (pinfunction "I-_4") (pintype "bidirectional"))
    )
    (net (code "291") (name "SW-5E") (class "Default")
      (node (ref "SHIFTER5") (pin "15") (pinfunction "Q0_15") (pintype "bidirectional"))
      (node (ref "SSR_5EF") (pin "2") (pinfunction "I-_2") (pintype "bidirectional"))
    )
    (net (code "292") (name "SW-5F") (class "Default")
      (node (ref "SHIFTER5") (pin "1") (pinfunction "Q1_1") (pintype "bidirectional"))
      (node (ref "SSR_5EF") (pin "4") (pinfunction "I-_4") (pintype "bidirectional"))
    )
    (net (code "293") (name "SW-5G") (class "Default")
      (node (ref "SHIFTER5") (pin "2") (pinfunction "Q2_2") (pintype "bidirectional"))
      (node (ref "SSR_5GH") (pin "2") (pinfunction "I-_2") (pintype "bidirectional"))
    )
    (net (code "294") (name "SW-5H") (class "Default")
      (node (ref "SHIFTER5") (pin "3") (pinfunction "Q3_3") (pintype "bidirectional"))
      (node (ref "SSR_5GH") (pin "4") (pinfunction "I-_4") (pintype "bidirectional"))
    )
    (net (code "295") (name "SW-5J") (class "Default")
      (node (ref "SHIFTER5") (pin "4") (pinfunction "Q4_4") (pintype "bidirectional"))
      (node (ref "SSR_5J/6A") (pin "2") (pinfunction "I-_2") (pintype "bidirectional"))
    )
    (net (code "296") (name "SW-6A") (class "Default")
      (node (ref "SHIFTER5") (pin "5") (pinfunction "Q5_5") (pintype "bidirectional"))
      (node (ref "SSR_5J/6A") (pin "4") (pinfunction "I-_4") (pintype "bidirectional"))
    )
    (net (code "297") (name "SW-6B") (class "Default")
      (node (ref "SHIFTER5") (pin "6") (pinfunction "Q6_6") (pintype "bidirectional"))
      (node (ref "SSR_6BC") (pin "2") (pinfunction "I-_2") (pintype "bidirectional"))
    )
    (net (code "298") (name "SW-6C") (class "Default")
      (node (ref "SHIFTER5") (pin "7") (pinfunction "Q7_7") (pintype "bidirectional"))
      (node (ref "SSR_6BC") (pin "4") (pinfunction "I-_4") (pintype "bidirectional"))
    )
    (net (code "299") (name "SW-6D") (class "Default")
      (node (ref "SHIFTER6") (pin "15") (pinfunction "Q0_15") (pintype "bidirectional"))
      (node (ref "SSR_6DE") (pin "2") (pinfunction "I-_2") (pintype "bidirectional"))
    )
    (net (code "300") (name "SW-6E") (class "Default")
      (node (ref "SHIFTER6") (pin "1") (pinfunction "Q1_1") (pintype "bidirectional"))
      (node (ref "SSR_6DE") (pin "4") (pinfunction "I-_4") (pintype "bidirectional"))
    )
    (net (code "301") (name "SW-6F") (class "Default")
      (node (ref "SHIFTER6") (pin "2") (pinfunction "Q2_2") (pintype "bidirectional"))
      (node (ref "SSR_6FG") (pin "2") (pinfunction "I-_2") (pintype "bidirectional"))
    )
    (net (code "302") (name "SW-6G") (class "Default")
      (node (ref "SHIFTER6") (pin "3") (pinfunction "Q3_3") (pintype "bidirectional"))
      (node (ref "SSR_6FG") (pin "4") (pinfunction "I-_4") (pintype "bidirectional"))
    )
    (net (code "303") (name "SW-6H") (class "Default")
      (node (ref "SHIFTER6") (pin "4") (pinfunction "Q4_4") (pintype "bidirectional"))
      (node (ref "SSR_6HJ") (pin "2") (pinfunction "I-_2") (pintype "bidirectional"))
    )
    (net (code "304") (name "SW-6J") (class "Default")
      (node (ref "SHIFTER6") (pin "5") (pinfunction "Q5_5") (pintype "bidirectional"))
      (node (ref "SSR_6HJ") (pin "4") (pinfunction "I-_4") (pintype "bidirectional"))
    )
    (net (code "305") (name "SW-7A") (class "Default")
      (node (ref "SHIFTER6") (pin "6") (pinfunction "Q6_6") (pintype "bidirectional"))
      (node (ref "SSR_7AB") (pin "2") (pinfunction "I-_2") (pintype "bidirectional"))
    )
    (net (code "306") (name "SW-7B") (class "Default")
      (node (ref "SHIFTER6") (pin "7") (pinfunction "Q7_7") (pintype "bidirectional"))
      (node (ref "SSR_7AB") (pin "4") (pinfunction "I-_4") (pintype "bidirectional"))
    )
    (net (code "307") (name "SW-7C") (class "Default")
      (node (ref "SHIFTER7") (pin "15") (pinfunction "Q0_15") (pintype "bidirectional"))
      (node (ref "SSR_7CD") (pin "2") (pinfunction "I-_2") (pintype "bidirectional"))
    )
    (net (code "308") (name "SW-7D") (class "Default")
      (node (ref "SHIFTER7") (pin "1") (pinfunction "Q1_1") (pintype "bidirectional"))
      (node (ref "SSR_7CD") (pin "4") (pinfunction "I-_4") (pintype "bidirectional"))
    )
    (net (code "309") (name "SW-7E") (class "Default")
      (node (ref "SHIFTER7") (pin "2") (pinfunction "Q2_2") (pintype "bidirectional"))
      (node (ref "SSR_7EF") (pin "2") (pinfunction "I-_2") (pintype "bidirectional"))
    )
    (net (code "310") (name "SW-7F") (class "Default")
      (node (ref "SHIFTER7") (pin "3") (pinfunction "Q3_3") (pintype "bidirectional"))
      (node (ref "SSR_7EF") (pin "4") (pinfunction "I-_4") (pintype "bidirectional"))
    )
    (net (code "311") (name "SW-7G") (class "Default")
      (node (ref "SHIFTER7") (pin "4") (pinfunction "Q4_4") (pintype "bidirectional"))
      (node (ref "SSR_7GH") (pin "2") (pinfunction "I-_2") (pintype "bidirectional"))
    )
    (net (code "312") (name "SW-7H") (class "Default")
      (node (ref "SHIFTER7") (pin "5") (pinfunction "Q5_5") (pintype "bidirectional"))
      (node (ref "SSR_7GH") (pin "4") (pinfunction "I-_4") (pintype "bidirectional"))
    )
    (net (code "313") (name "SW-7J") (class "Default")
      (node (ref "SHIFTER7") (pin "6") (pinfunction "Q6_6") (pintype "bidirectional"))
      (node (ref "SSR_7J/8A") (pin "2") (pinfunction "I-_2") (pintype "bidirectional"))
    )
    (net (code "314") (name "SW-8A") (class "Default")
      (node (ref "SHIFTER7") (pin "7") (pinfunction "Q7_7") (pintype "bidirectional"))
      (node (ref "SSR_7J/8A") (pin "4") (pinfunction "I-_4") (pintype "bidirectional"))
    )
    (net (code "315") (name "SW-8B") (class "Default")
      (node (ref "SHIFTER8") (pin "15") (pinfunction "Q0_15") (pintype "bidirectional"))
      (node (ref "SSR_8BC") (pin "2") (pinfunction "I-_2") (pintype "bidirectional"))
    )
    (net (code "316") (name "SW-8C") (class "Default")
      (node (ref "SHIFTER8") (pin "1") (pinfunction "Q1_1") (pintype "bidirectional"))
      (node (ref "SSR_8BC") (pin "4") (pinfunction "I-_4") (pintype "bidirectional"))
    )
    (net (code "317") (name "SW-8D") (class "Default")
      (node (ref "SHIFTER8") (pin "2") (pinfunction "Q2_2") (pintype "bidirectional"))
      (node (ref "SSR_8DE") (pin "2") (pinfunction "I-_2") (pintype "bidirectional"))
    )
    (net (code "318") (name "SW-8E") (class "Default")
      (node (ref "SHIFTER8") (pin "3") (pinfunction "Q3_3") (pintype "bidirectional"))
      (node (ref "SSR_8DE") (pin "4") (pinfunction "I-_4") (pintype "bidirectional"))
    )
    (net (code "319") (name "SW-8F") (class "Default")
      (node (ref "SHIFTER8") (pin "4") (pinfunction "Q4_4") (pintype "bidirectional"))
      (node (ref "SSR_8FG") (pin "2") (pinfunction "I-_2") (pintype "bidirectional"))
    )
    (net (code "320") (name "SW-8G") (class "Default")
      (node (ref "SHIFTER8") (pin "5") (pinfunction "Q5_5") (pintype "bidirectional"))
      (node (ref "SSR_8FG") (pin "4") (pinfunction "I-_4") (pintype "bidirectional"))
    )
    (net (code "321") (name "SW-8H") (class "Default")
      (node (ref "SHIFTER8") (pin "6") (pinfunction "Q6_6") (pintype "bidirectional"))
      (node (ref "SSR_8HJ") (pin "2") (pinfunction "I-_2") (pintype "bidirectional"))
    )
    (net (code "322") (name "SW-8J") (class "Default")
      (node (ref "SHIFTER8") (pin "7") (pinfunction "Q7_7") (pintype "bidirectional"))
      (node (ref "SSR_8HJ") (pin "4") (pinfunction "I-_4") (pintype "bidirectional"))
    )
    (net (code "323") (name "TWI_RST") (class "Default")
      (node (ref "I2C_SWITCH") (pin "3") (pinfunction "~{RESET}_3") (pintype "bidirectional"))
      (node (ref "R_RST") (pin "1") (pinfunction "1_1") (pintype "passive"))
    )
    (net (code "324") (name "TWI_SCL") (class "Default")
      (node (ref "ARDUINO_A") (pin "9") (pinfunction "9_9") (pintype "passive"))
      (node (ref "HEADER_EXT") (pin "8") (pinfunction "8_8") (pintype "passive"))
      (node (ref "I2C_SWITCH") (pin "22") (pinfunction "SCL_22") (pintype "bidirectional"))
      (node (ref "R_SCL") (pin "1") (pinfunction "1_1") (pintype "passive"))
    )
    (net (code "325") (name "TWI_SCL1") (class "Default")
      (node (ref "DRV1") (pin "18") (pinfunction "SCL_18") (pintype "bidirectional"))
      (node (ref "I2C_SWITCH") (pin "5") (pinfunction "SCL0_5") (pintype "bidirectional"))
      (node (ref "R_SCL1") (pin "1") (pinfunction "1_1") (pintype "passive"))
    )
    (net (code "326") (name "TWI_SCL2") (class "Default")
      (node (ref "DRV2") (pin "18") (pinfunction "SCL_18") (pintype "bidirectional"))
      (node (ref "I2C_SWITCH") (pin "7") (pinfunction "SCL1_7") (pintype "bidirectional"))
      (node (ref "R_SCL2") (pin "1") (pinfunction "1_1") (pintype "passive"))
    )
    (net (code "327") (name "TWI_SCL3") (class "Default")
      (node (ref "DRV3") (pin "18") (pinfunction "SCL_18") (pintype "bidirectional"))
      (node (ref "I2C_SWITCH") (pin "9") (pinfunction "SCL2_9") (pintype "bidirectional"))
      (node (ref "R_SCL3") (pin "1") (pinfunction "1_1") (pintype "passive"))
    )
    (net (code "328") (name "TWI_SCL4") (class "Default")
      (node (ref "DRV4") (pin "18") (pinfunction "SCL_18") (pintype "bidirectional"))
      (node (ref "I2C_SWITCH") (pin "11") (pinfunction "SCL3_11") (pintype "bidirectional"))
      (node (ref "R_SCL4") (pin "1") (pinfunction "1_1") (pintype "passive"))
    )
    (net (code "329") (name "TWI_SCL5") (class "Default")
      (node (ref "DRV5") (pin "18") (pinfunction "SCL_18") (pintype "bidirectional"))
      (node (ref "I2C_SWITCH") (pin "14") (pinfunction "SCL4_14") (pintype "bidirectional"))
      (node (ref "R_SCL5") (pin "1") (pinfunction "1_1") (pintype "passive"))
    )
    (net (code "330") (name "TWI_SCL6") (class "Default")
      (node (ref "DRV6") (pin "18") (pinfunction "SCL_18") (pintype "bidirectional"))
      (node (ref "I2C_SWITCH") (pin "16") (pinfunction "SCL5_16") (pintype "bidirectional"))
      (node (ref "R_SCL6") (pin "1") (pinfunction "1_1") (pintype "passive"))
    )
    (net (code "331") (name "TWI_SCL7") (class "Default")
      (node (ref "DRV7") (pin "18") (pinfunction "SCL_18") (pintype "bidirectional"))
      (node (ref "I2C_SWITCH") (pin "18") (pinfunction "SCL6_18") (pintype "bidirectional"))
      (node (ref "R_SCL7") (pin "1") (pinfunction "1_1") (pintype "passive"))
    )
    (net (code "332") (name "TWI_SCL8") (class "Default")
      (node (ref "DRV8") (pin "18") (pinfunction "SCL_18") (pintype "bidirectional"))
      (node (ref "I2C_SWITCH") (pin "20") (pinfunction "SCL7_20") (pintype "bidirectional"))
      (node (ref "R_SCL8") (pin "1") (pinfunction "1_1") (pintype "passive"))
    )
    (net (code "333") (name "TWI_SDA") (class "Default")
      (node (ref "ARDUINO_A") (pin "8") (pinfunction "8_8") (pintype "passive"))
      (node (ref "HEADER_EXT") (pin "7") (pinfunction "7_7") (pintype "passive"))
      (node (ref "I2C_SWITCH") (pin "23") (pinfunction "SDA_23") (pintype "bidirectional"))
      (node (ref "R_SDA") (pin "1") (pinfunction "1_1") (pintype "passive"))
    )
    (net (code "334") (name "TWI_SDA1") (class "Default")
      (node (ref "DRV1") (pin "19") (pinfunction "SDA_19") (pintype "bidirectional"))
      (node (ref "I2C_SWITCH") (pin "4") (pinfunction "SDA0_4") (pintype "bidirectional"))
      (node (ref "R_SDA1") (pin "1") (pinfunction "1_1") (pintype "passive"))
    )
    (net (code "335") (name "TWI_SDA2") (class "Default")
      (node (ref "DRV2") (pin "19") (pinfunction "SDA_19") (pintype "bidirectional"))
      (node (ref "I2C_SWITCH") (pin "6") (pinfunction "SDA1_6") (pintype "bidirectional"))
      (node (ref "R_SDA2") (pin "1") (pinfunction "1_1") (pintype "passive"))
    )
    (net (code "336") (name "TWI_SDA3") (class "Default")
      (node (ref "DRV3") (pin "19") (pinfunction "SDA_19") (pintype "bidirectional"))
      (node (ref "I2C_SWITCH") (pin "8") (pinfunction "SDA2_8") (pintype "bidirectional"))
      (node (ref "R_SDA3") (pin "1") (pinfunction "1_1") (pintype "passive"))
    )
    (net (code "337") (name "TWI_SDA4") (class "Default")
      (node (ref "DRV4") (pin "19") (pinfunction "SDA_19") (pintype "bidirectional"))
      (node (ref "I2C_SWITCH") (pin "10") (pinfunction "SDA3_10") (pintype "bidirectional"))
      (node (ref "R_SDA4") (pin "1") (pinfunction "1_1") (pintype "passive"))
    )
    (net (code "338") (name "TWI_SDA5") (class "Default")
      (node (ref "DRV5") (pin "19") (pinfunction "SDA_19") (pintype "bidirectional"))
      (node (ref "I2C_SWITCH") (pin "13") (pinfunction "SDA4_13") (pintype "bidirectional"))
      (node (ref "R_SDA5") (pin "1") (pinfunction "1_1") (pintype "passive"))
    )
    (net (code "339") (name "TWI_SDA6") (class "Default")
      (node (ref "DRV6") (pin "19") (pinfunction "SDA_19") (pintype "bidirectional"))
      (node (ref "I2C_SWITCH") (pin "15") (pinfunction "SDA5_15") (pintype "bidirectional"))
      (node (ref "R_SDA6") (pin "1") (pinfunction "1_1") (pintype "passive"))
    )
    (net (code "340") (name "TWI_SDA7") (class "Default")
      (node (ref "DRV7") (pin "19") (pinfunction "SDA_19") (pintype "bidirectional"))
      (node (ref "I2C_SWITCH") (pin "17") (pinfunction "SDA6_17") (pintype "bidirectional"))
      (node (ref "R_SDA7") (pin "1") (pinfunction "1_1") (pintype "passive"))
    )
    (net (code "341") (name "TWI_SDA8") (class "Default")
      (node (ref "DRV8") (pin "19") (pinfunction "SDA_19") (pintype "bidirectional"))
      (node (ref "I2C_SWITCH") (pin "19") (pinfunction "SDA7_19") (pintype "bidirectional"))
      (node (ref "R_SDA8") (pin "1") (pinfunction "1_1") (pintype "passive"))
    )
    (net (code "342") (name "TWI_SW0") (class "Default")
      (node (ref "ARDUINO_D") (pin "11") (pinfunction "11_11") (pintype "passive"))
      (node (ref "I2C_SWITCH") (pin "1") (pinfunction "A0_1") (pintype "bidirectional"))
    )
    (net (code "343") (name "TWI_SW1") (class "Default")
      (node (ref "ARDUINO_A") (pin "10") (pinfunction "10_10") (pintype "passive"))
      (node (ref "I2C_SWITCH") (pin "2") (pinfunction "A1_2") (pintype "bidirectional"))
    )
    (net (code "344") (name "TWI_SW2") (class "Default")
      (node (ref "ARDUINO_A") (pin "11") (pinfunction "11_11") (pintype "passive"))
      (node (ref "I2C_SWITCH") (pin "21") (pinfunction "A2_21") (pintype "bidirectional"))
    )
    (net (code "345") (name "UART_RXD") (class "Default")
      (node (ref "ARDUINO_D") (pin "14") (pinfunction "14_14") (pintype "passive"))
      (node (ref "HEADER_EXT") (pin "10") (pinfunction "10_10") (pintype "passive"))
    )
    (net (code "346") (name "UART_TXD") (class "Default")
      (node (ref "ARDUINO_D") (pin "15") (pinfunction "15_15") (pintype "passive"))
      (node (ref "HEADER_EXT") (pin "11") (pinfunction "11_11") (pintype "passive"))
    )
    (net (code "347") (name "UART_XCK") (class "Default")
      (node (ref "ARDUINO_D") (pin "9") (pinfunction "9_9") (pintype "passive"))
      (node (ref "HEADER_EXT") (pin "9") (pinfunction "9_9") (pintype "passive"))
    )
    (net (code "348") (name "unconnected-(ARDUINO_A-Pad2)") (class "Default")
      (node (ref "ARDUINO_A") (pin "2") (pinfunction "2_2") (pintype "passive"))
    )
    (net (code "349") (name "unconnected-(ARDUINO_A-Pad3)") (class "Default")
      (node (ref "ARDUINO_A") (pin "3") (pinfunction "3_3") (pintype "passive"))
    )
    (net (code "350") (name "unconnected-(ARDUINO_A-Pad4)") (class "Default")
      (node (ref "ARDUINO_A") (pin "4") (pinfunction "4_4") (pintype "passive"))
    )
    (net (code "351") (name "unconnected-(ARDUINO_A-Pad5)") (class "Default")
      (node (ref "ARDUINO_A") (pin "5") (pinfunction "5_5") (pintype "passive"))
    )
    (net (code "352") (name "unconnected-(ARDUINO_A-Pad6)") (class "Default")
      (node (ref "ARDUINO_A") (pin "6") (pinfunction "6_6") (pintype "passive"))
    )
    (net (code "353") (name "unconnected-(ARDUINO_A-Pad7)") (class "Default")
      (node (ref "ARDUINO_A") (pin "7") (pinfunction "7_7") (pintype "passive"))
    )
    (net (code "354") (name "unconnected-(ARDUINO_A-Pad12)") (class "Default")
      (node (ref "ARDUINO_A") (pin "12") (pinfunction "12_12") (pintype "passive"))
    )
    (net (code "355") (name "unconnected-(ARDUINO_A-Pad13)") (class "Default")
      (node (ref "ARDUINO_A") (pin "13") (pinfunction "13_13") (pintype "passive"))
    )
    (net (code "356") (name "unconnected-(ARDUINO_D-Pad13)") (class "Default")
      (node (ref "ARDUINO_D") (pin "13") (pinfunction "13_13") (pintype "passive"))
    )
    (net (code "357") (name "unconnected-(AUDIO_IN-Pad13)") (class "Default")
      (node (ref "AUDIO_IN") (pin "13") (pinfunction "13_13") (pintype "passive"))
    )
    (net (code "358") (name "unconnected-(GND_LIFT-T1B-Pad3)") (class "Default")
      (node (ref "GND_LIFT") (pin "3") (pinfunction "T1B_3") (pintype "bidirectional"))
    )
    (net (code "359") (name "unconnected-(GND_LIFT-T2B-Pad4)") (class "Default")
      (node (ref "GND_LIFT") (pin "4") (pinfunction "T2B_4") (pintype "bidirectional"))
    )
    (net (code "360") (name "unconnected-(SHIFTER8A-SO-Pad9)") (class "Default")
      (node (ref "SHIFTER8") (pin "9") (pinfunction "SO_9") (pintype "bidirectional"))
    )
  )
)
